# PKG900000001400.net
KiCad netlist of a schematic drawn in EAGLE
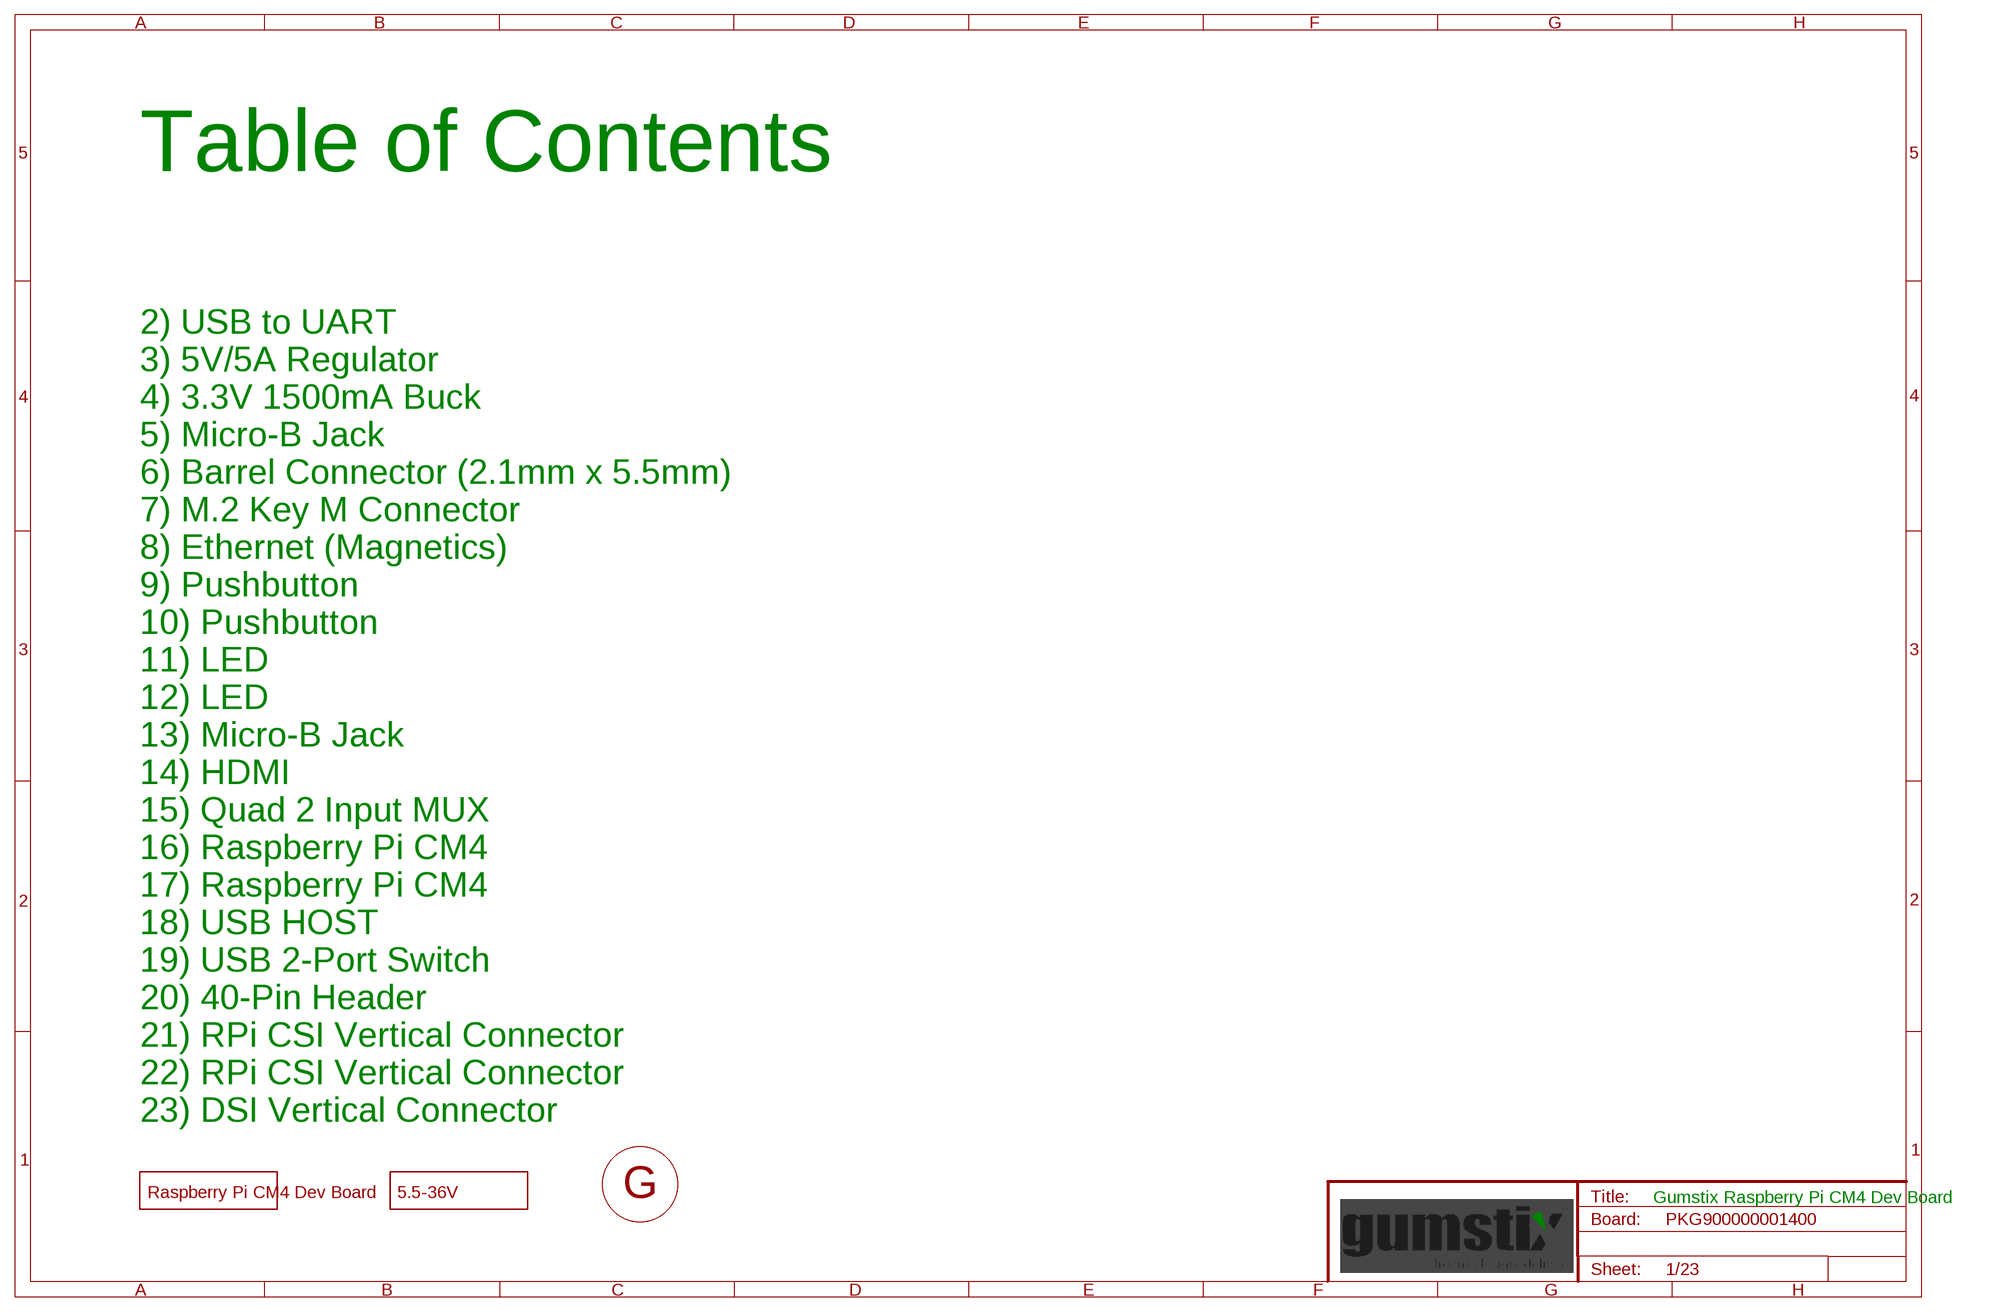
[diagram p0: schematic, sheet 1]
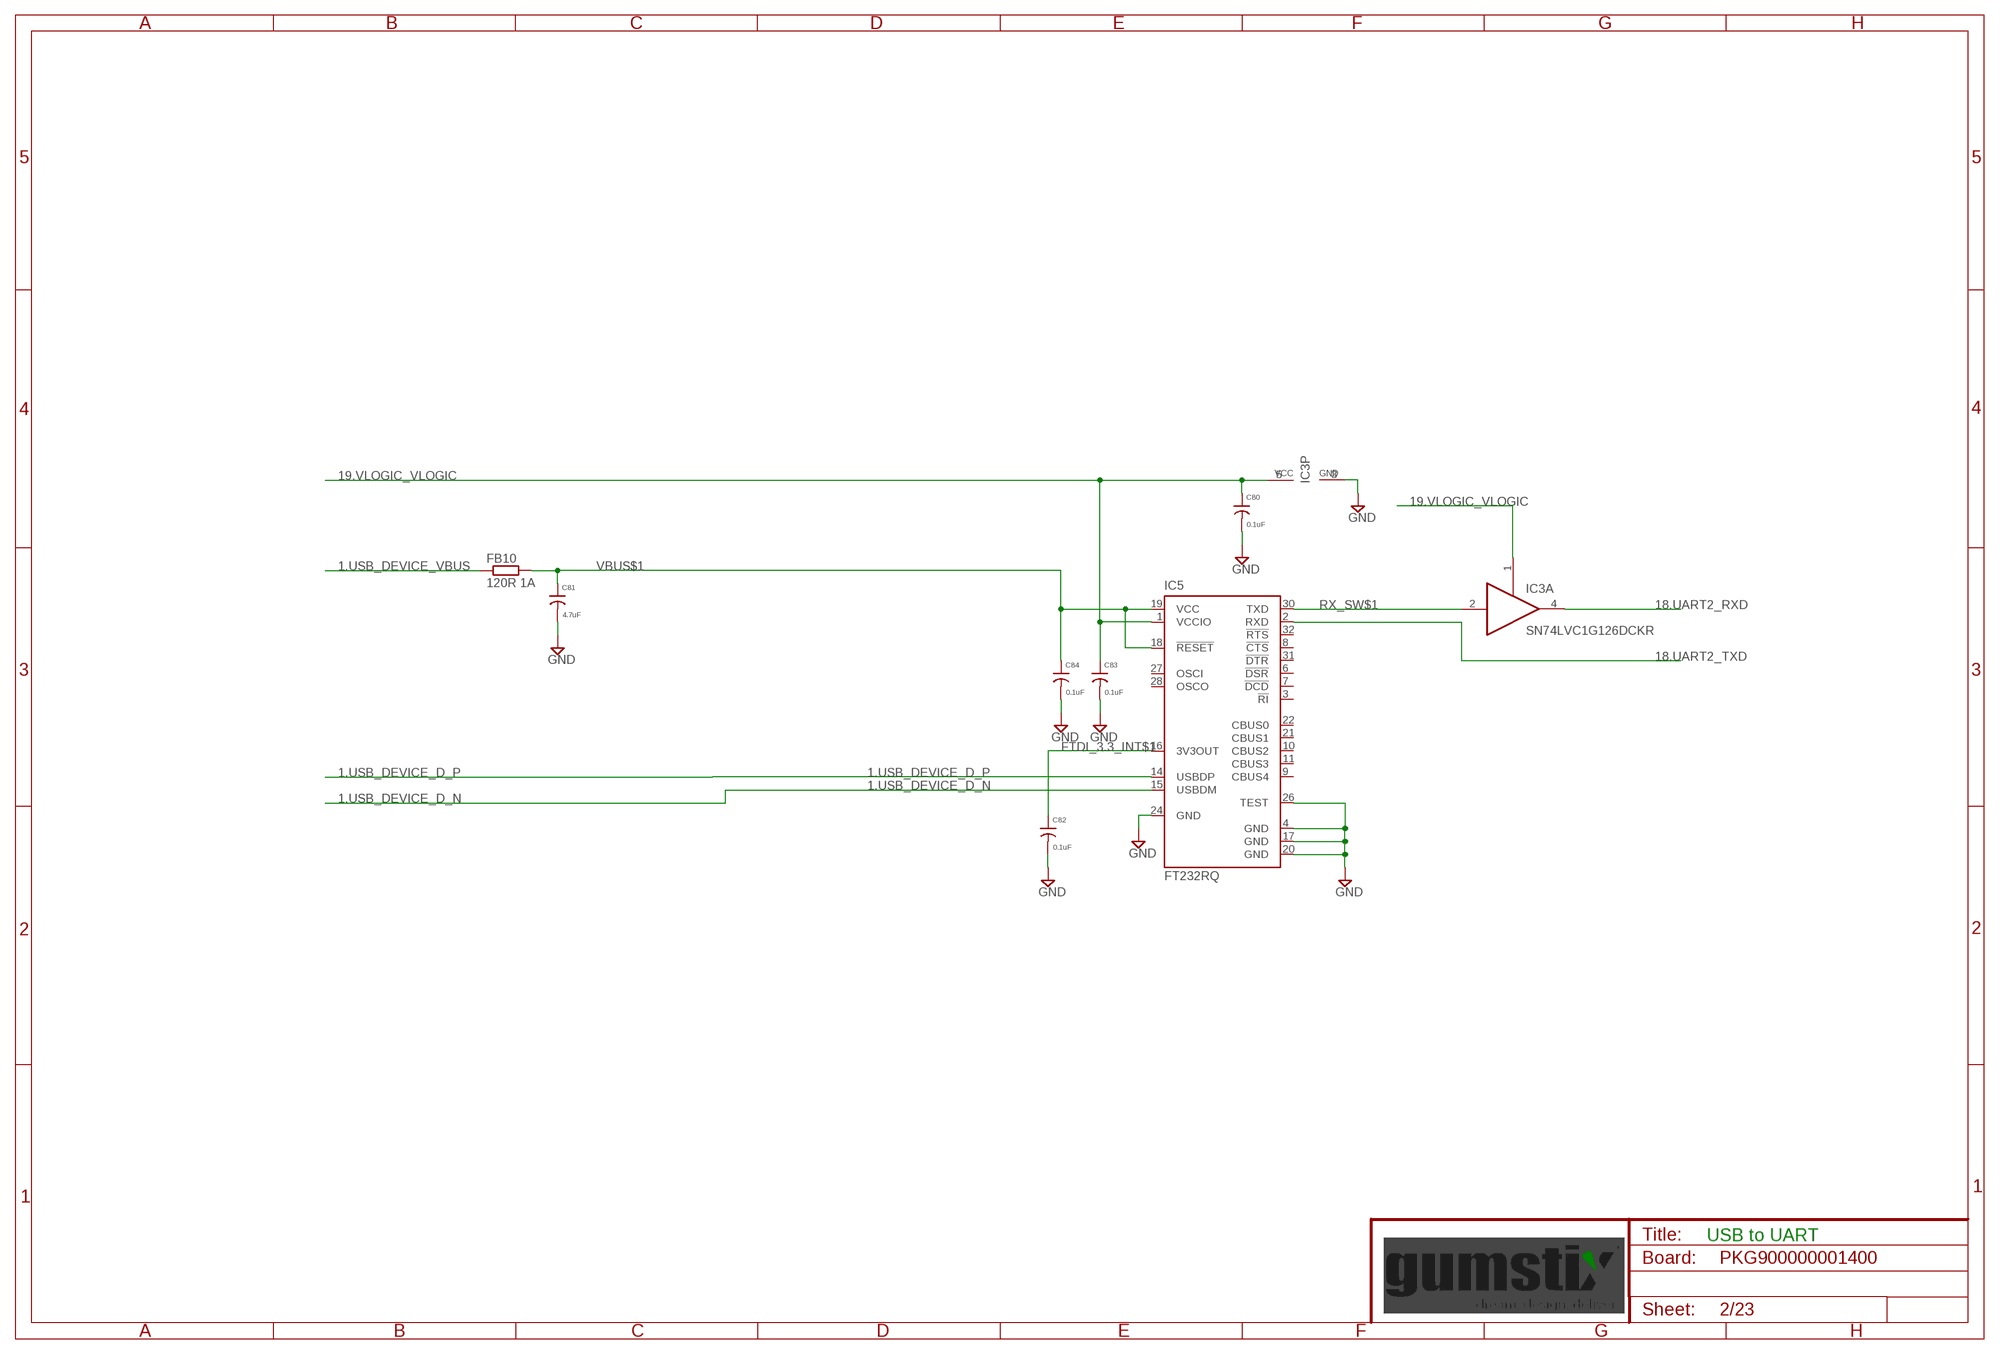
[diagram p1: schematic, sheet 2]
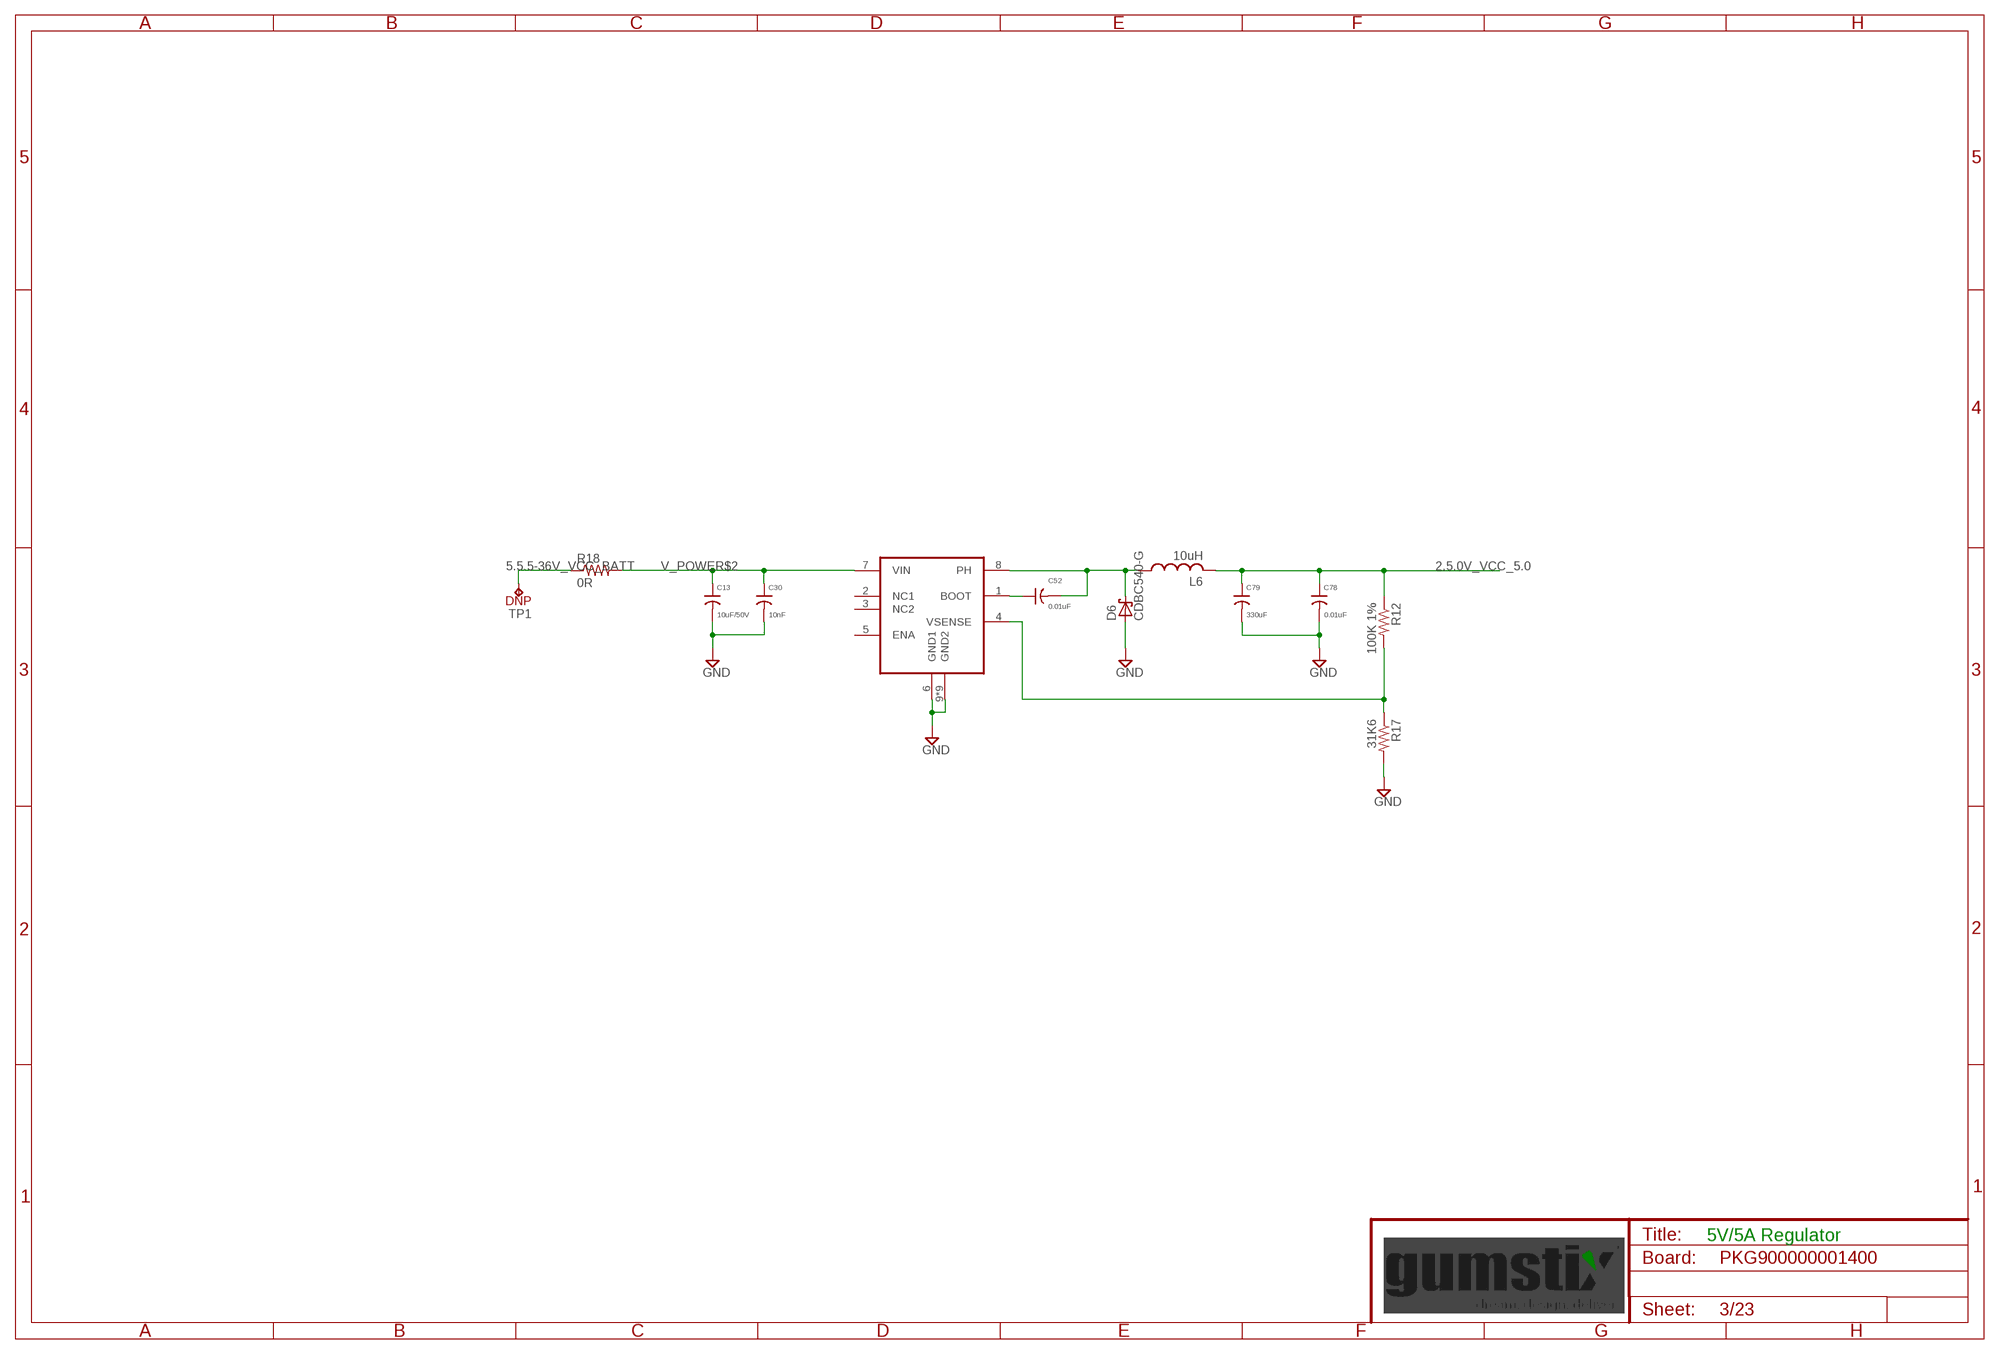
[diagram p2: schematic, sheet 3]
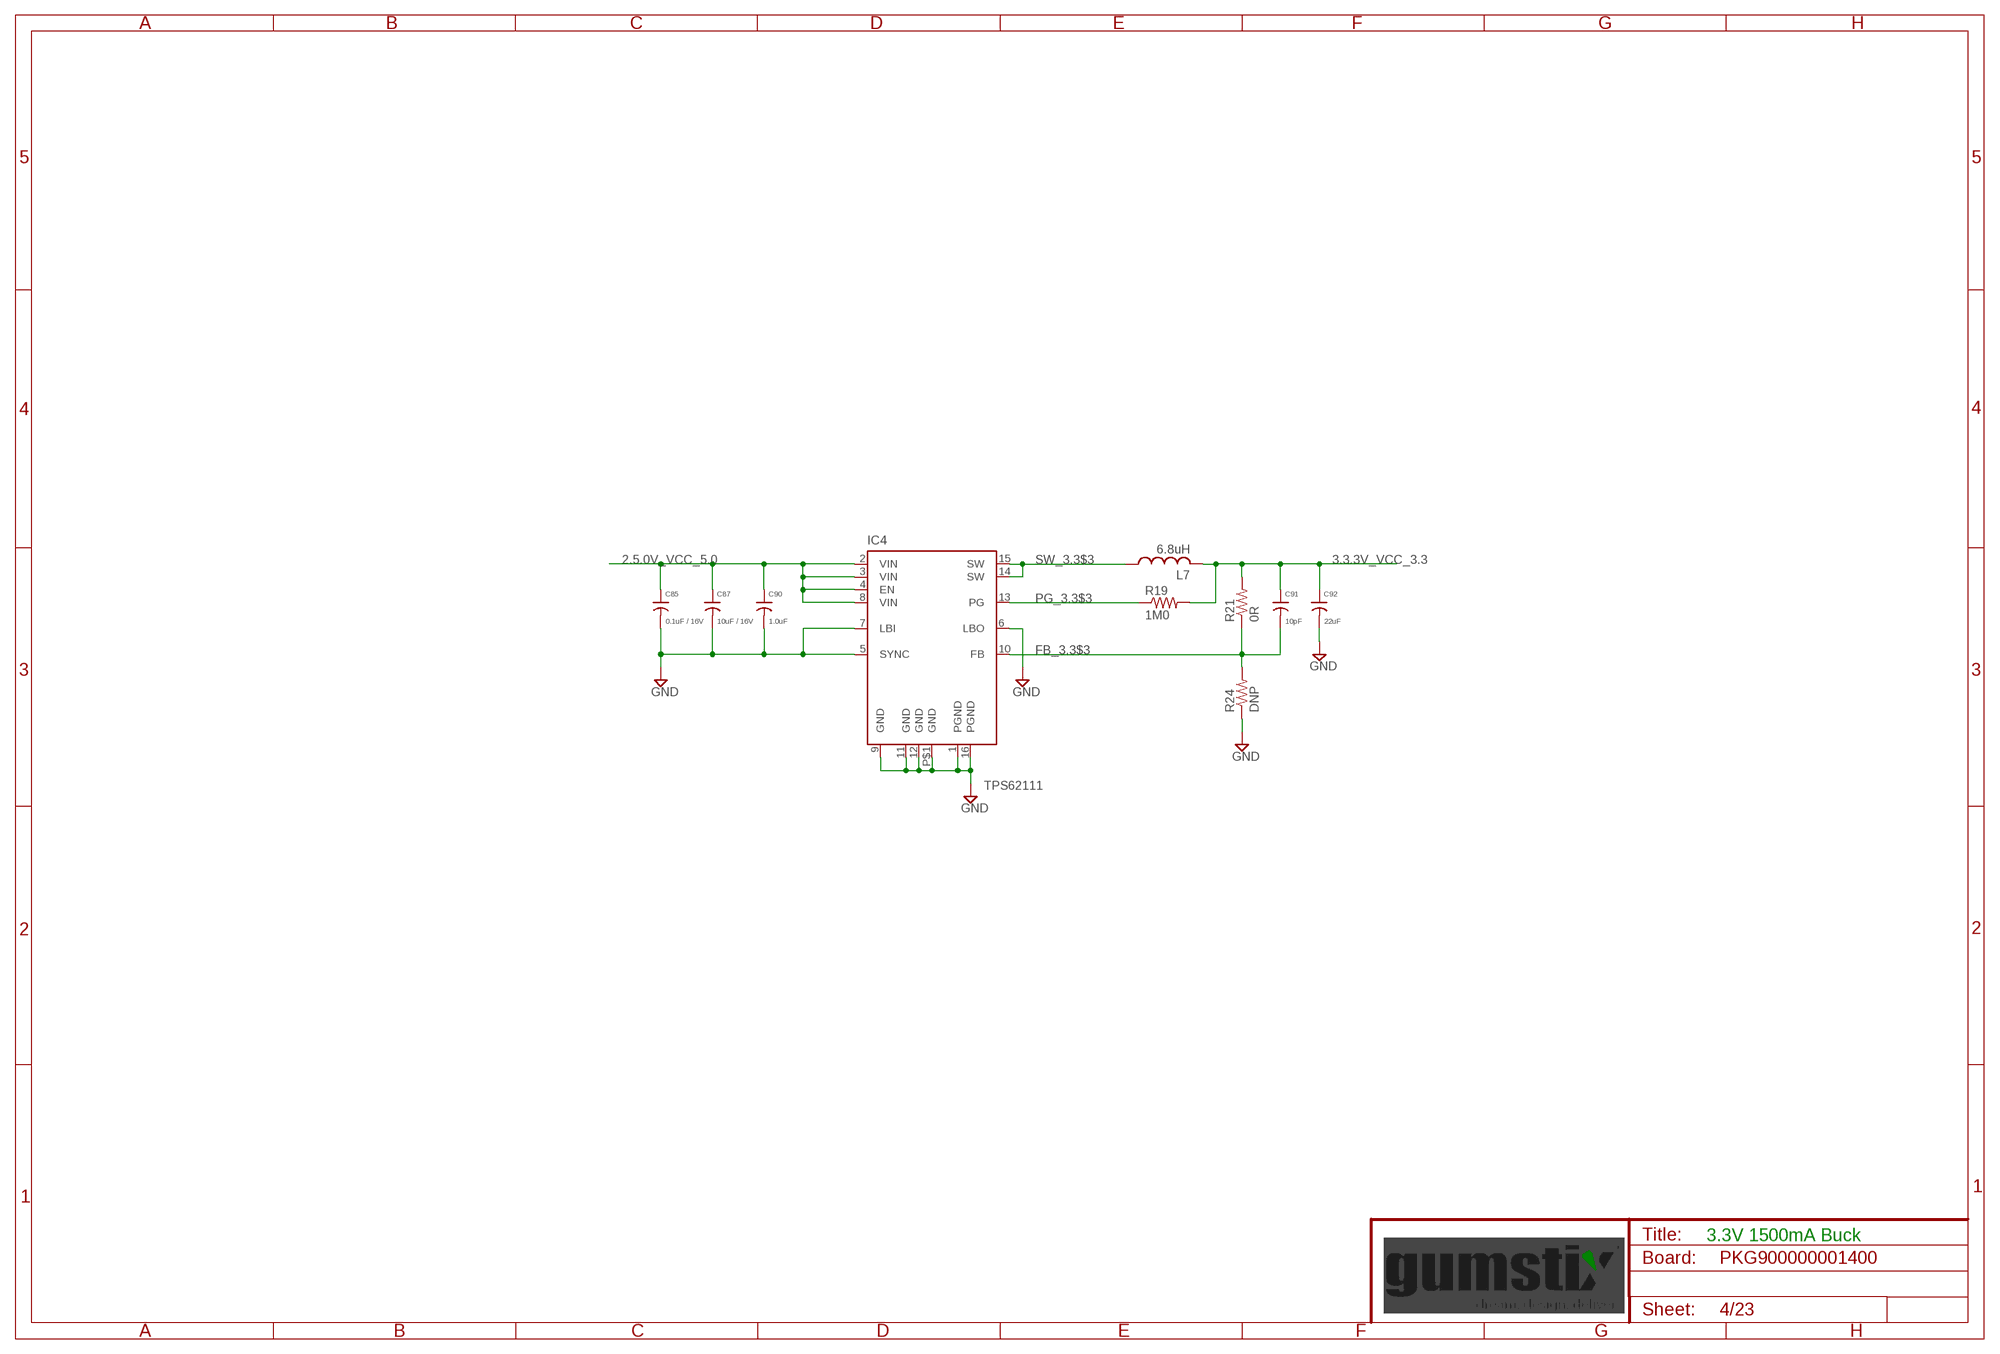
[diagram p3: schematic, sheet 4]
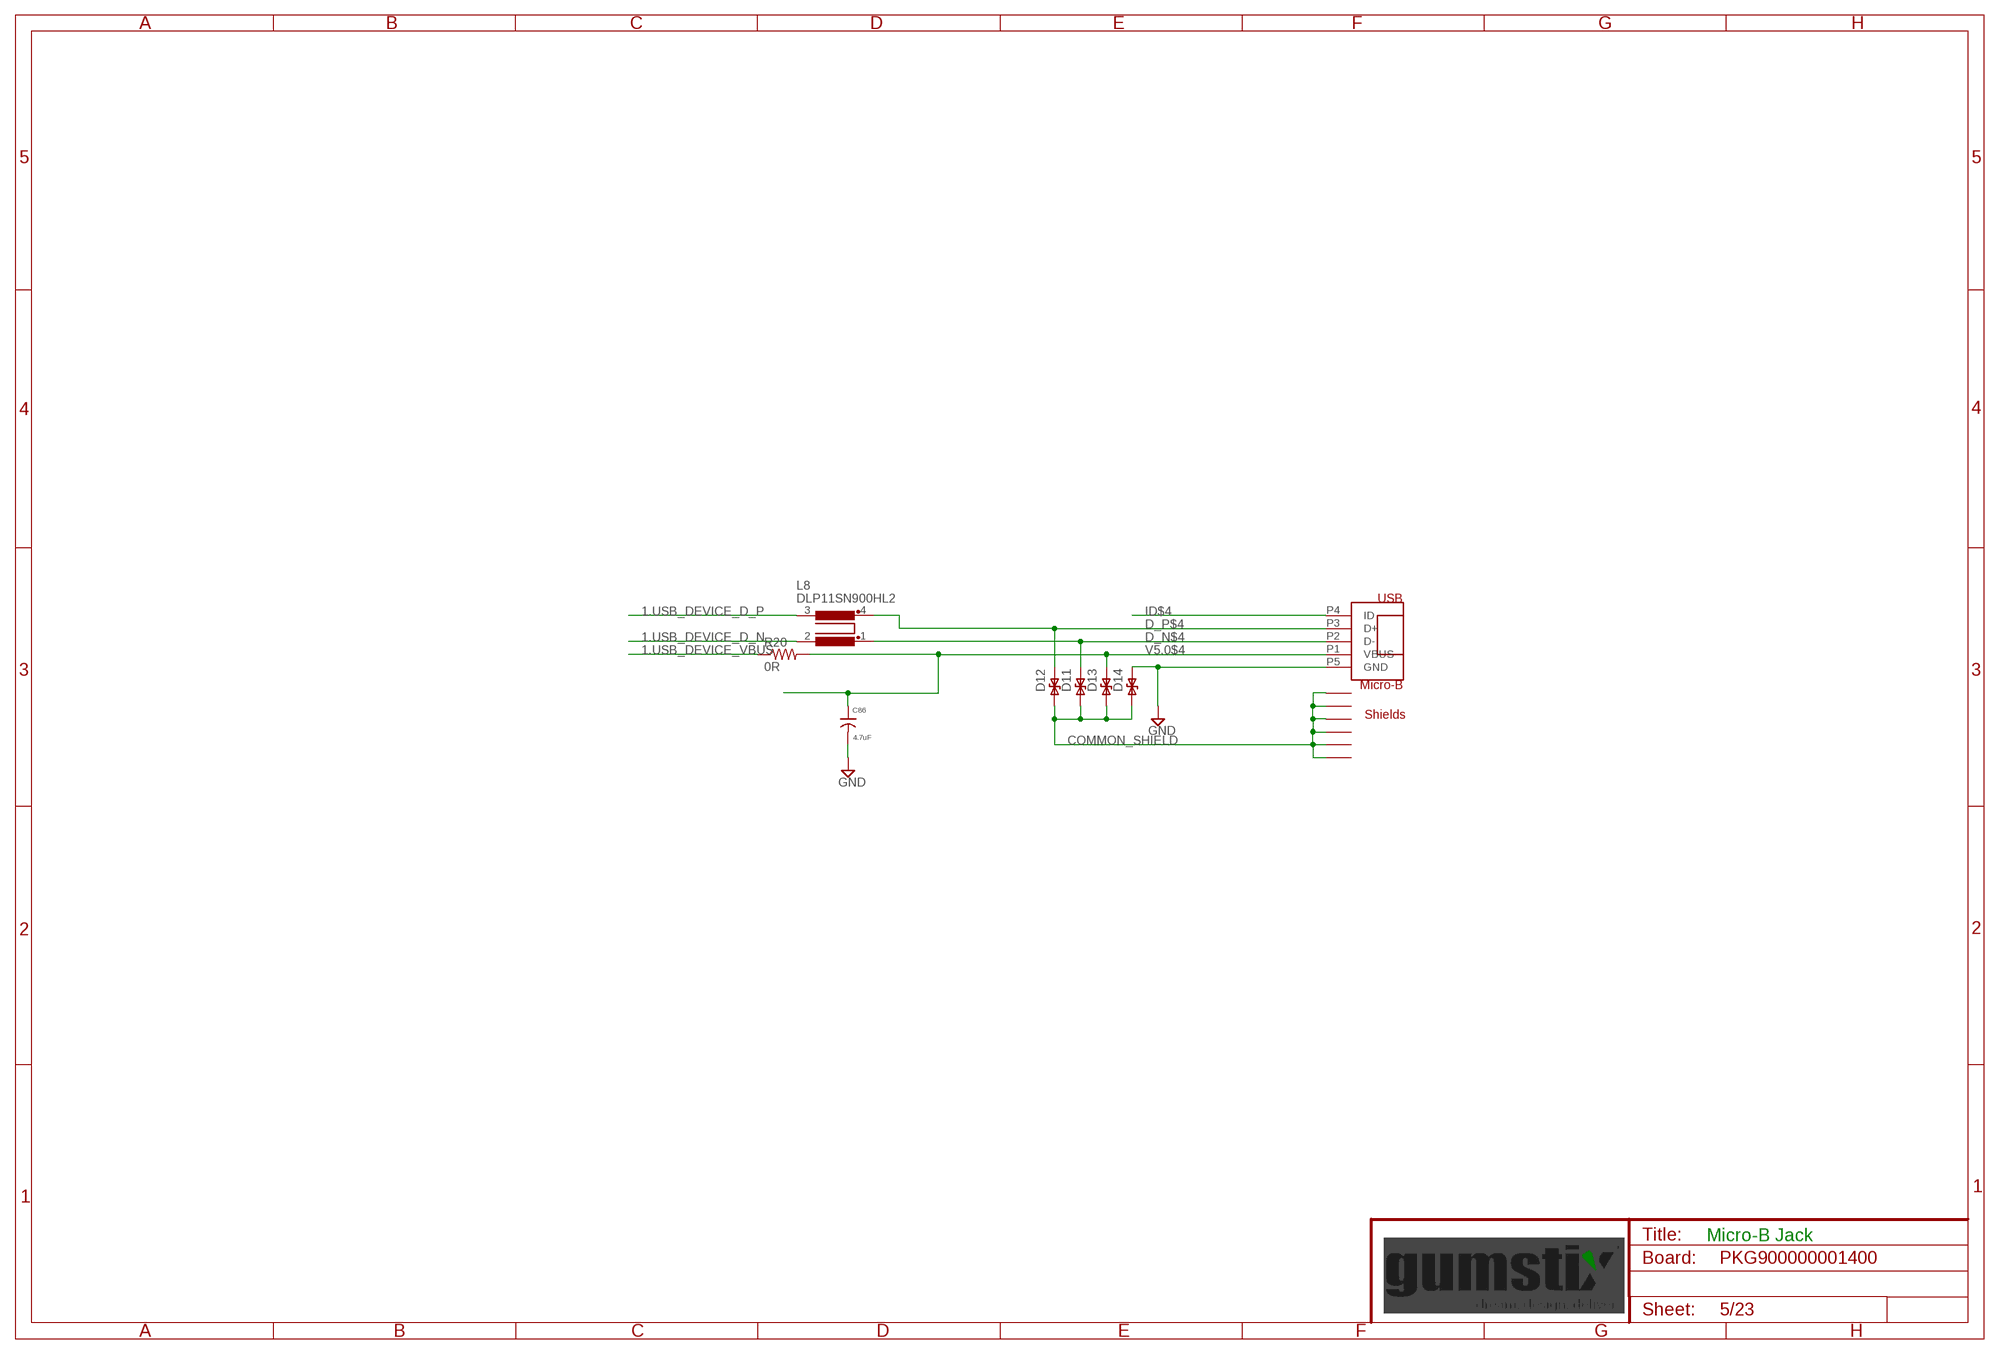
[diagram p4: schematic, sheet 5]
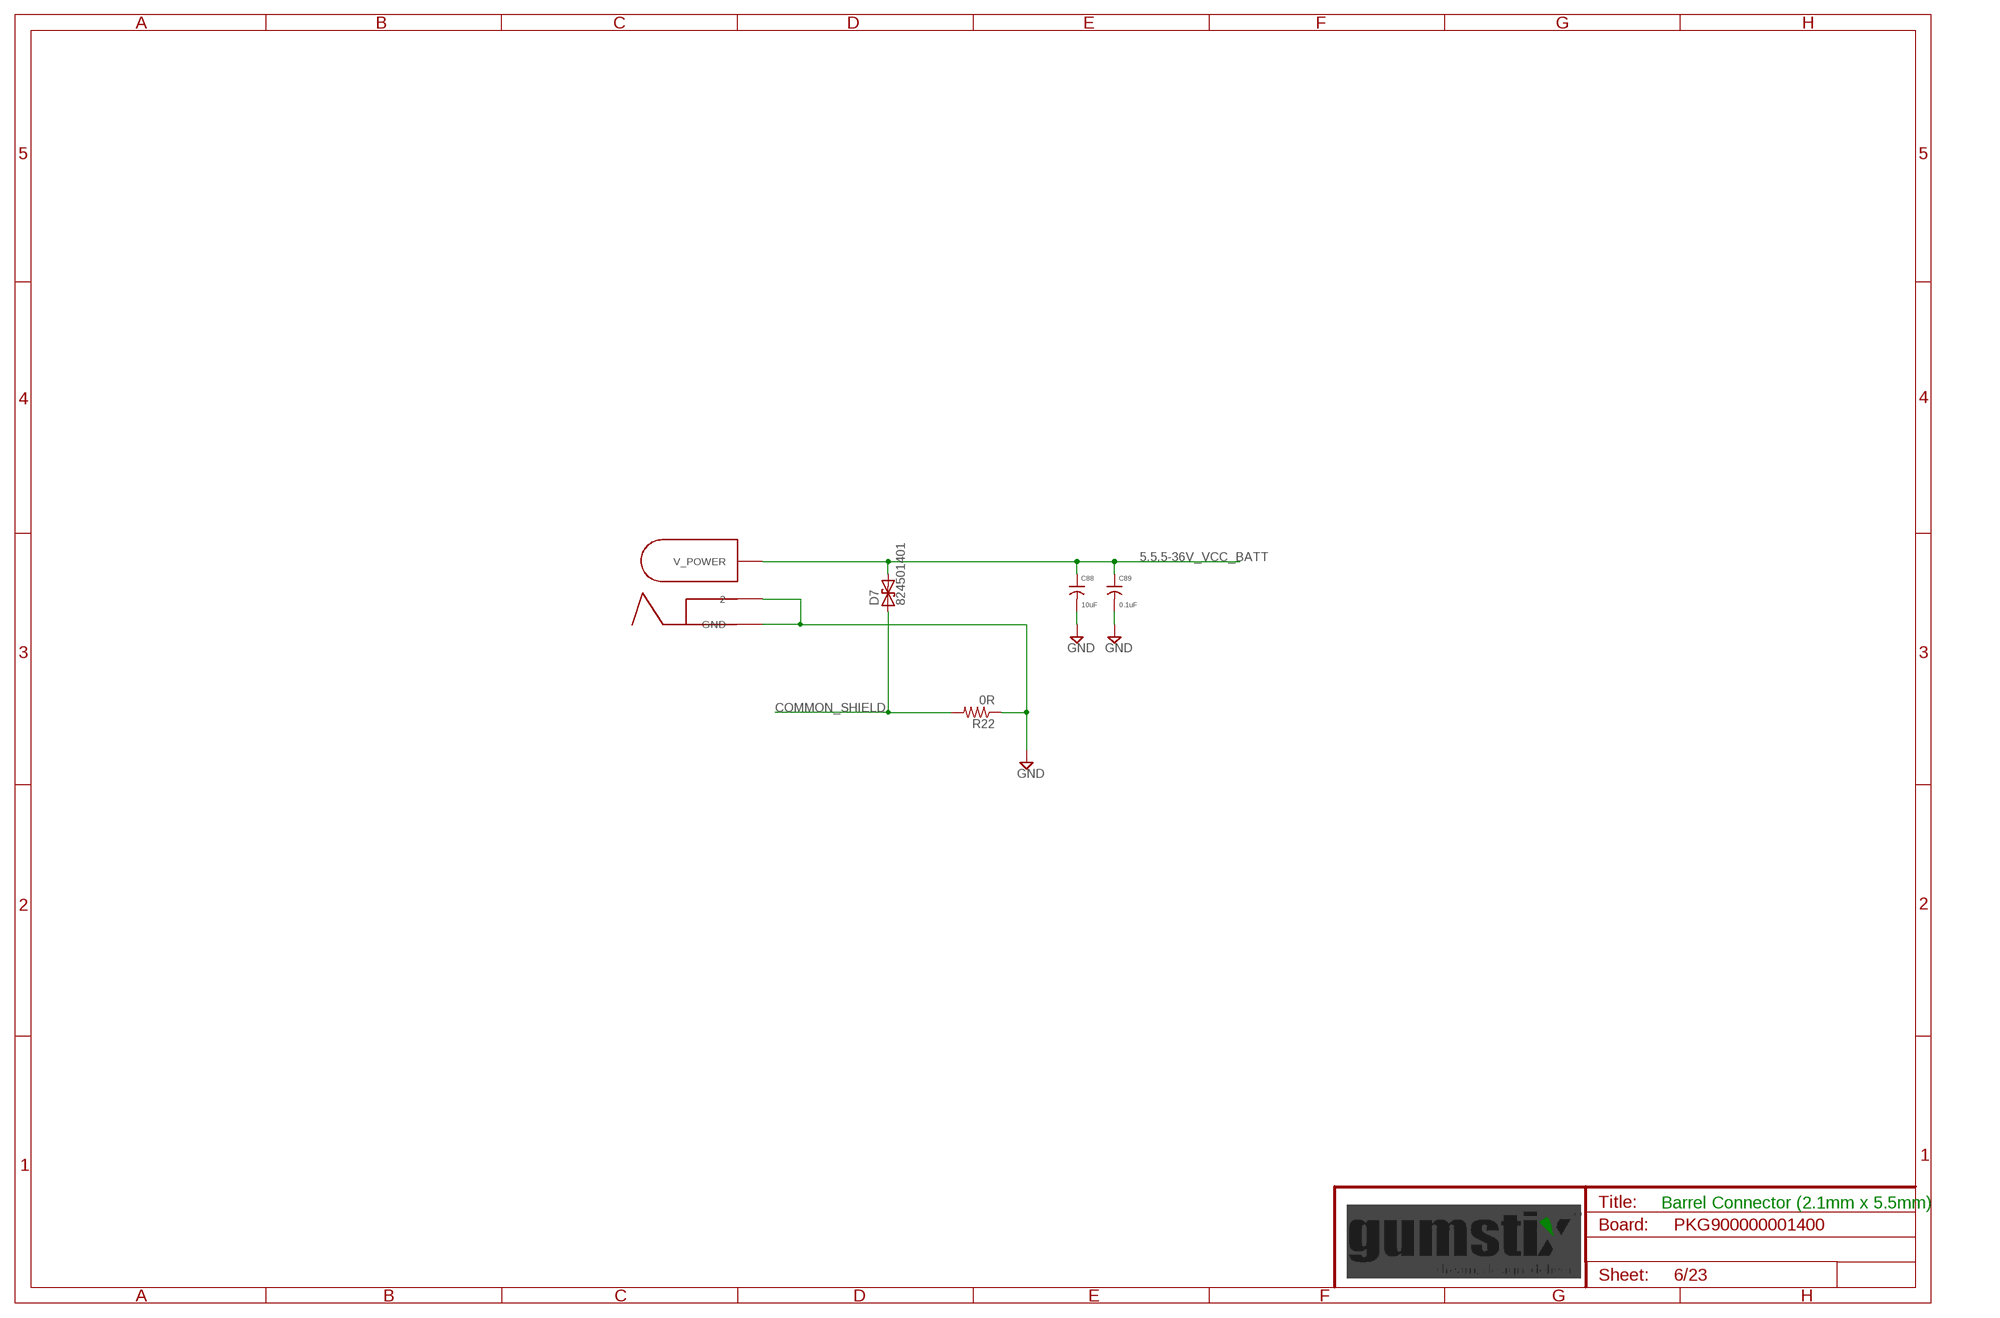
[diagram p5: schematic, sheet 6]
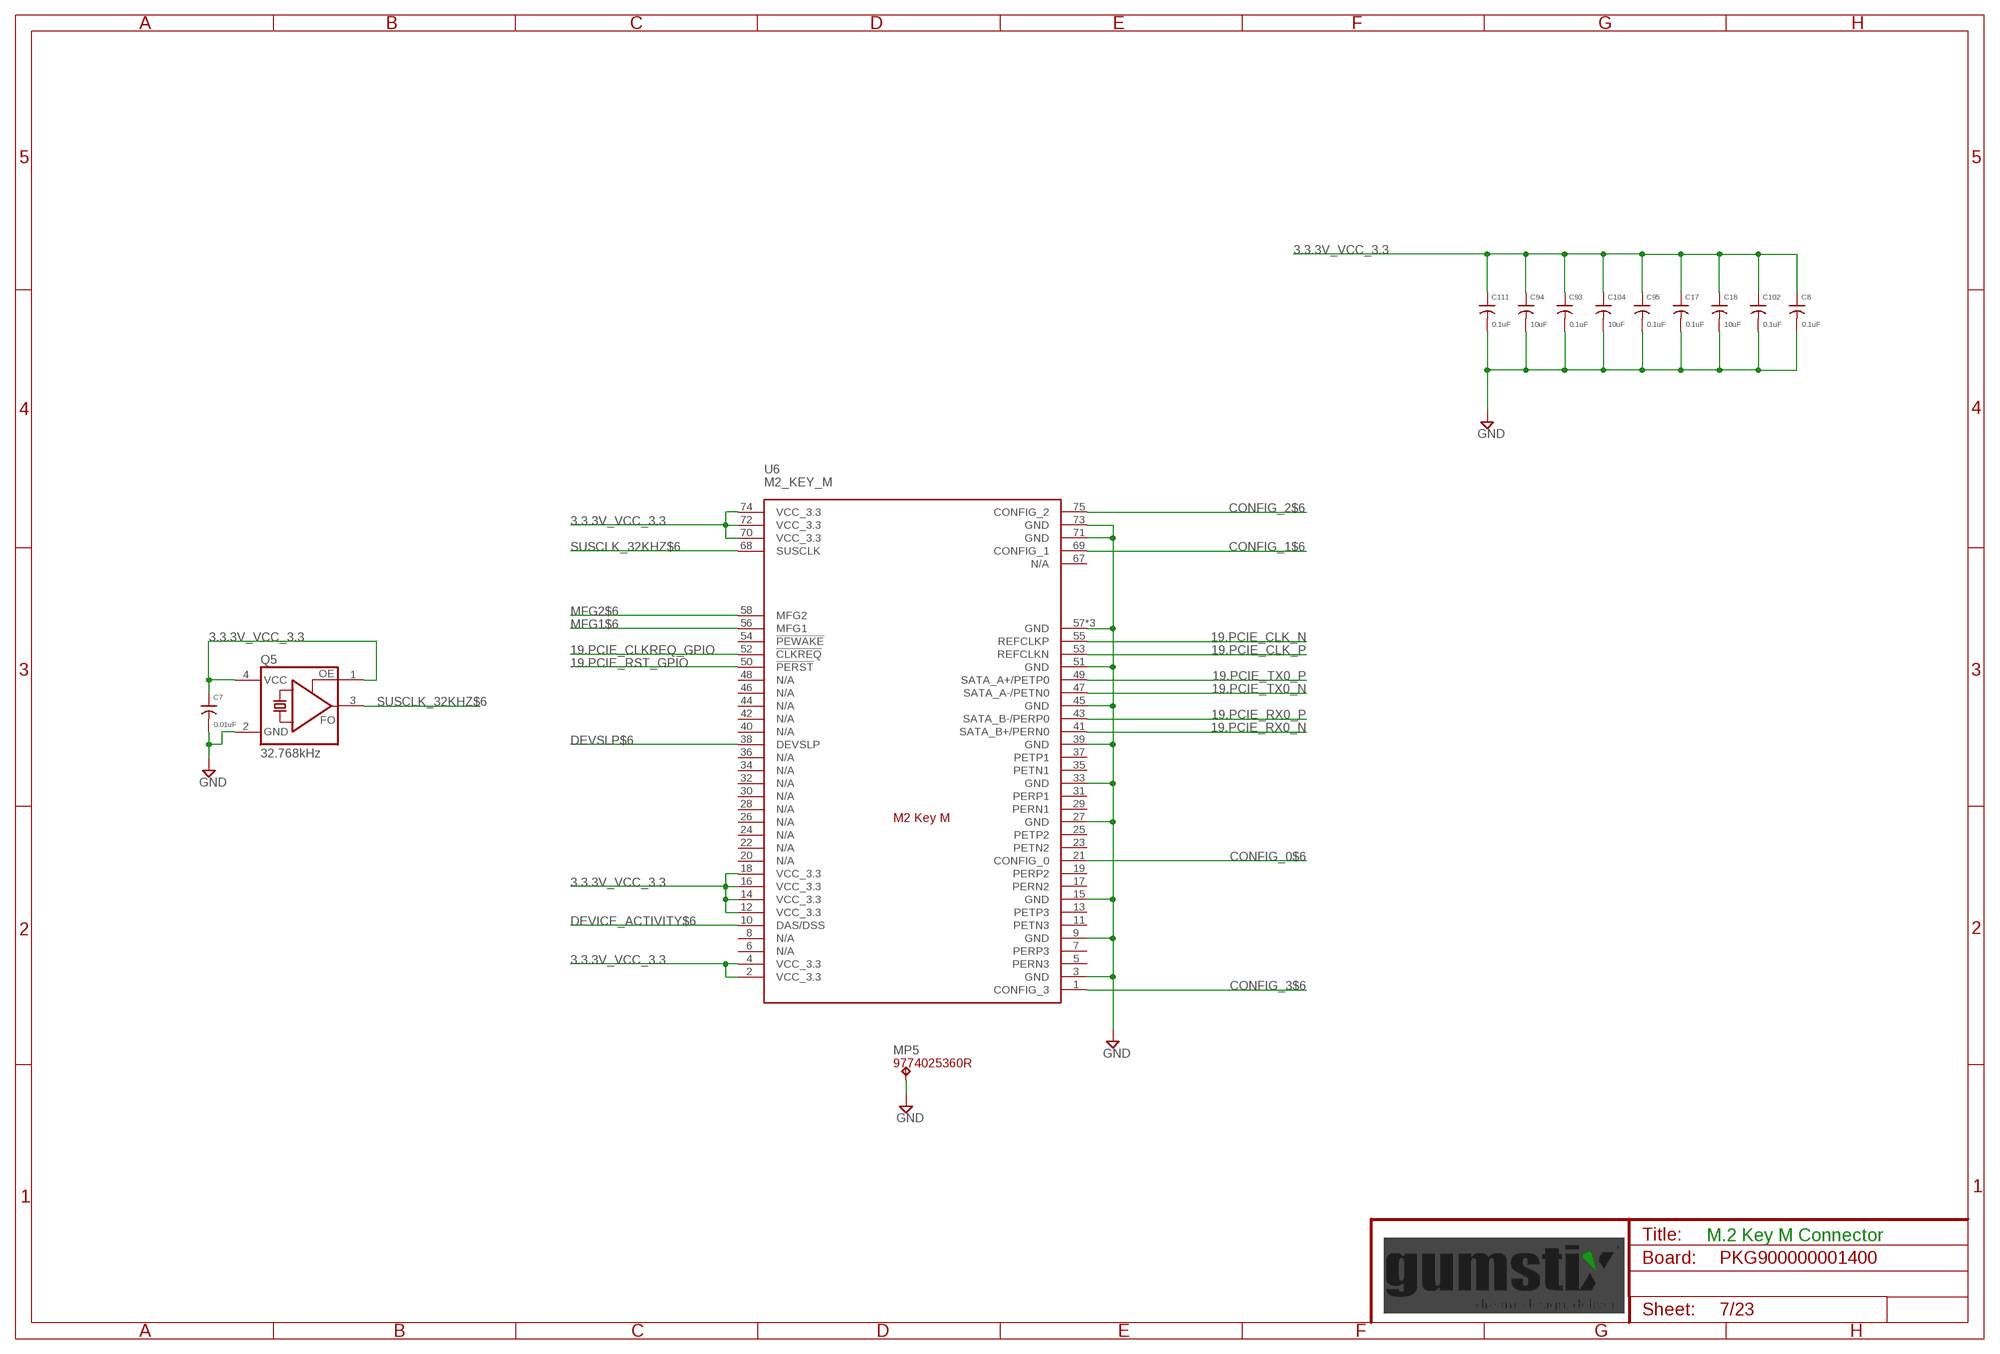
[diagram p6: schematic, sheet 7]
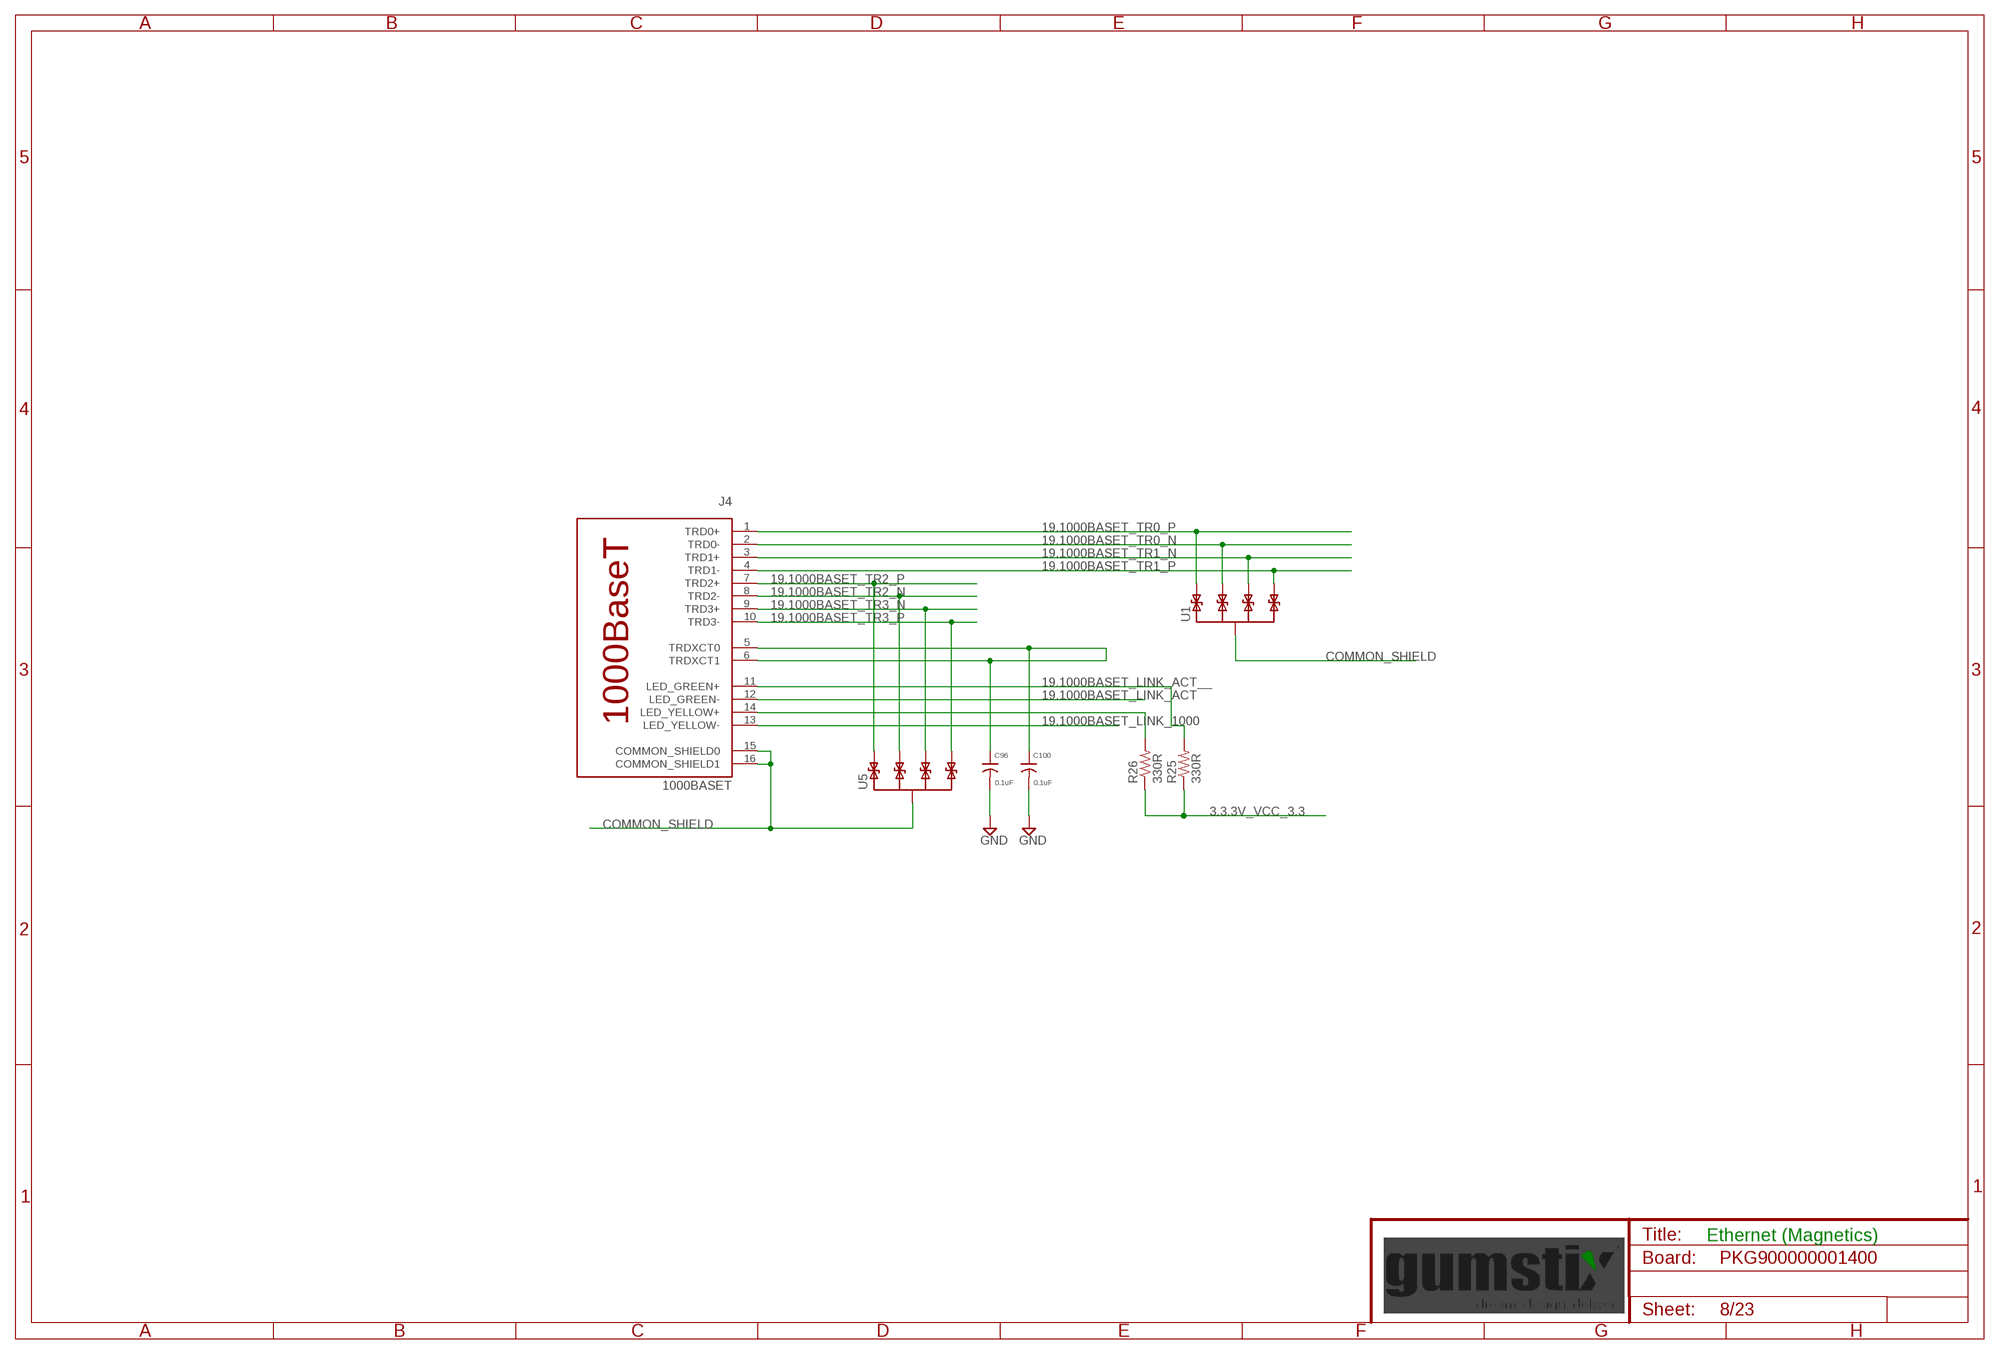
[diagram p7: schematic, sheet 8]
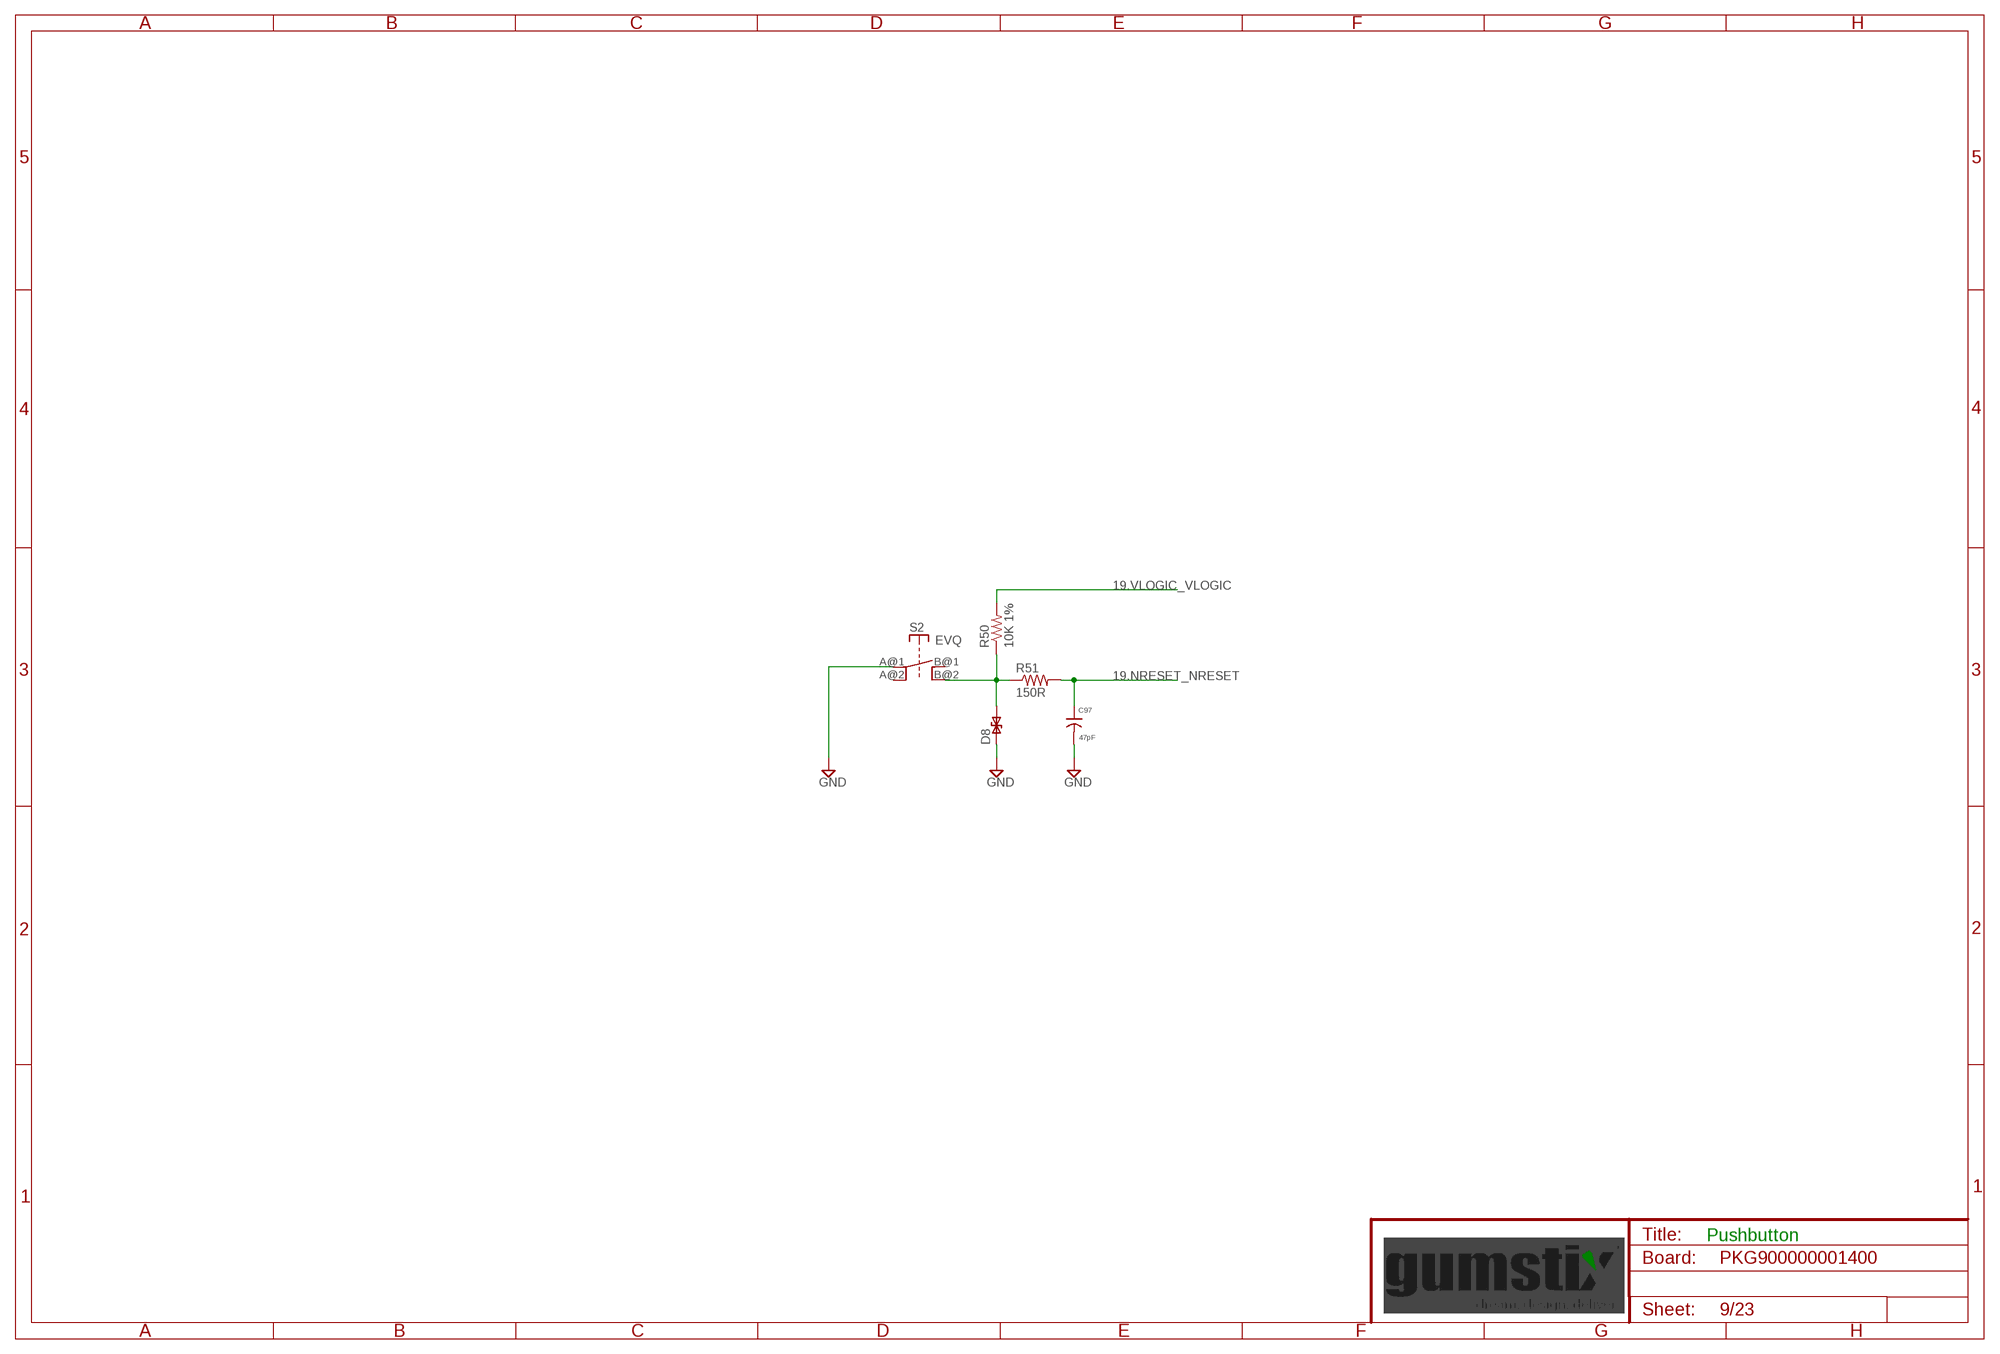
[diagram p8: schematic, sheet 9]
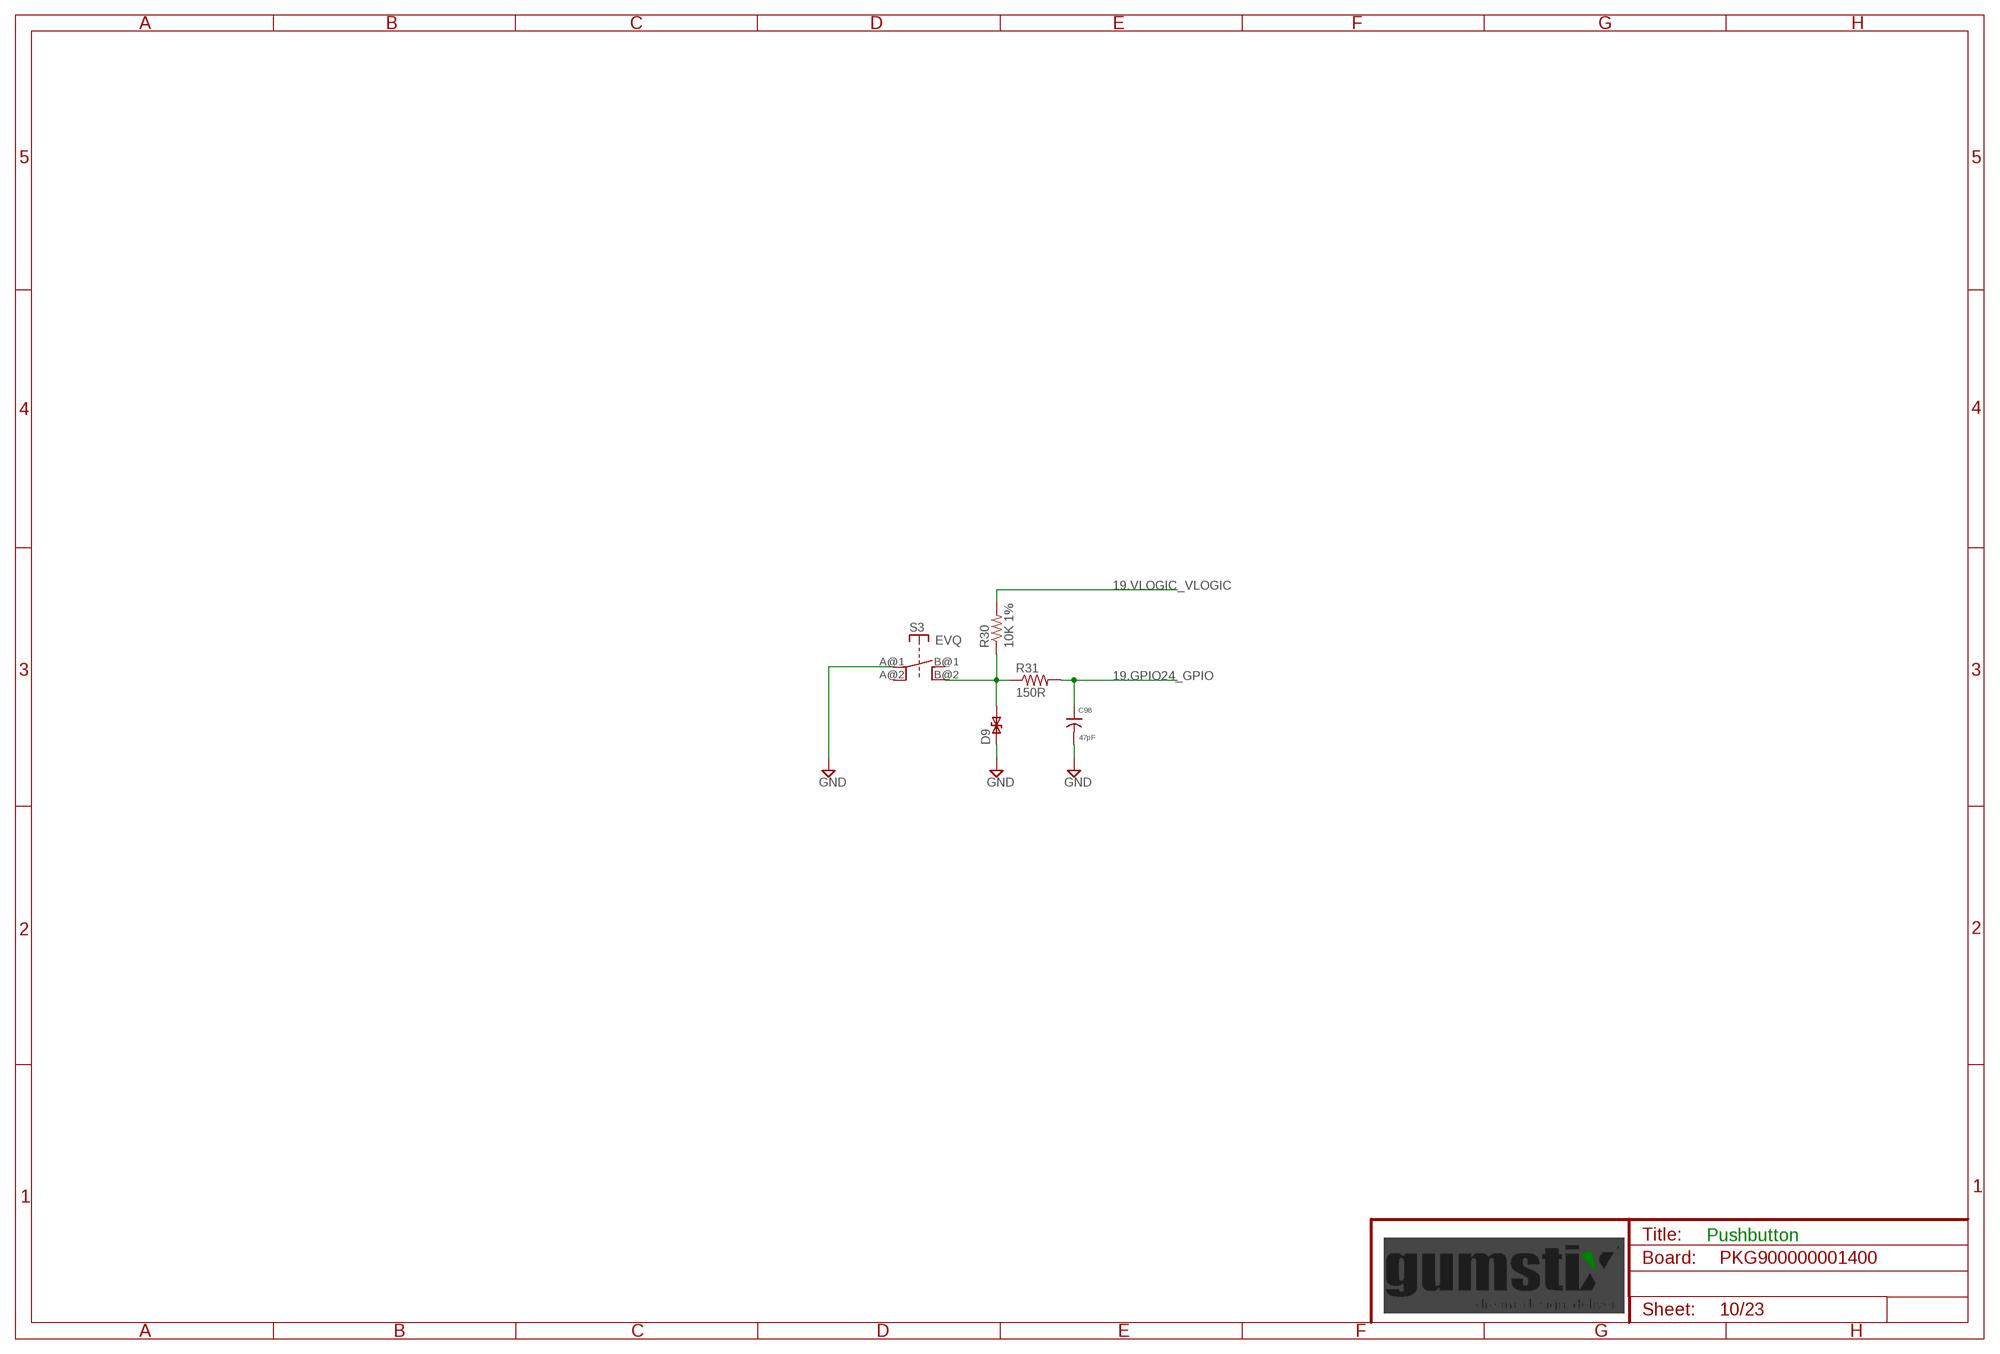
[diagram p9: schematic, sheet 10]
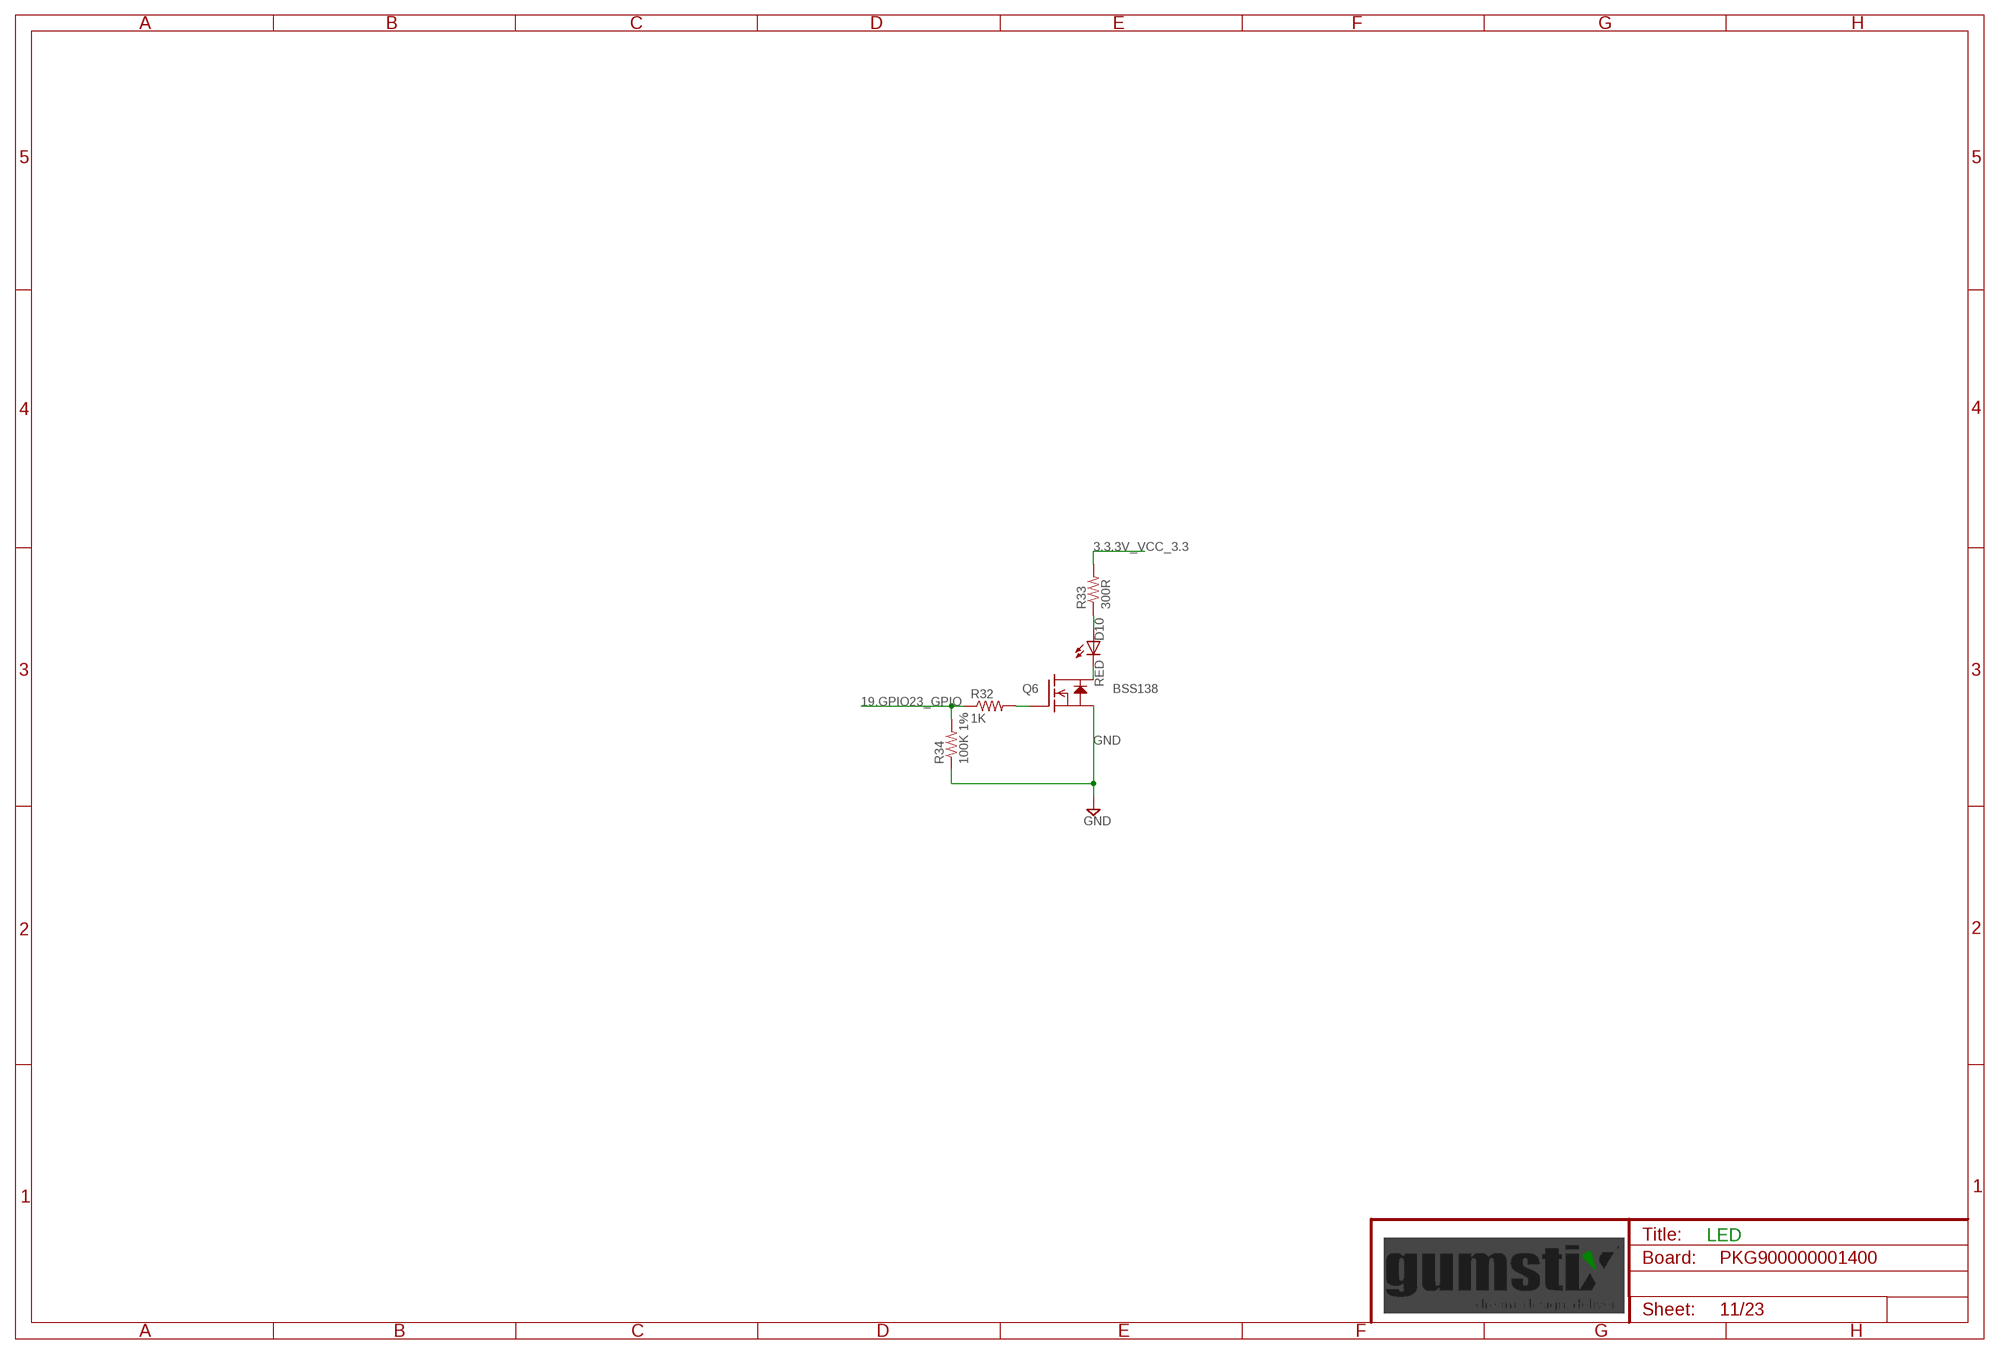
[diagram p10: schematic, sheet 11]
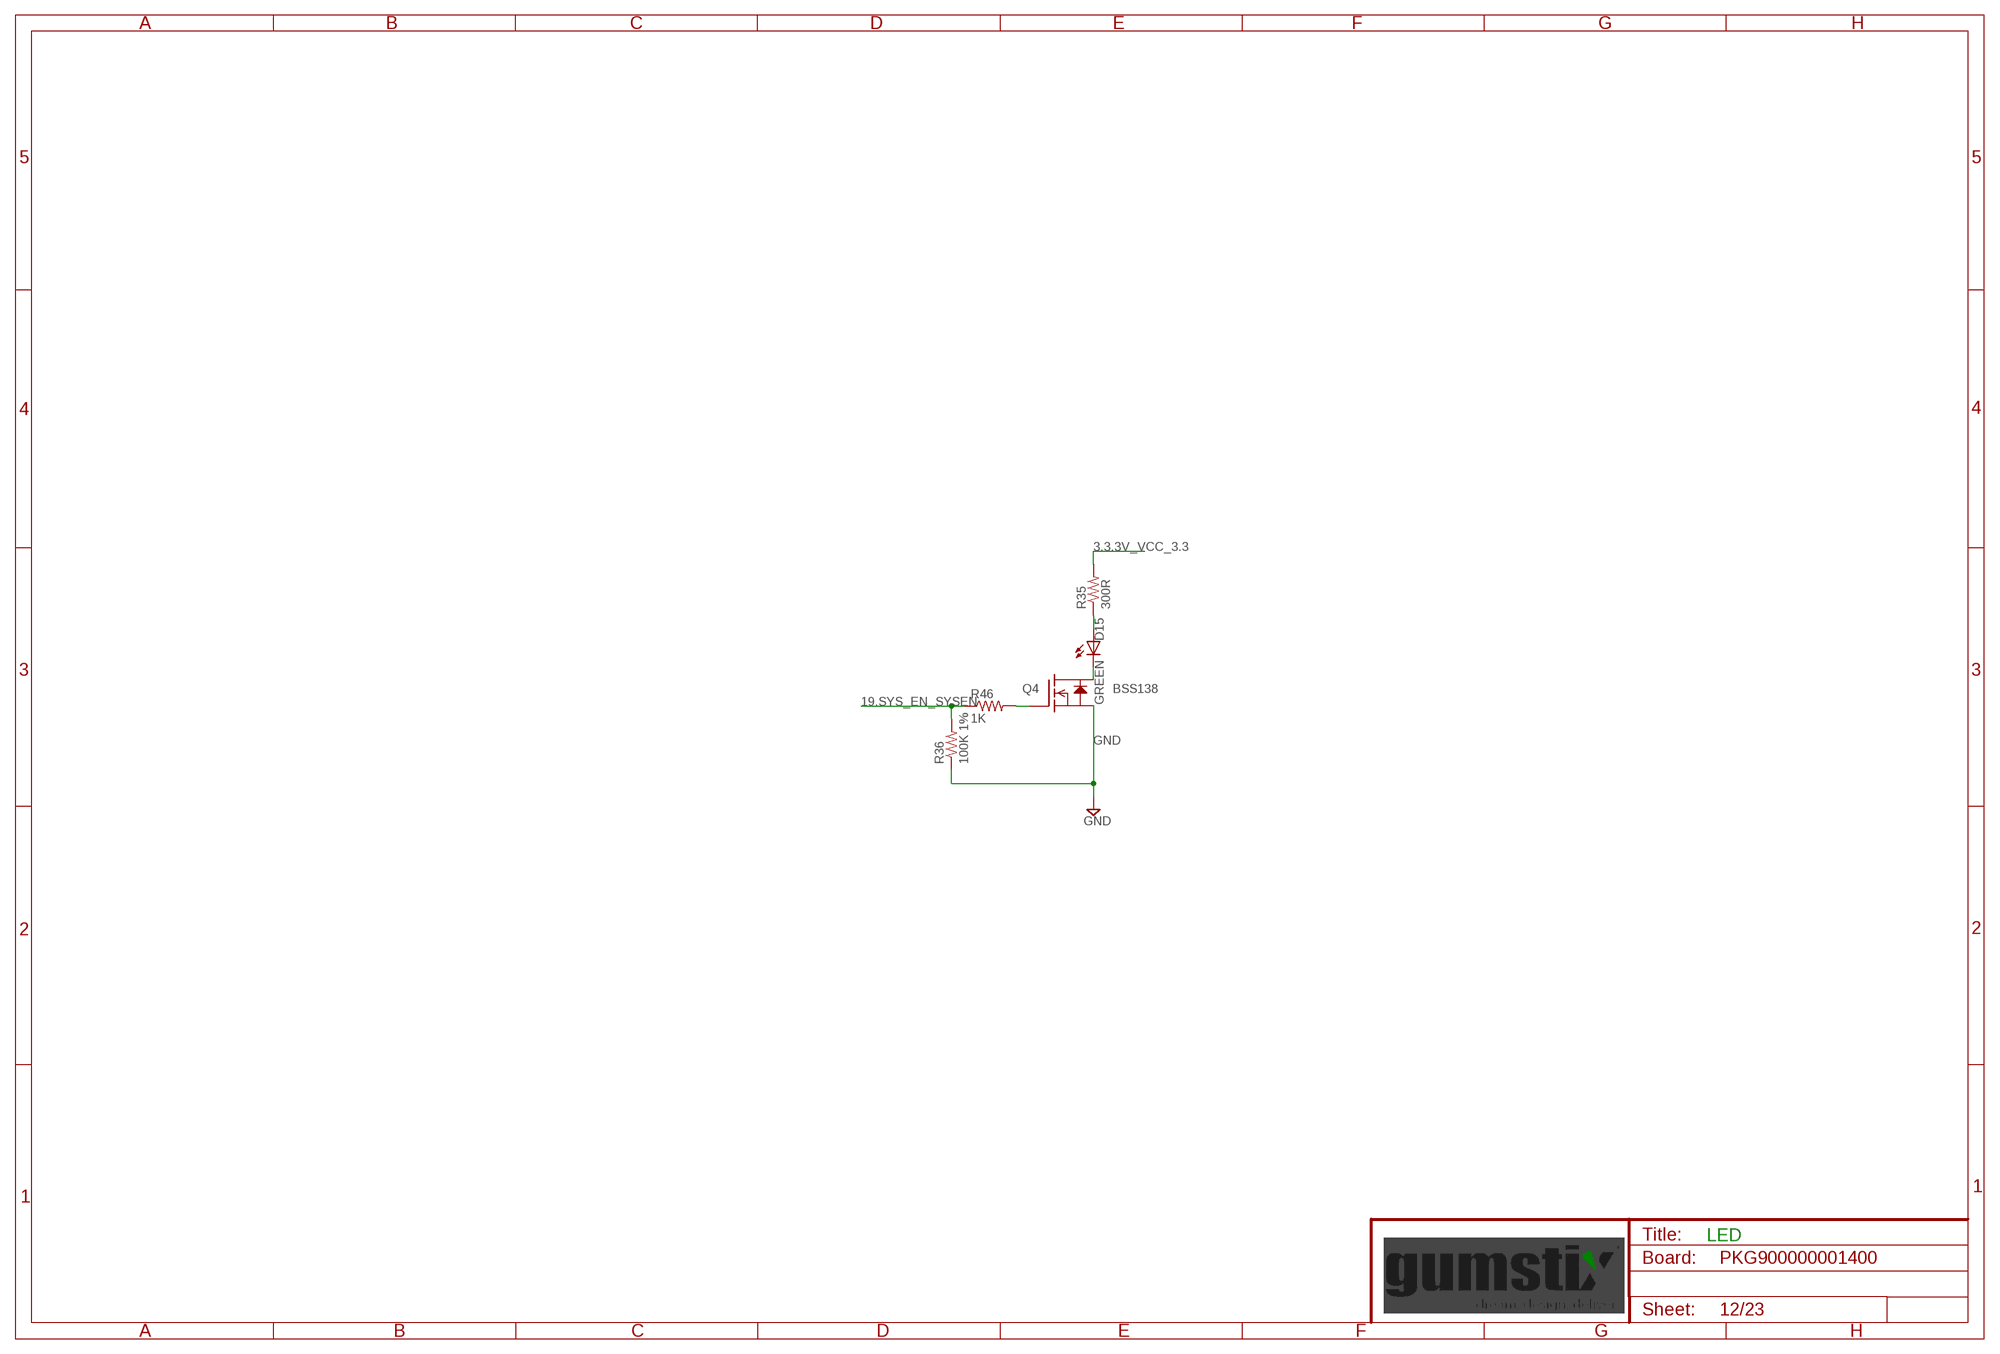
[diagram p11: schematic, sheet 12]
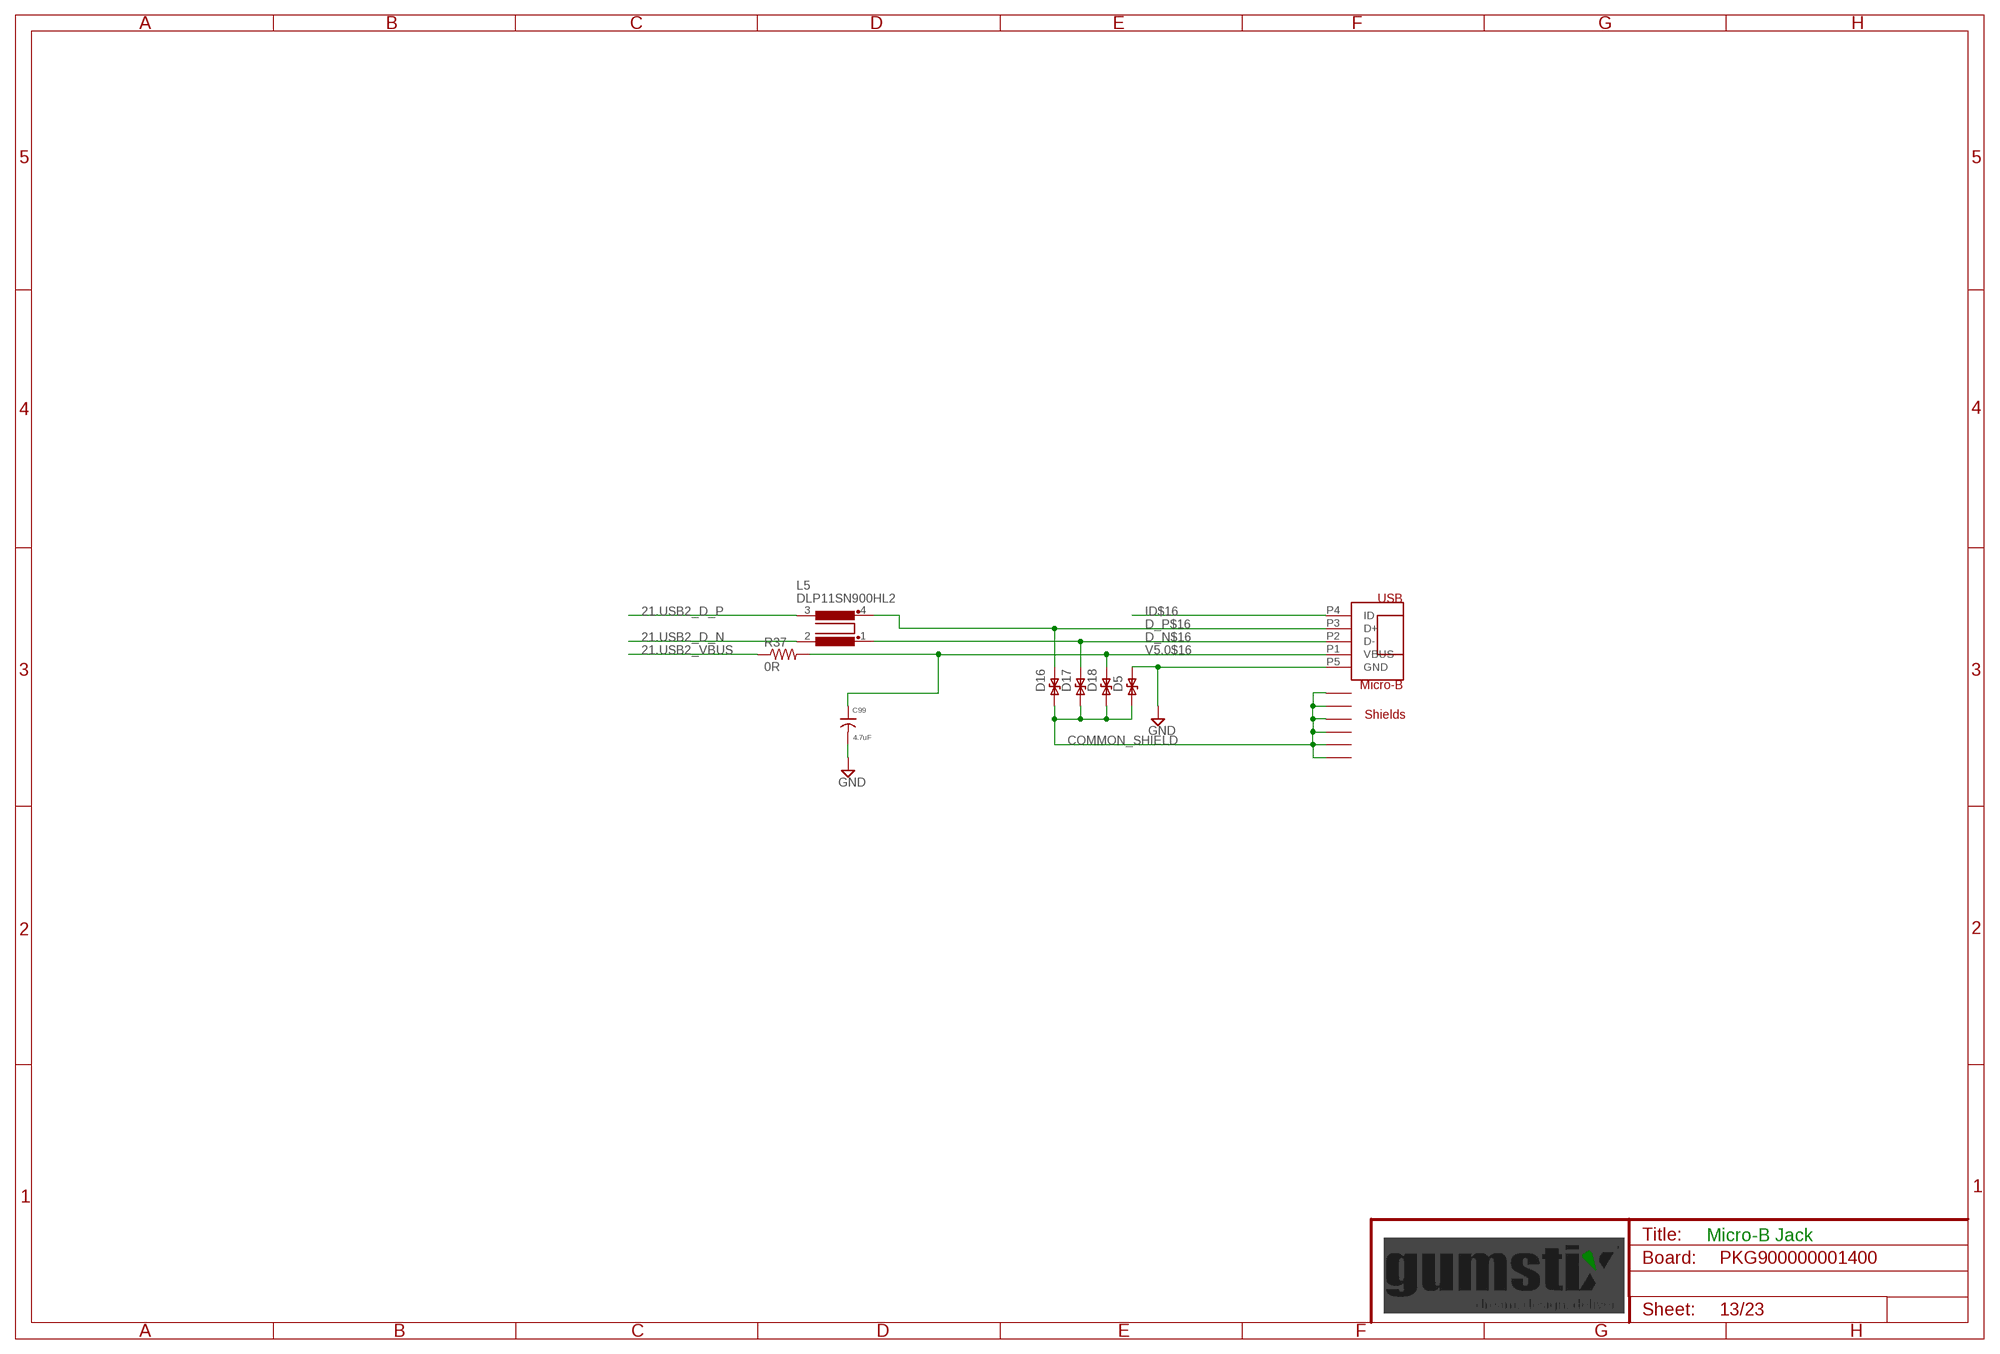
[diagram p12: schematic, sheet 13]
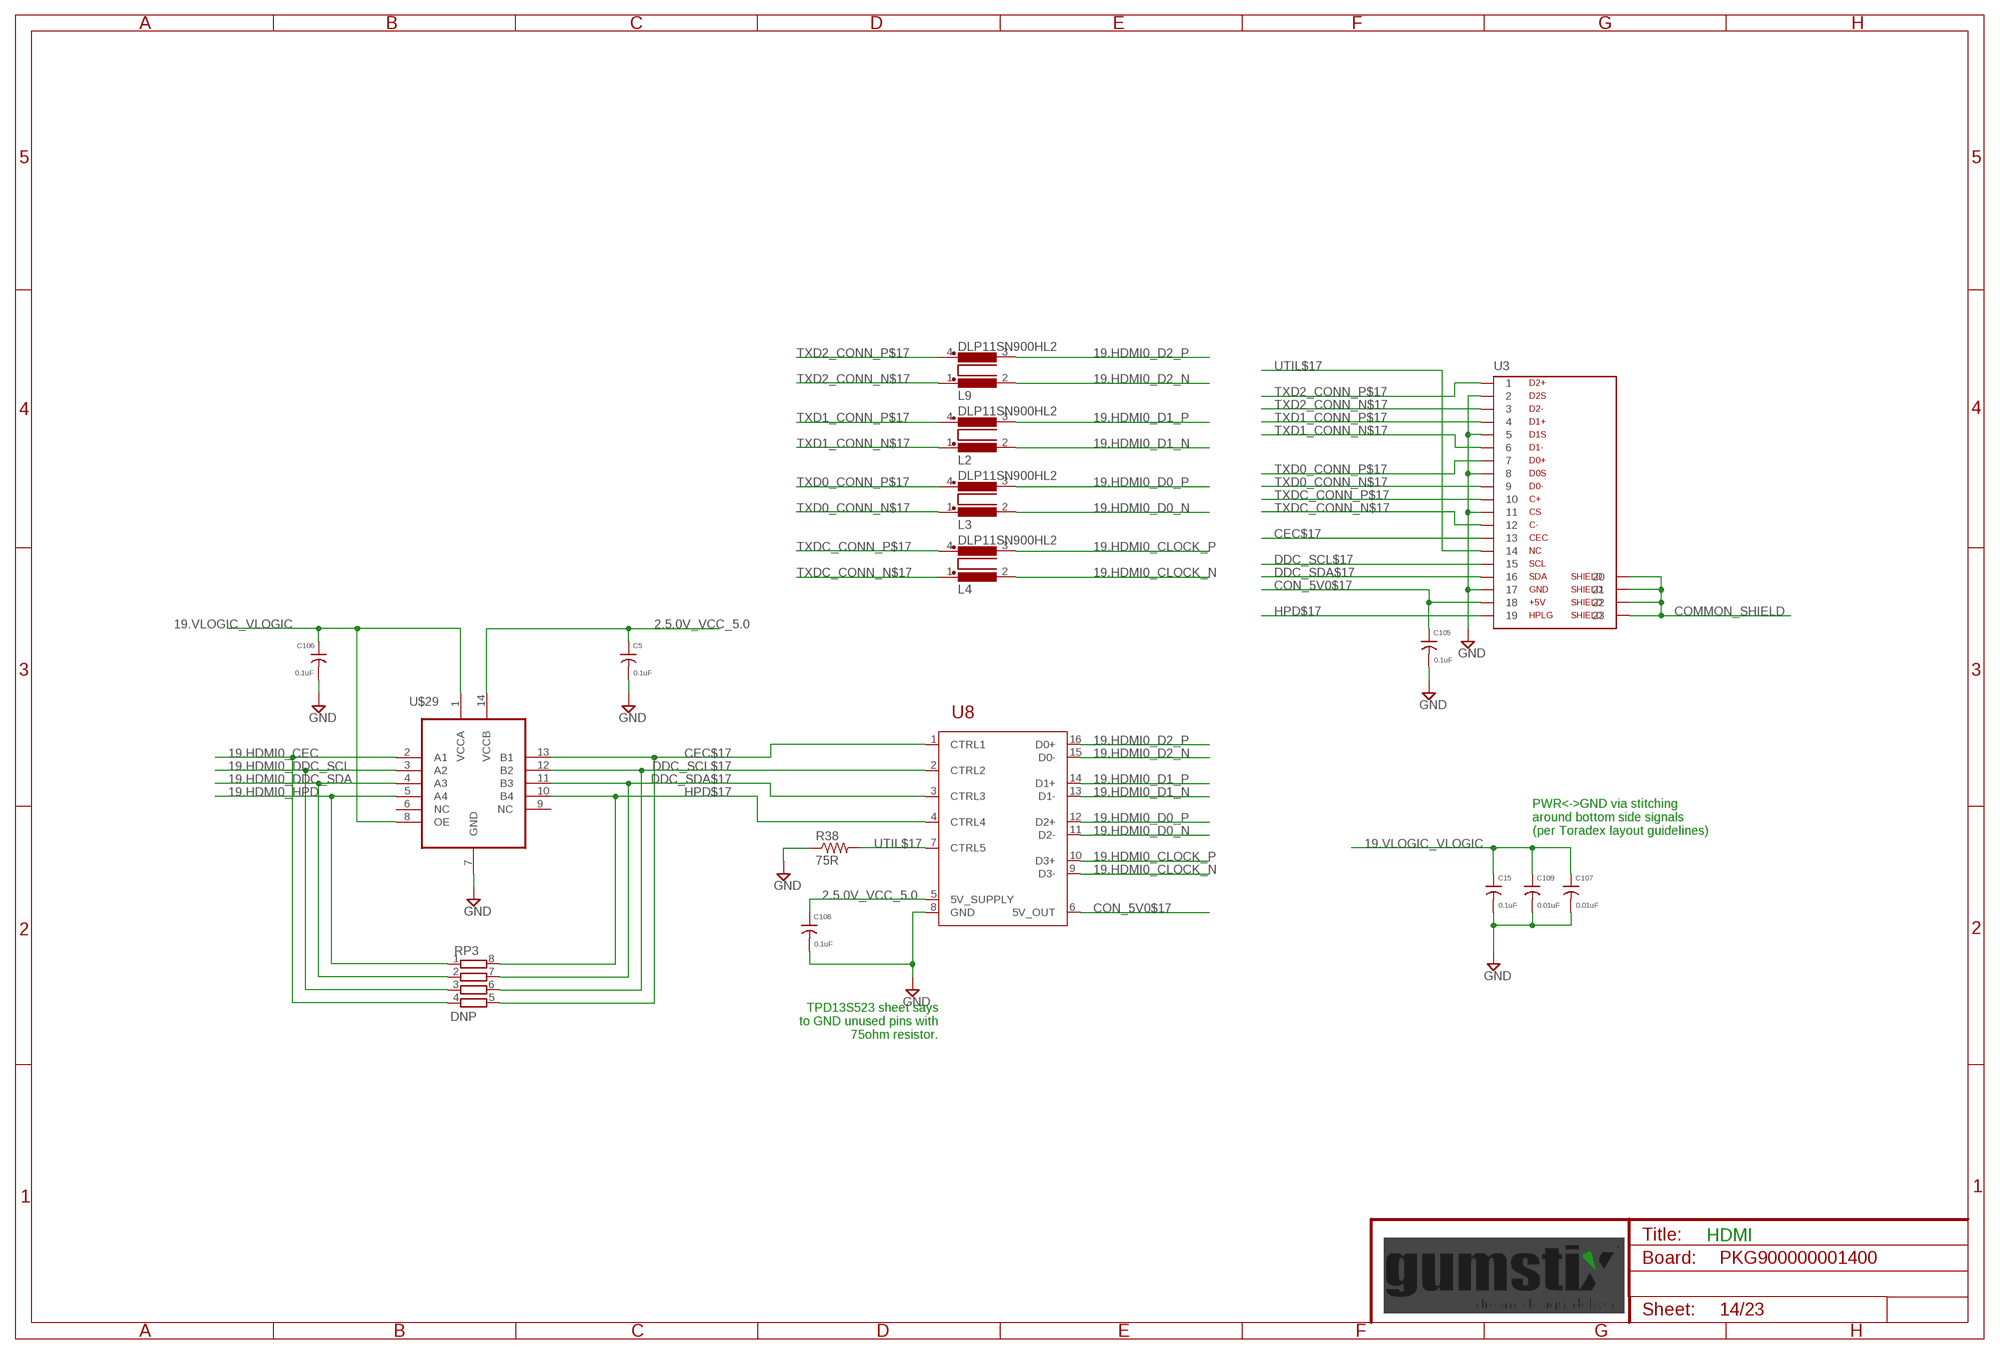
[diagram p13: schematic, sheet 14]
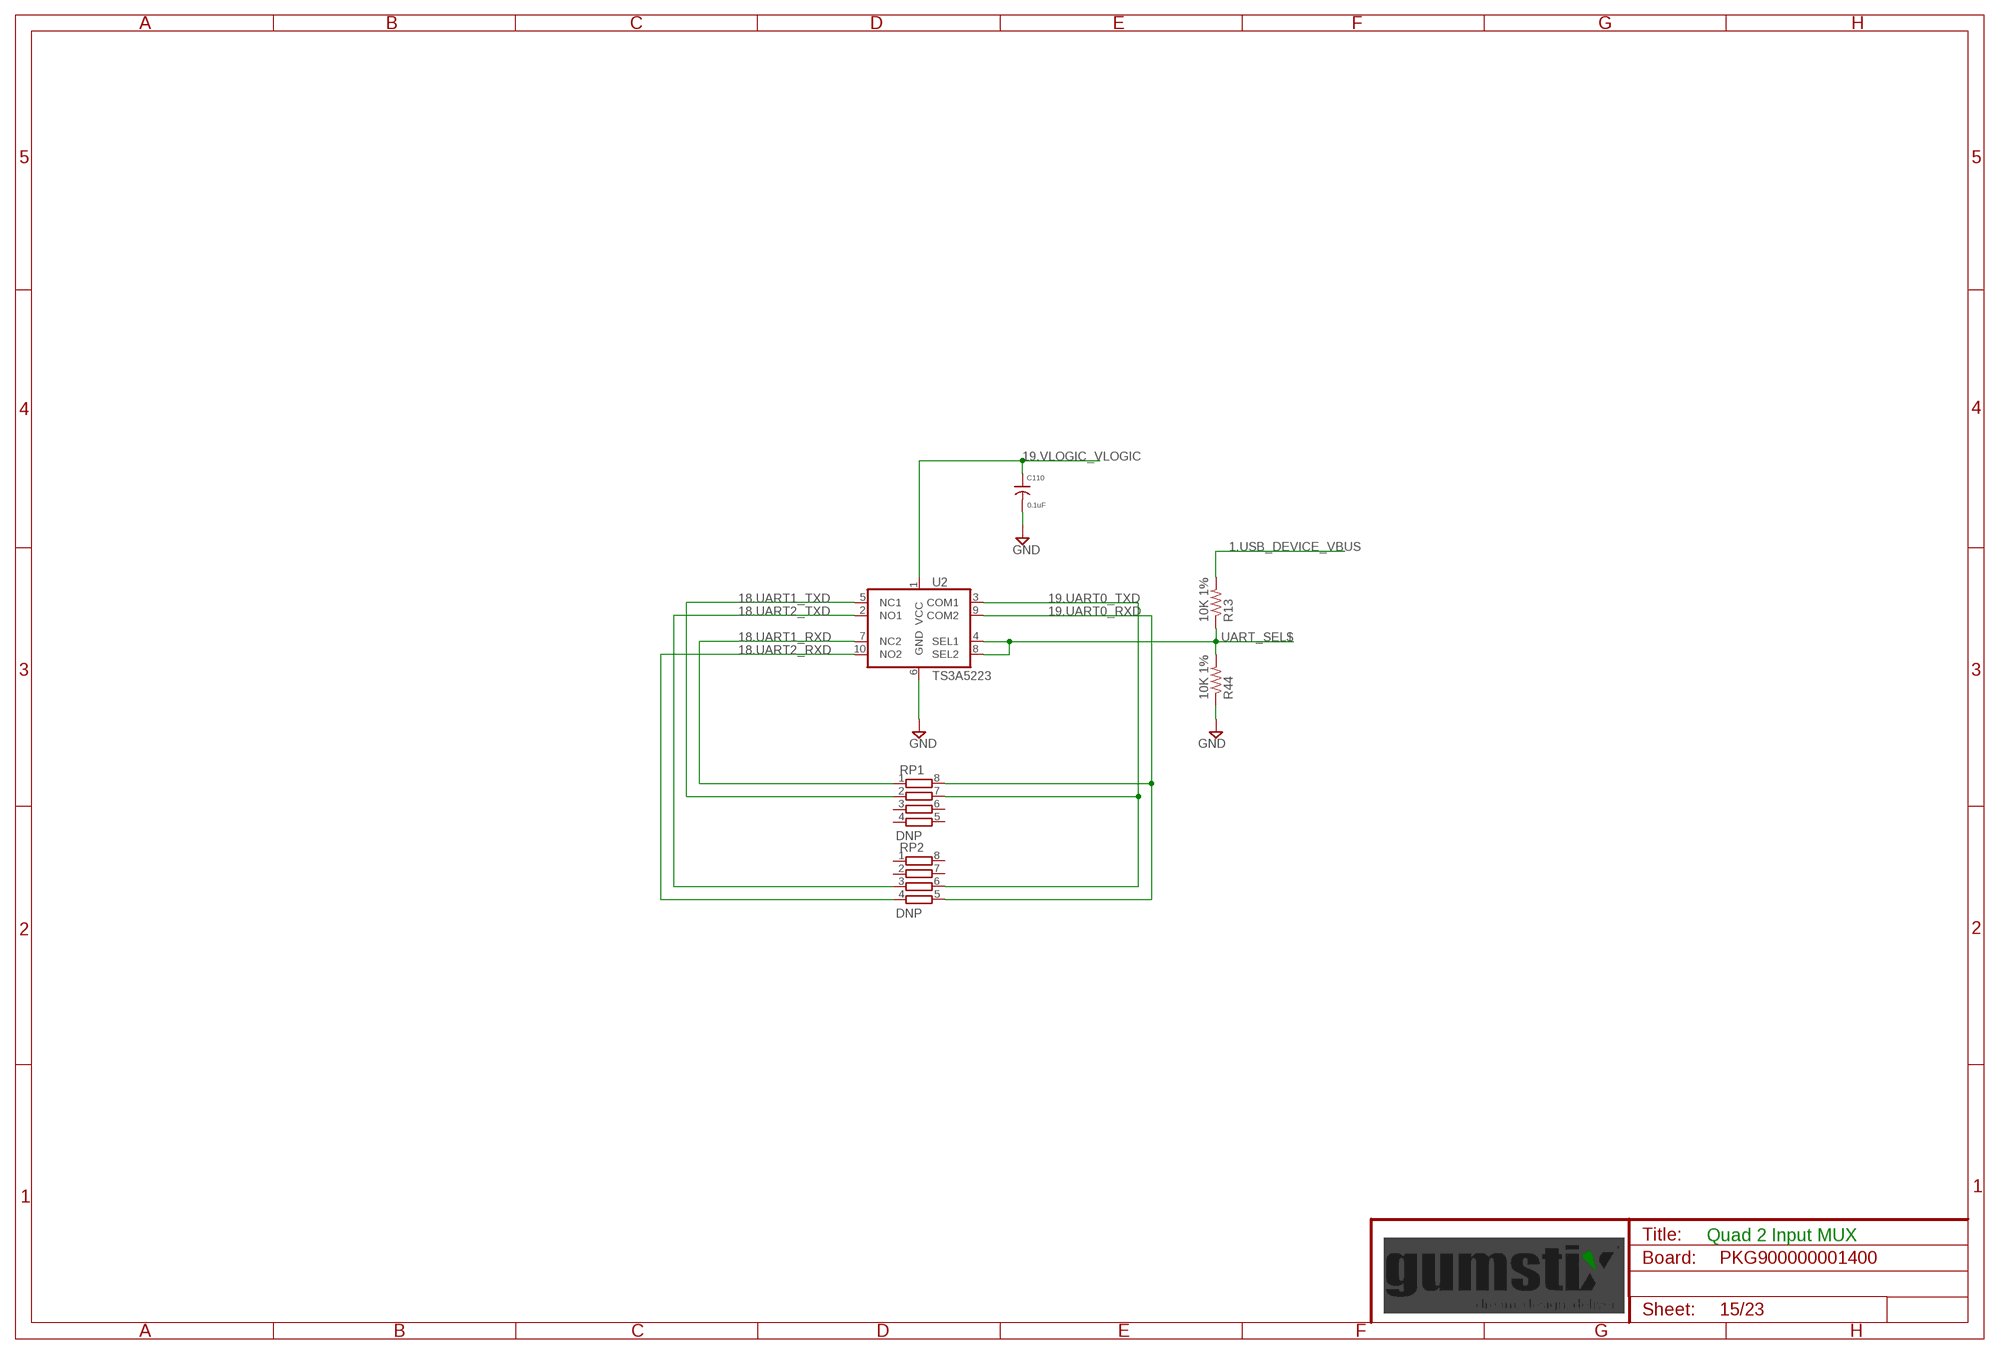
[diagram p14: schematic, sheet 15]
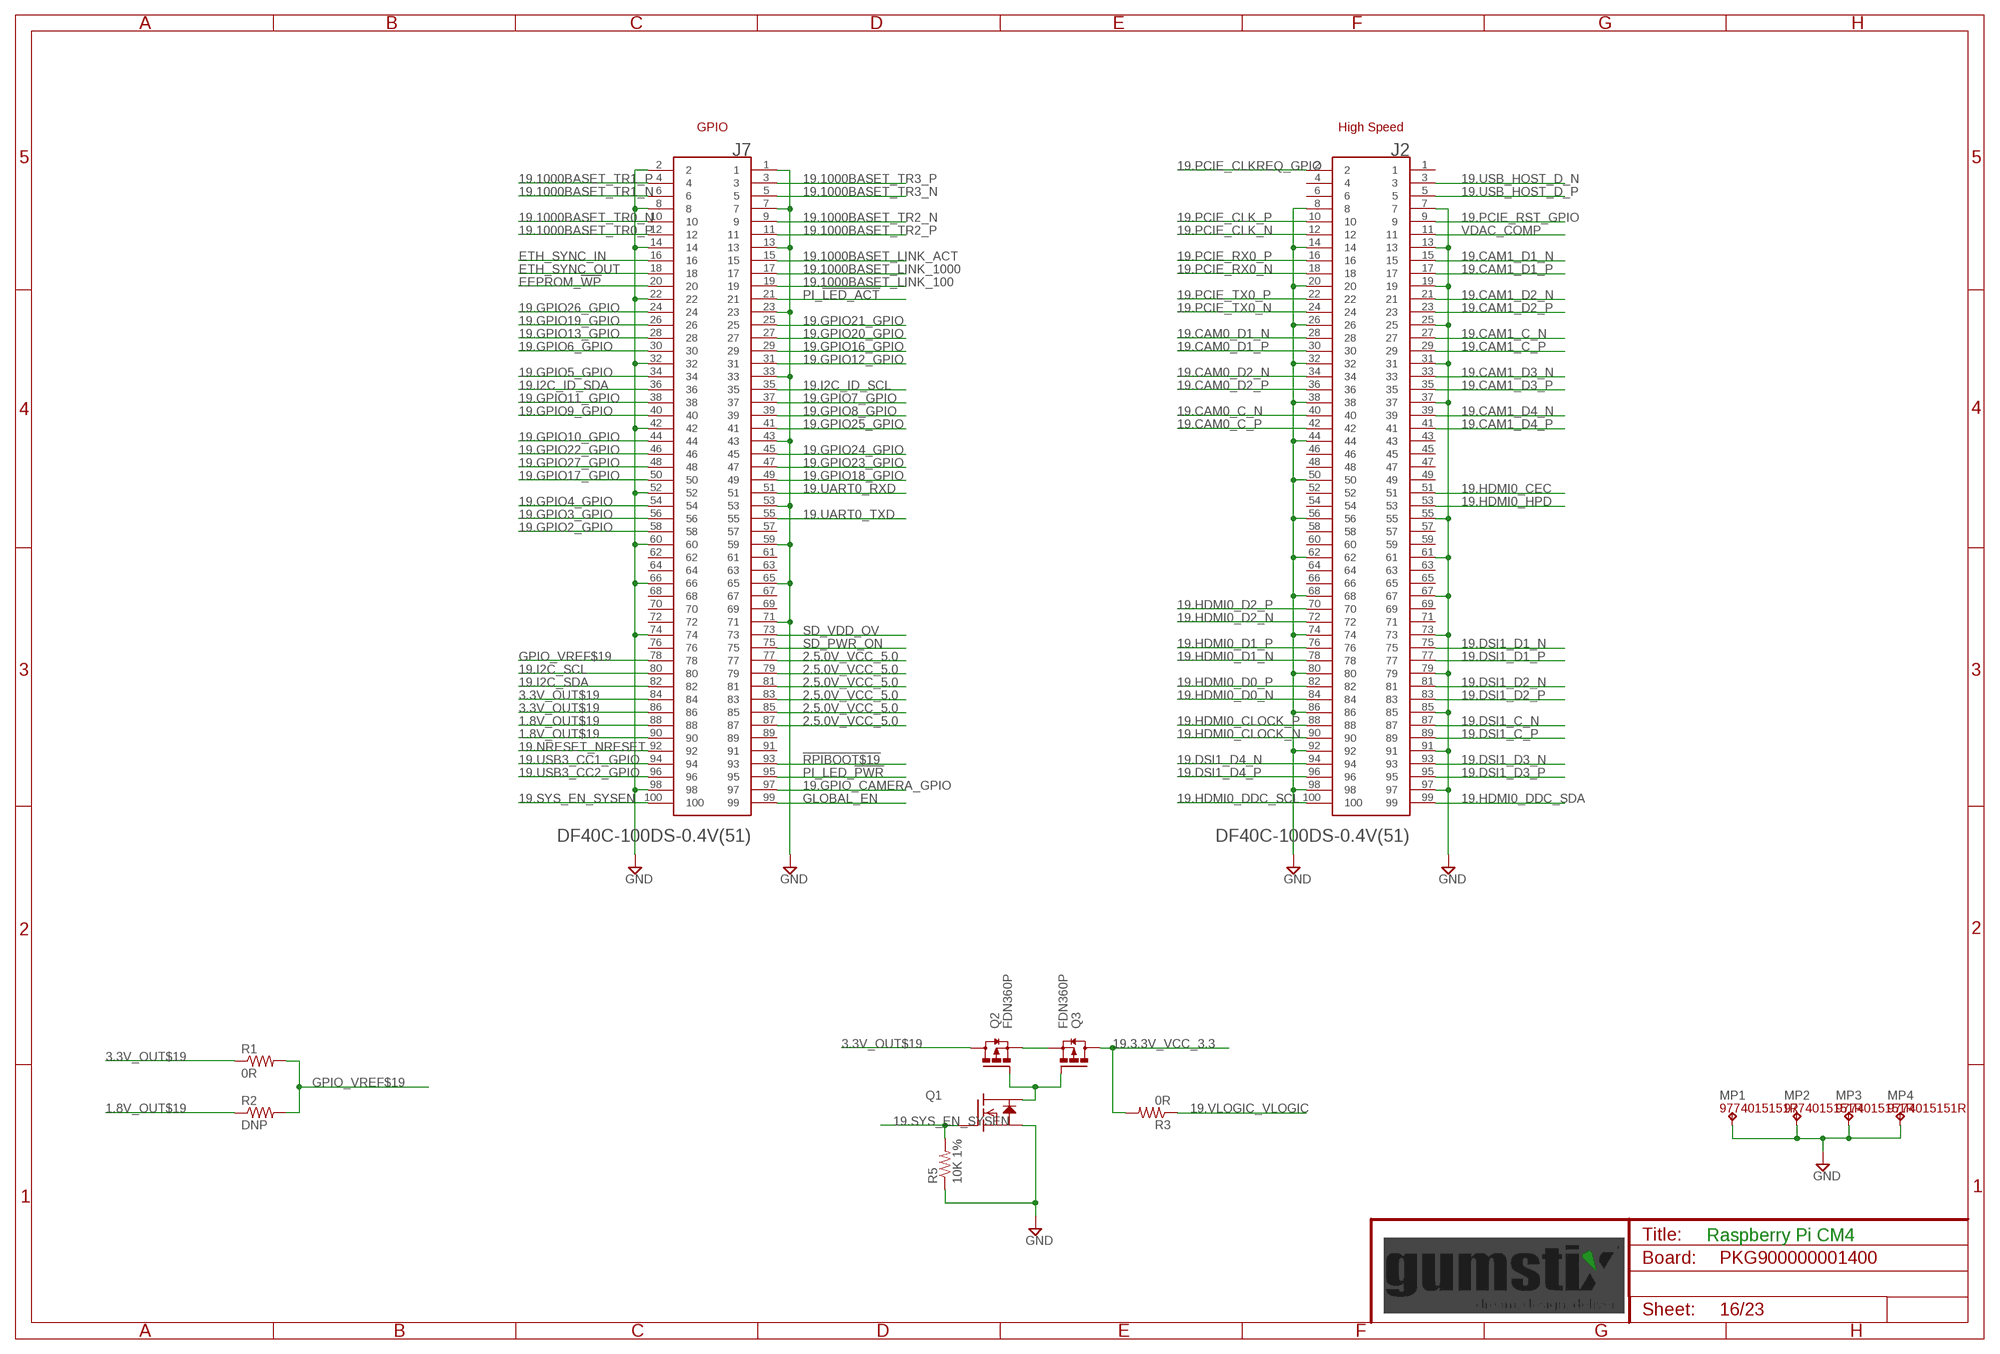
[diagram p15: schematic, sheet 16]
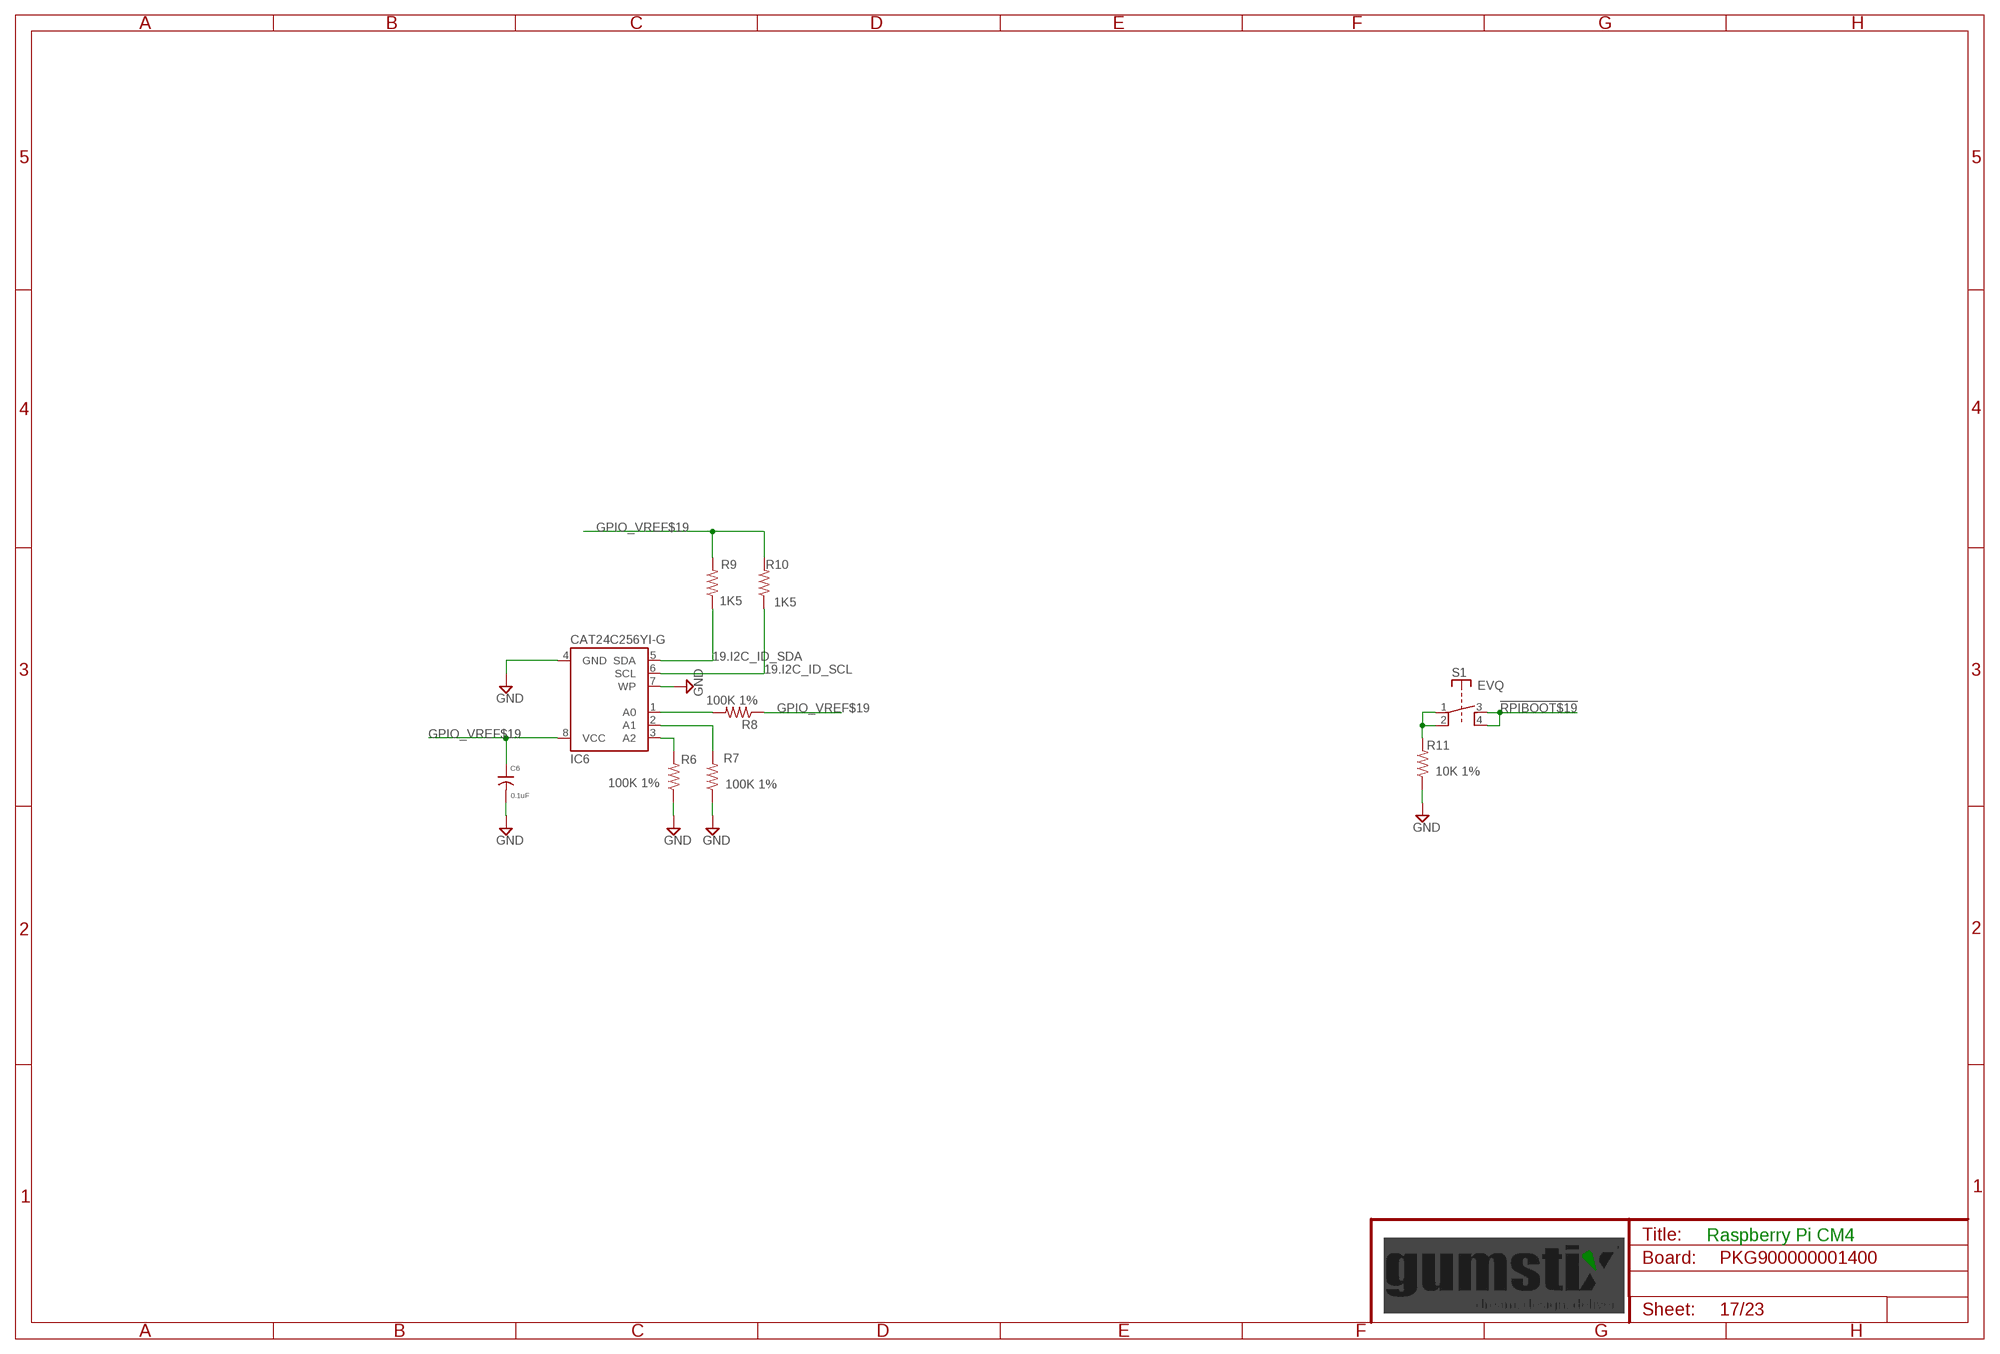
[diagram p16: schematic, sheet 17]
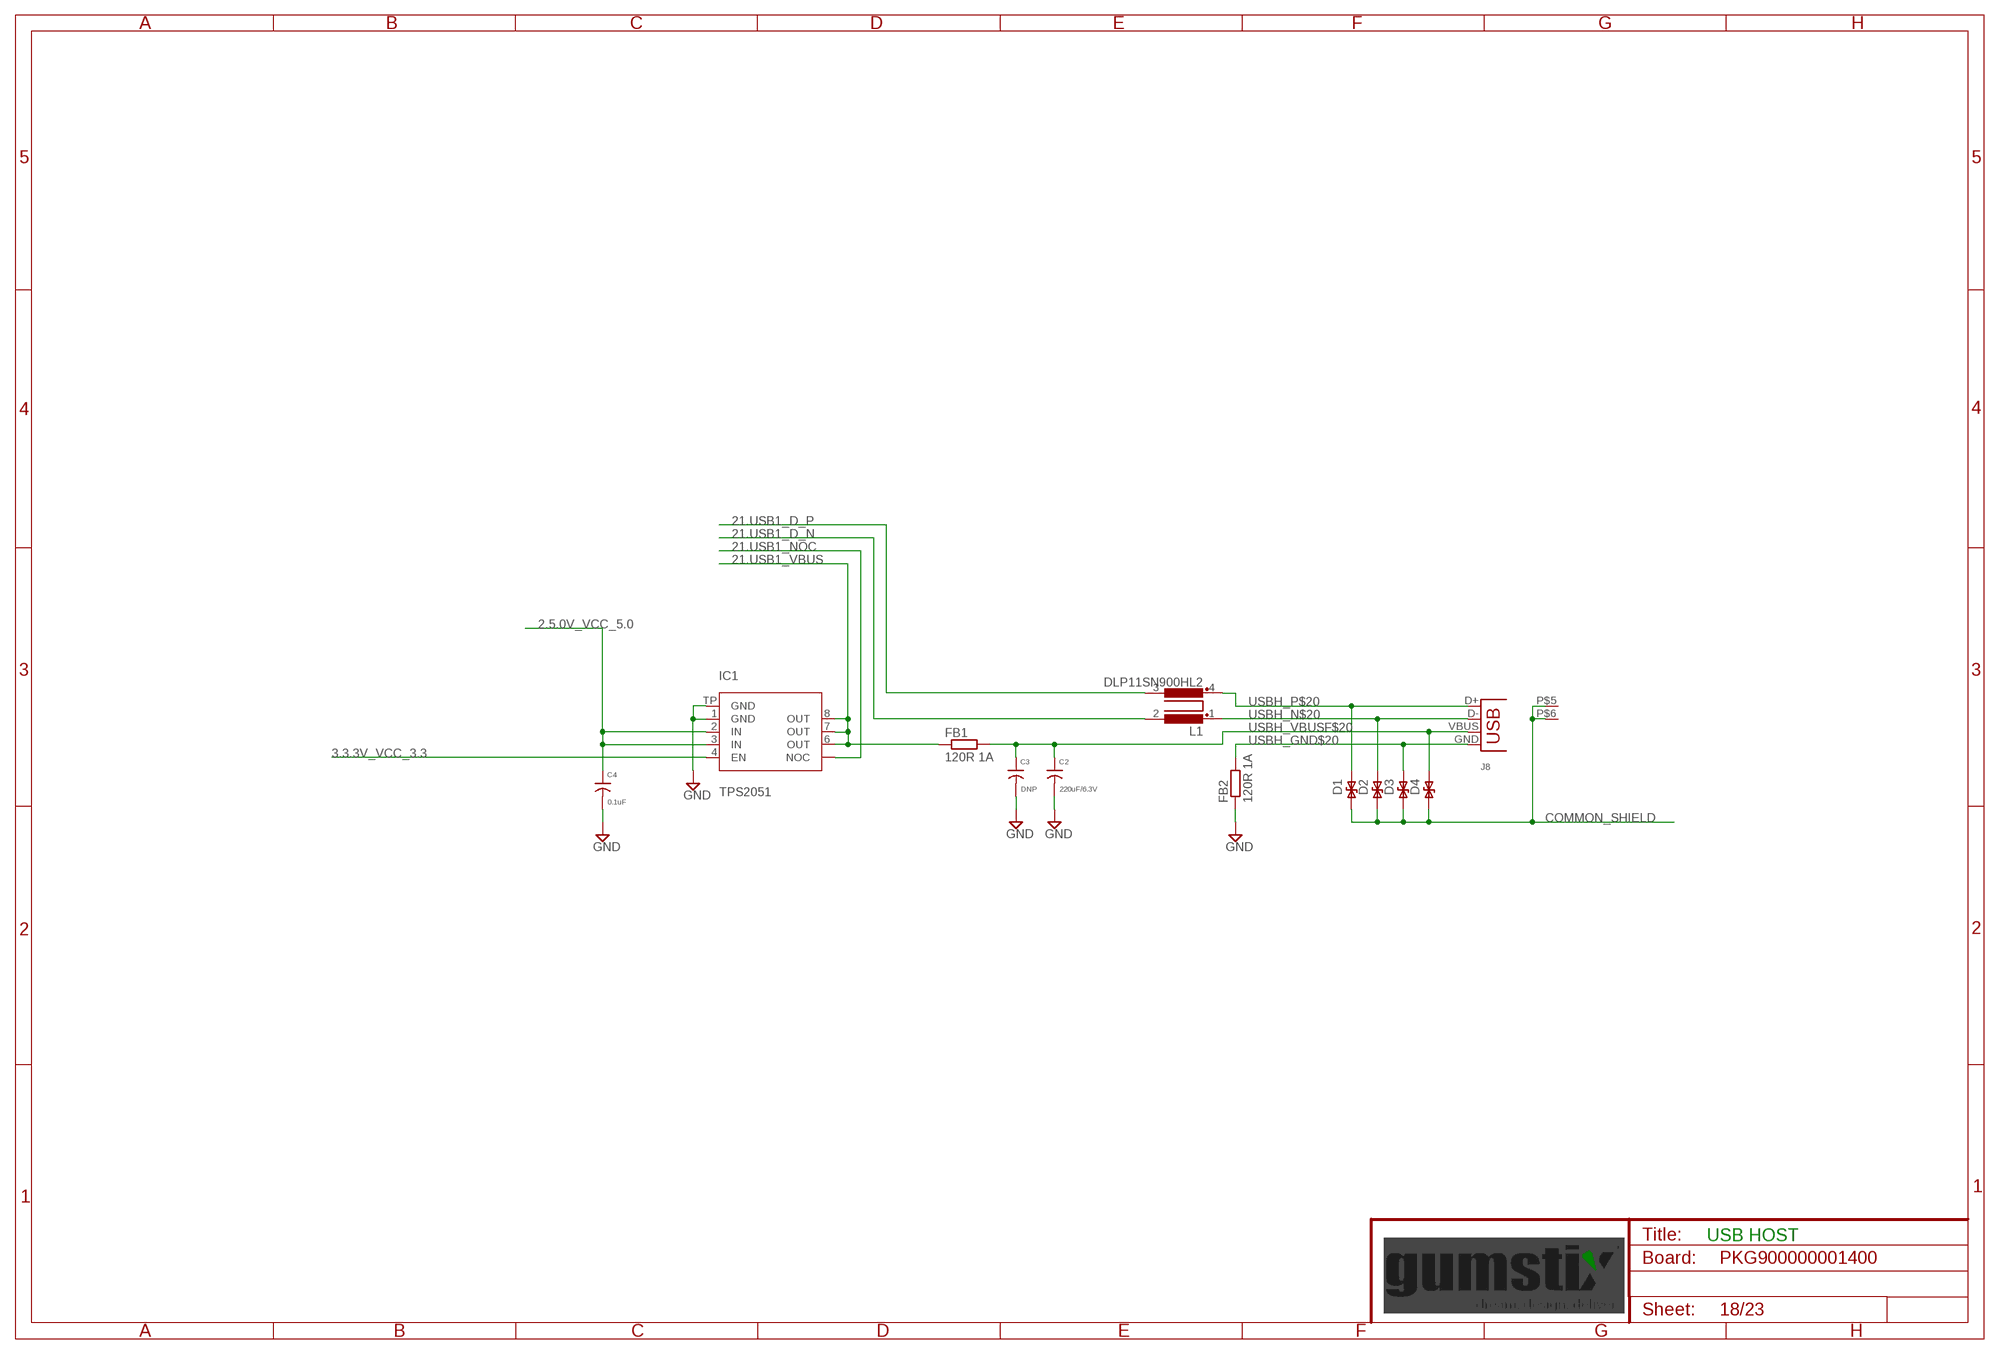
[diagram p17: schematic, sheet 18]
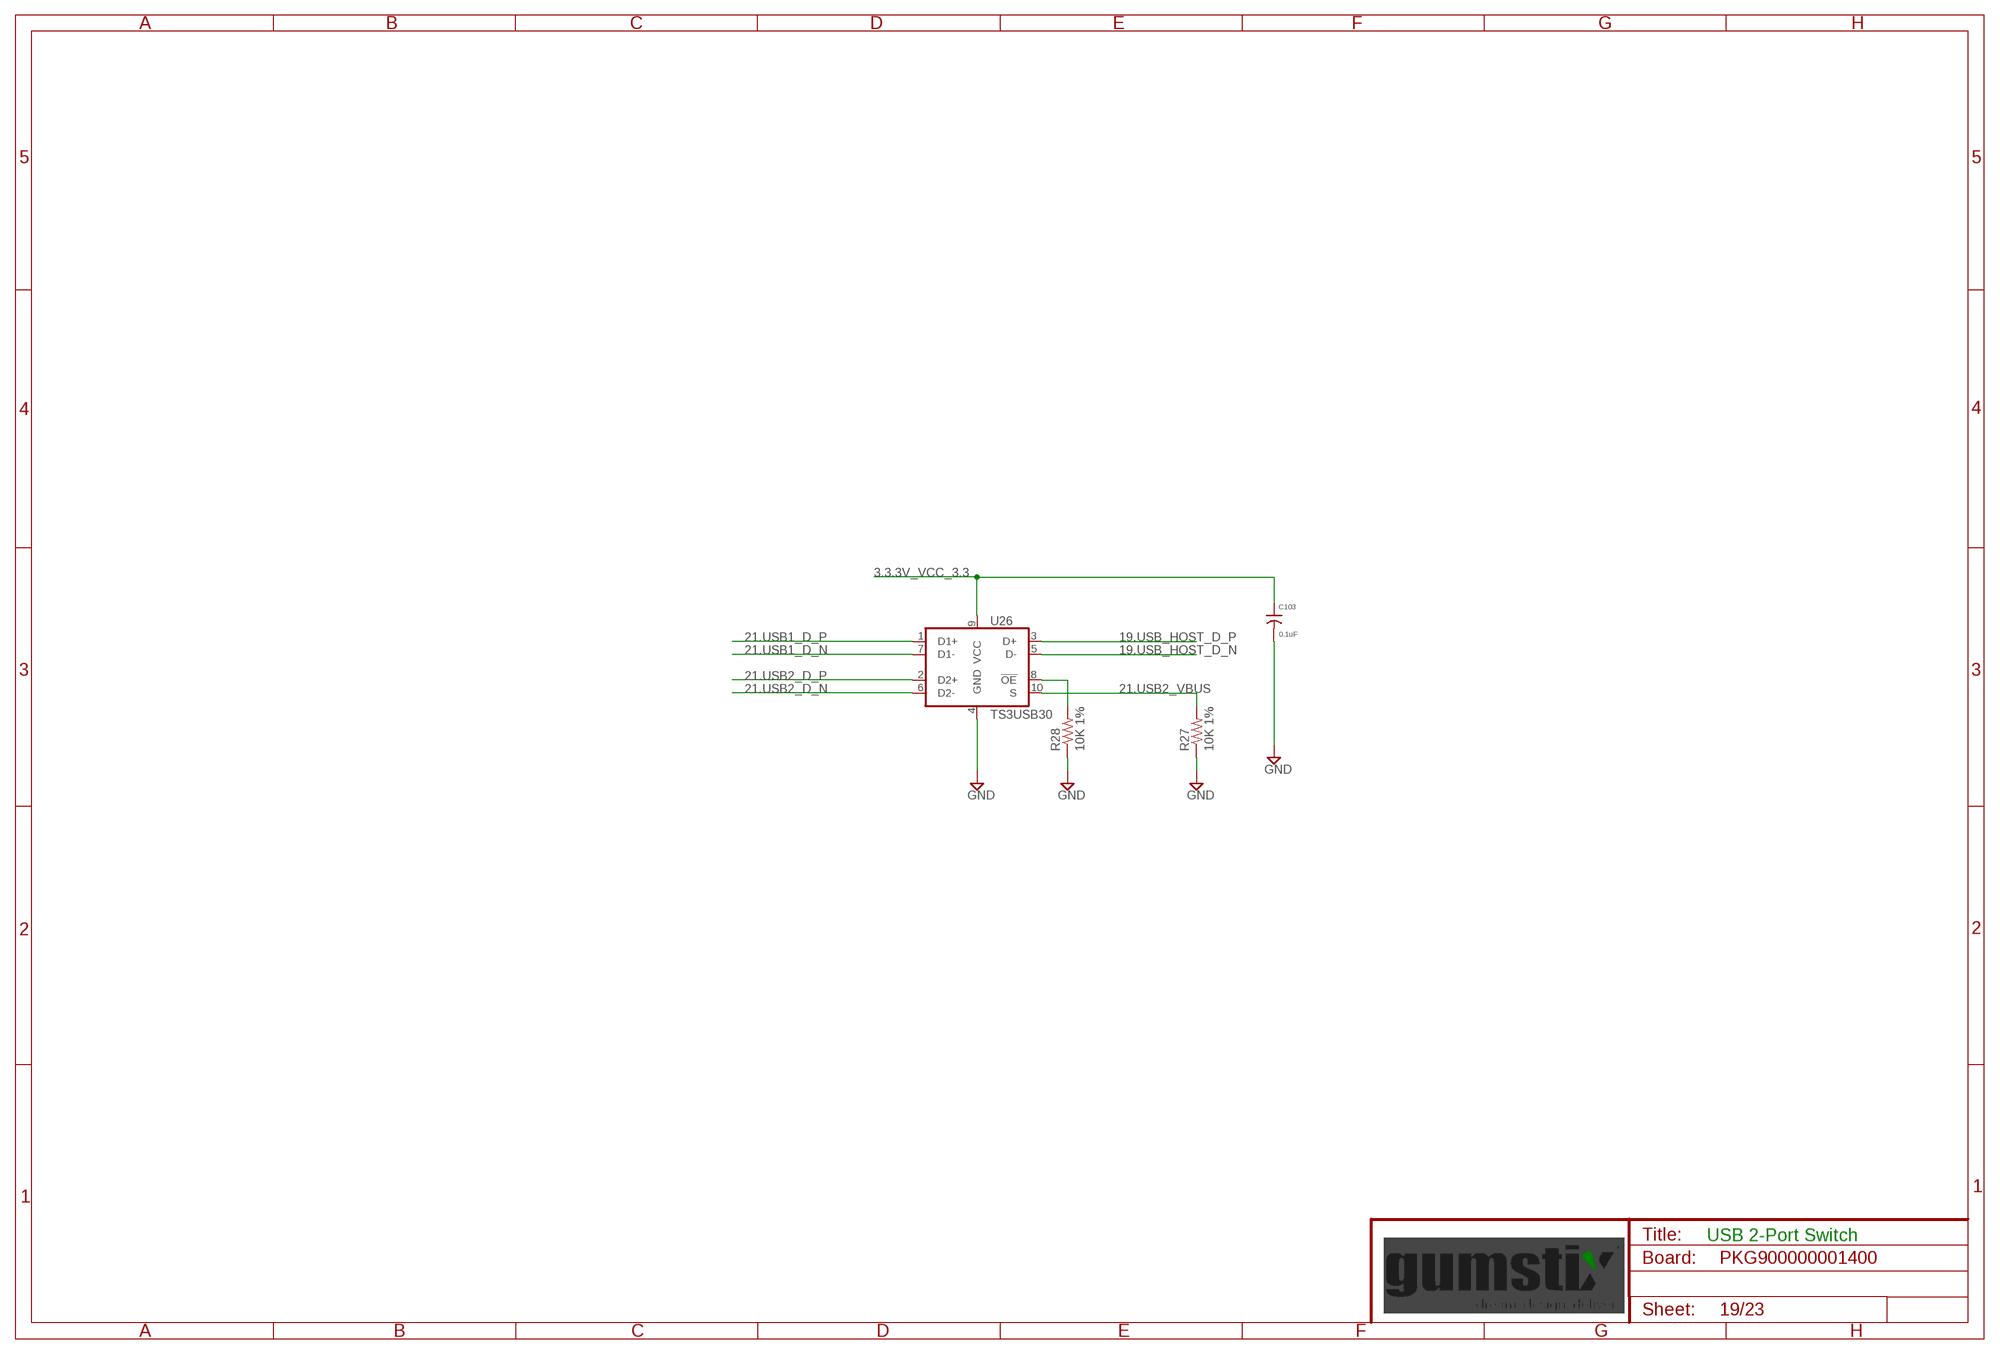
[diagram p18: schematic, sheet 19]
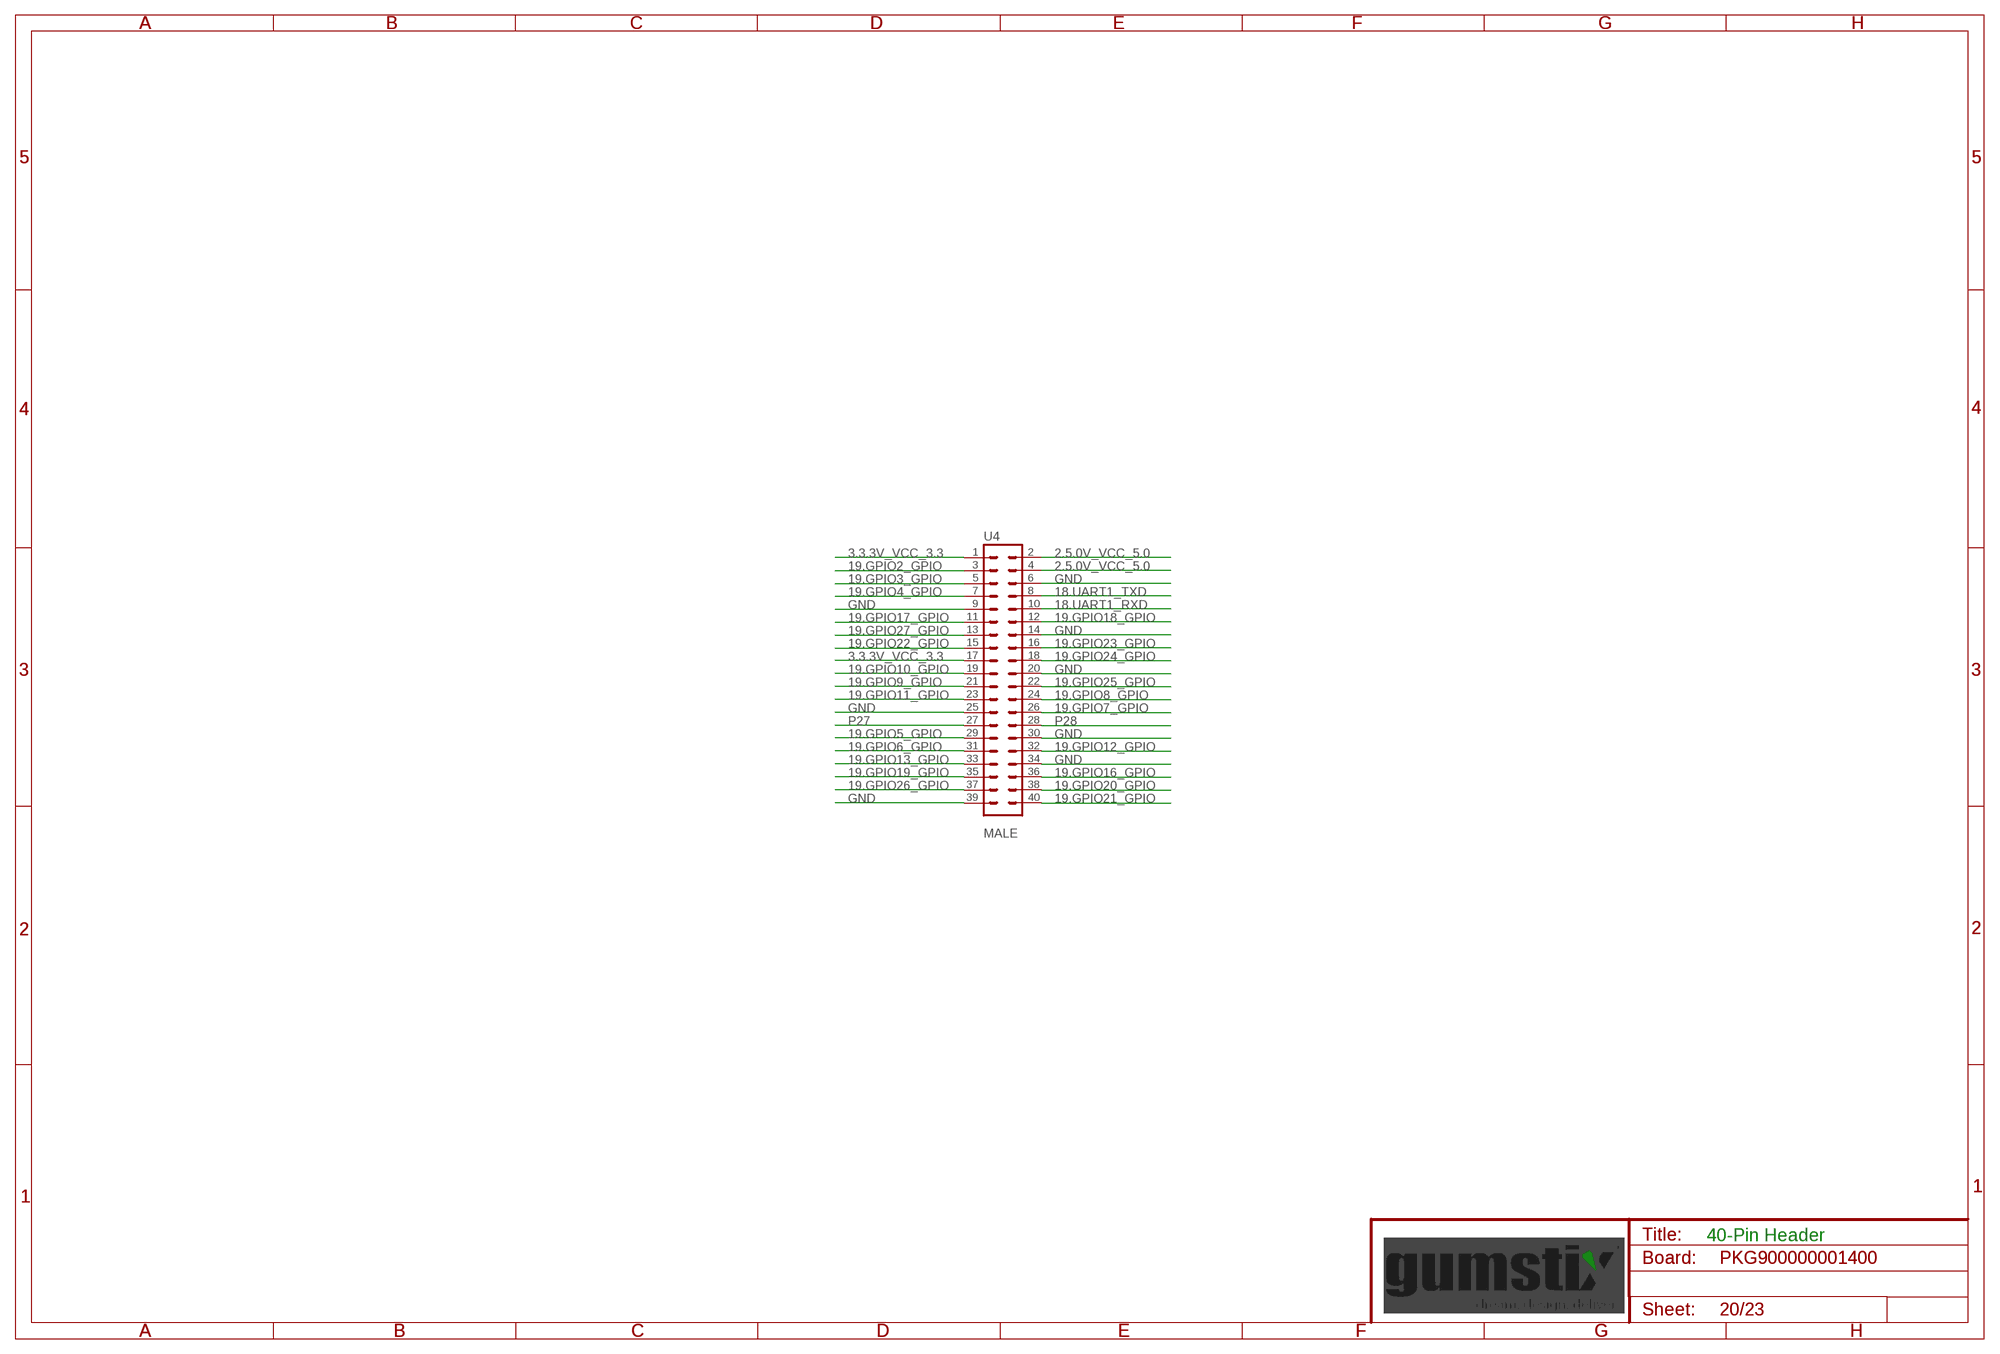
[diagram p19: schematic, sheet 20]
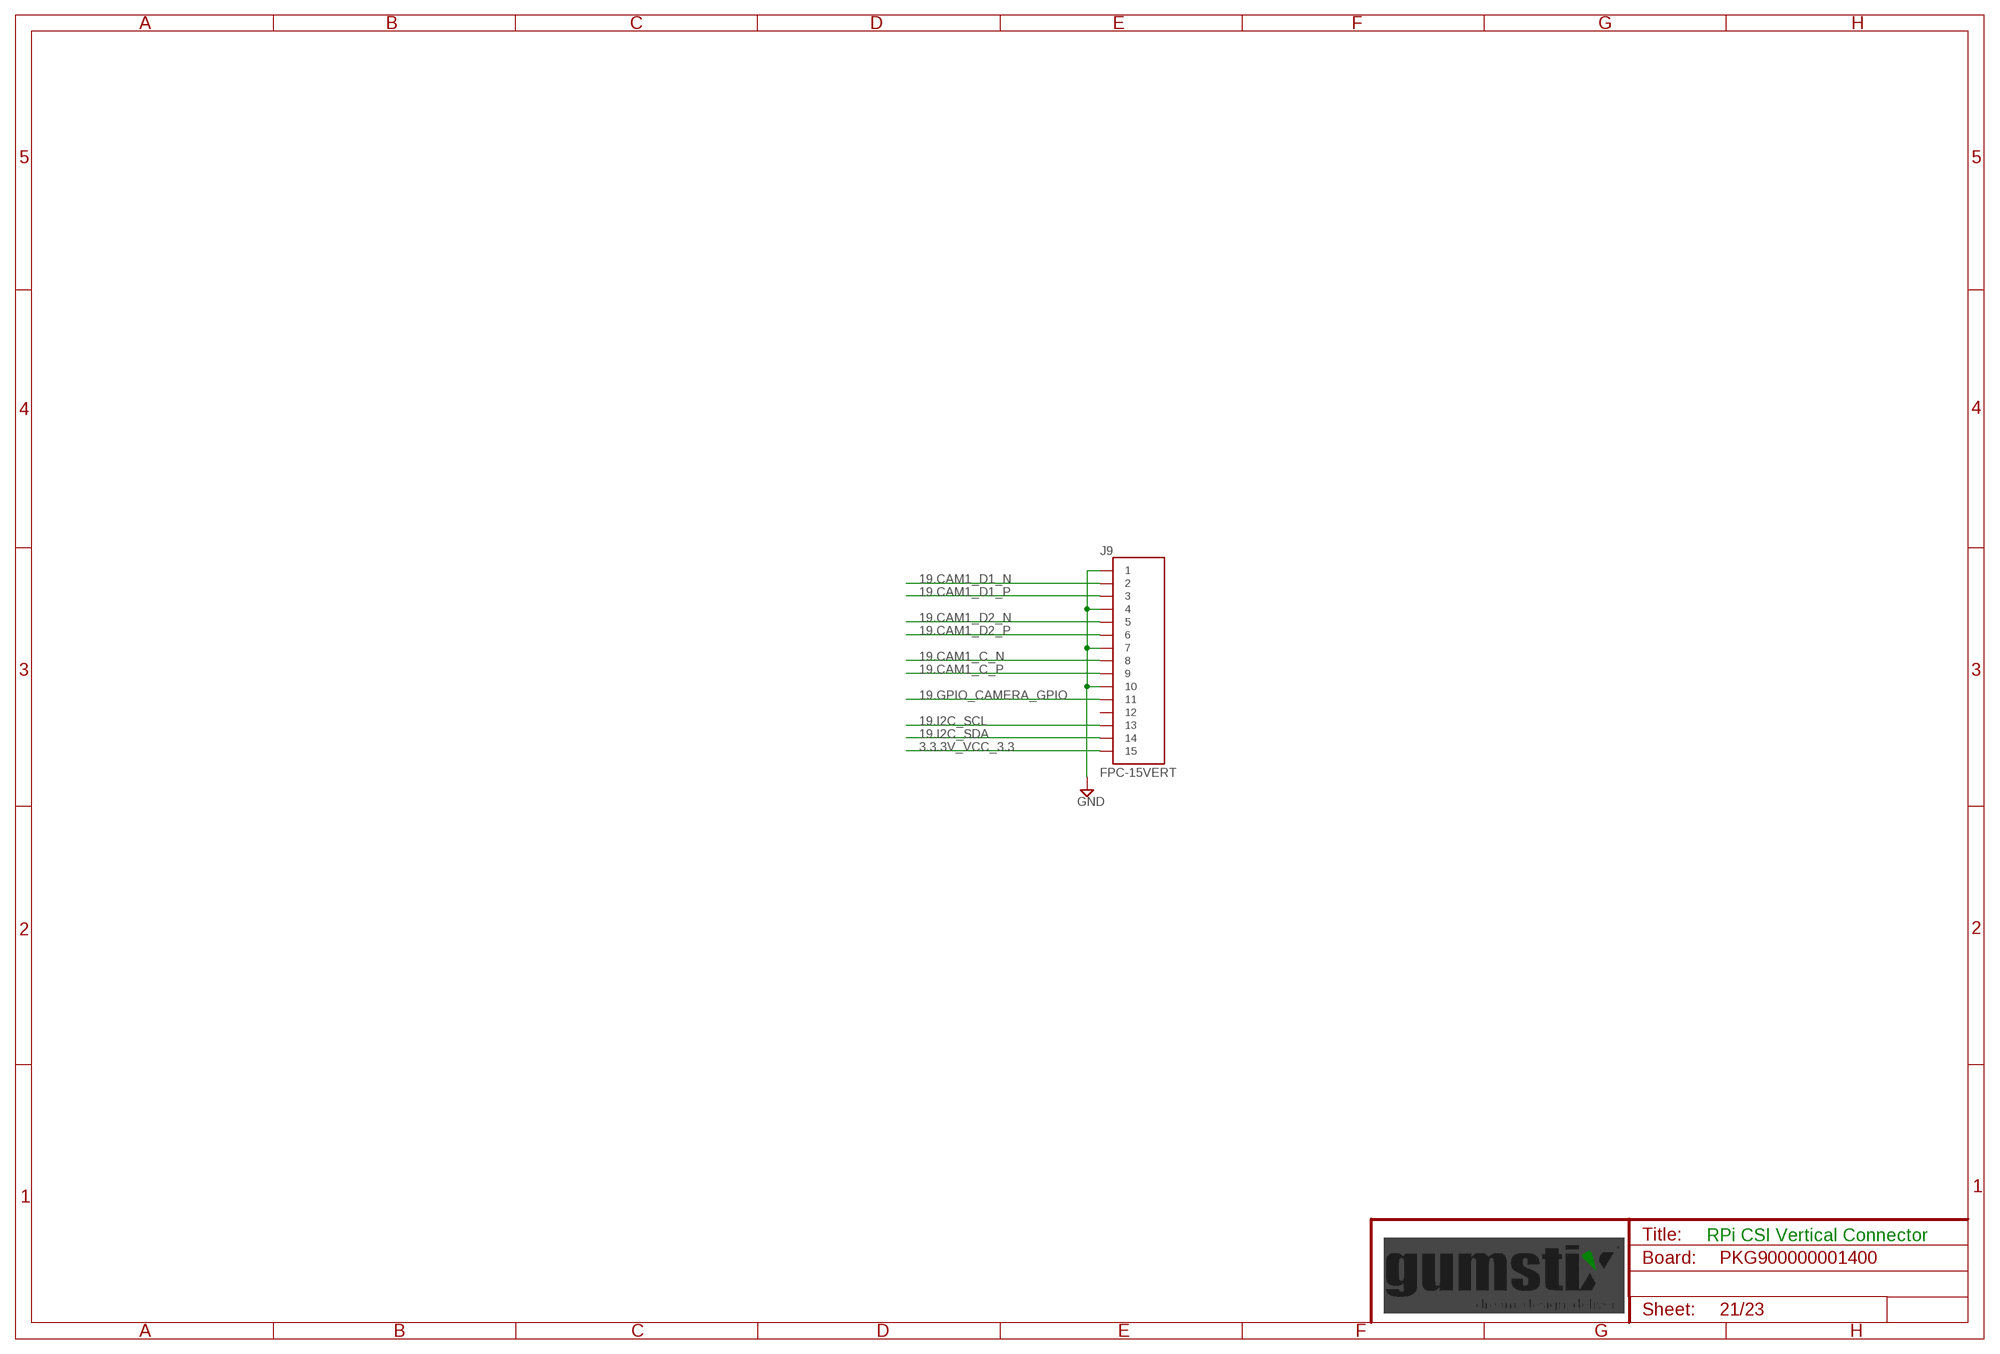
[diagram p20: schematic, sheet 21]
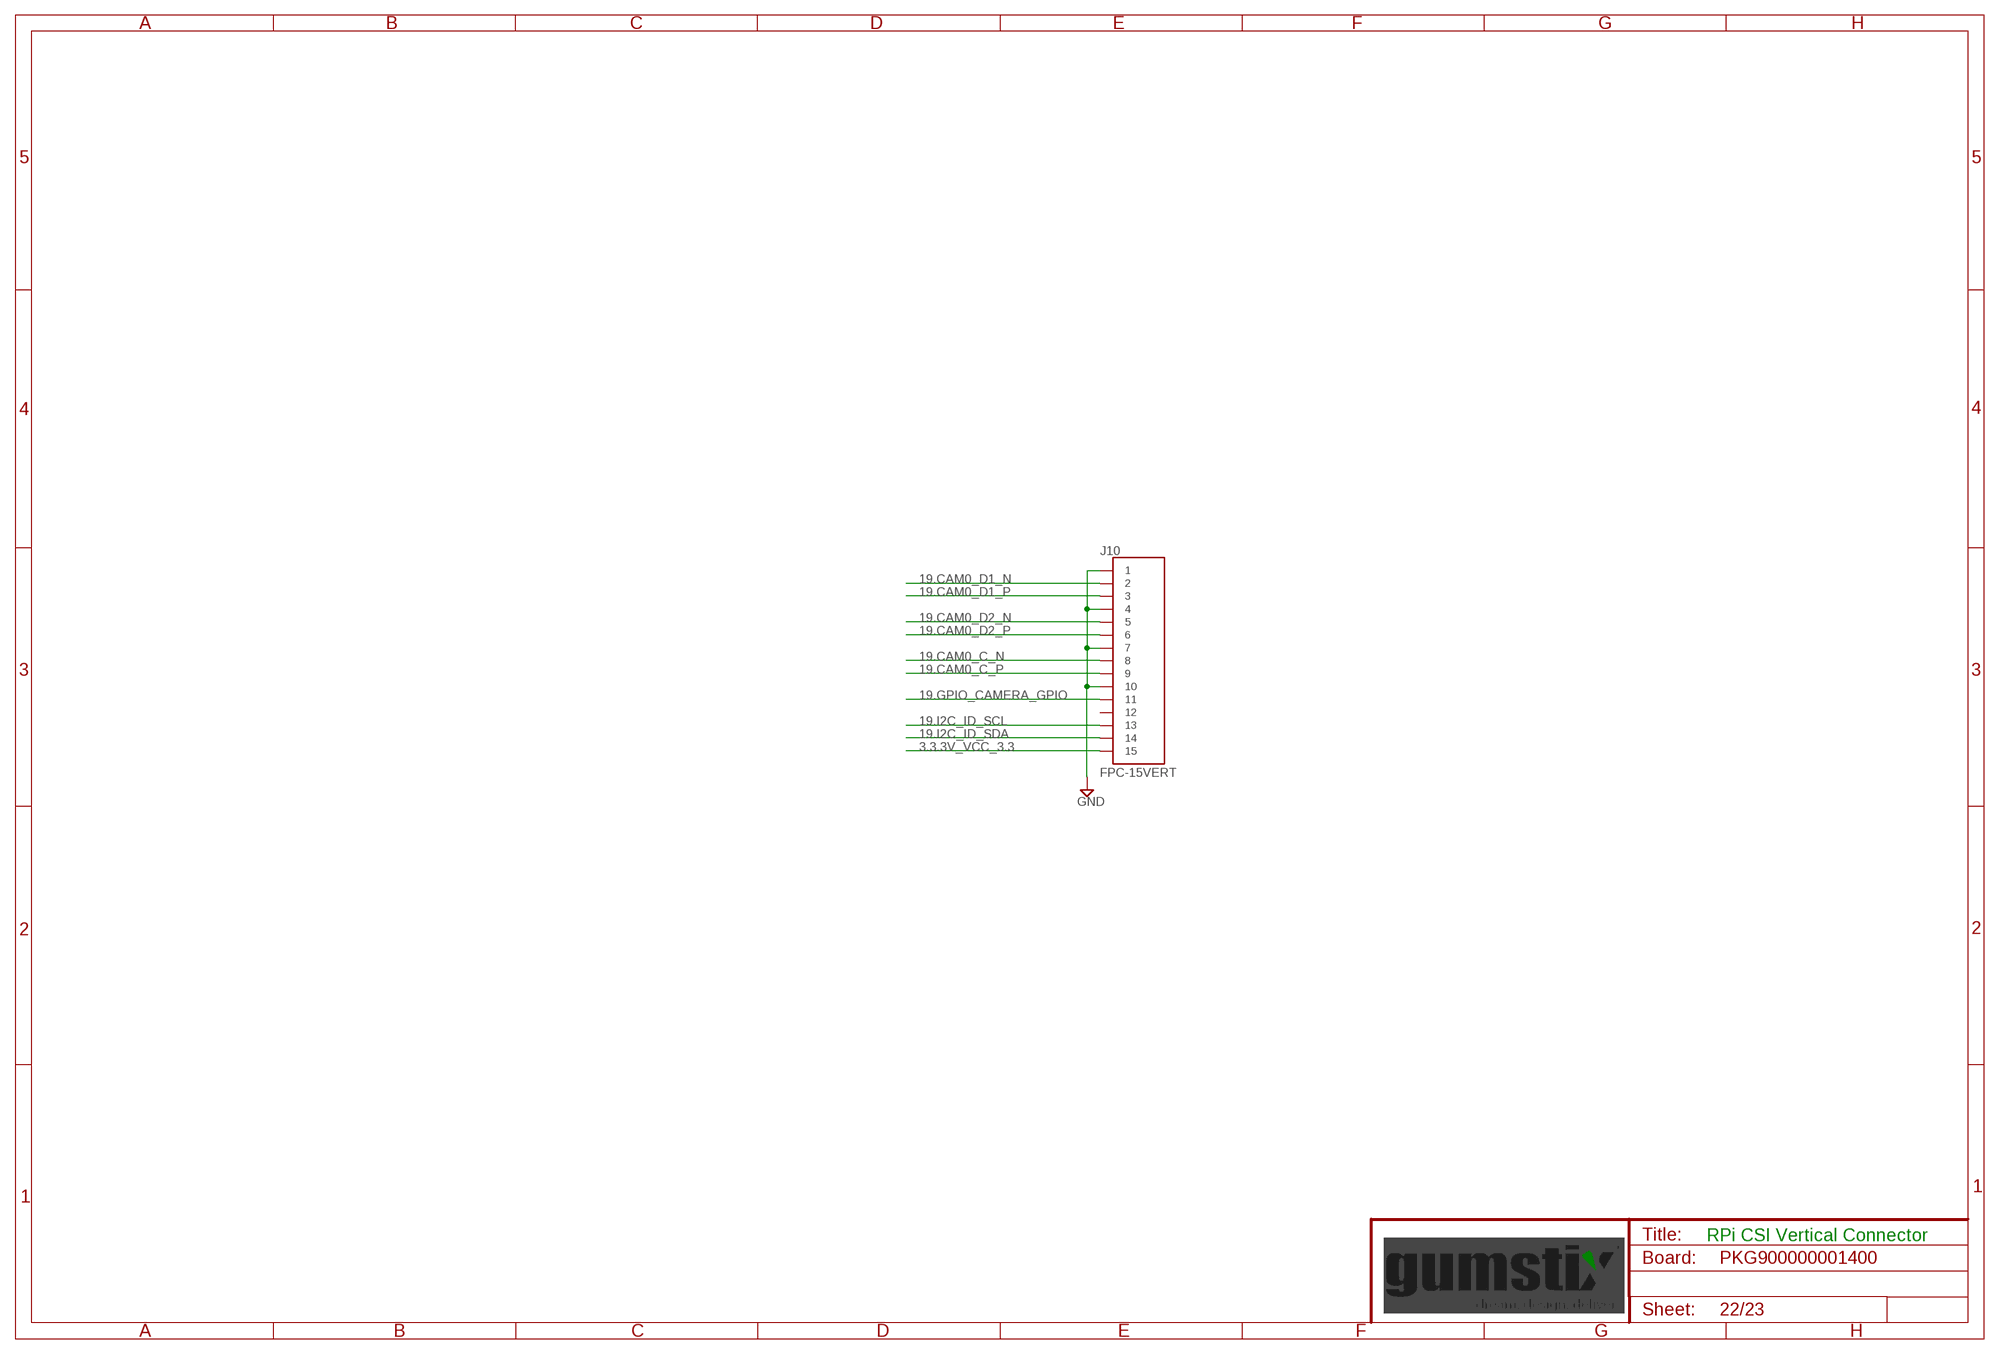
[diagram p21: schematic, sheet 22]
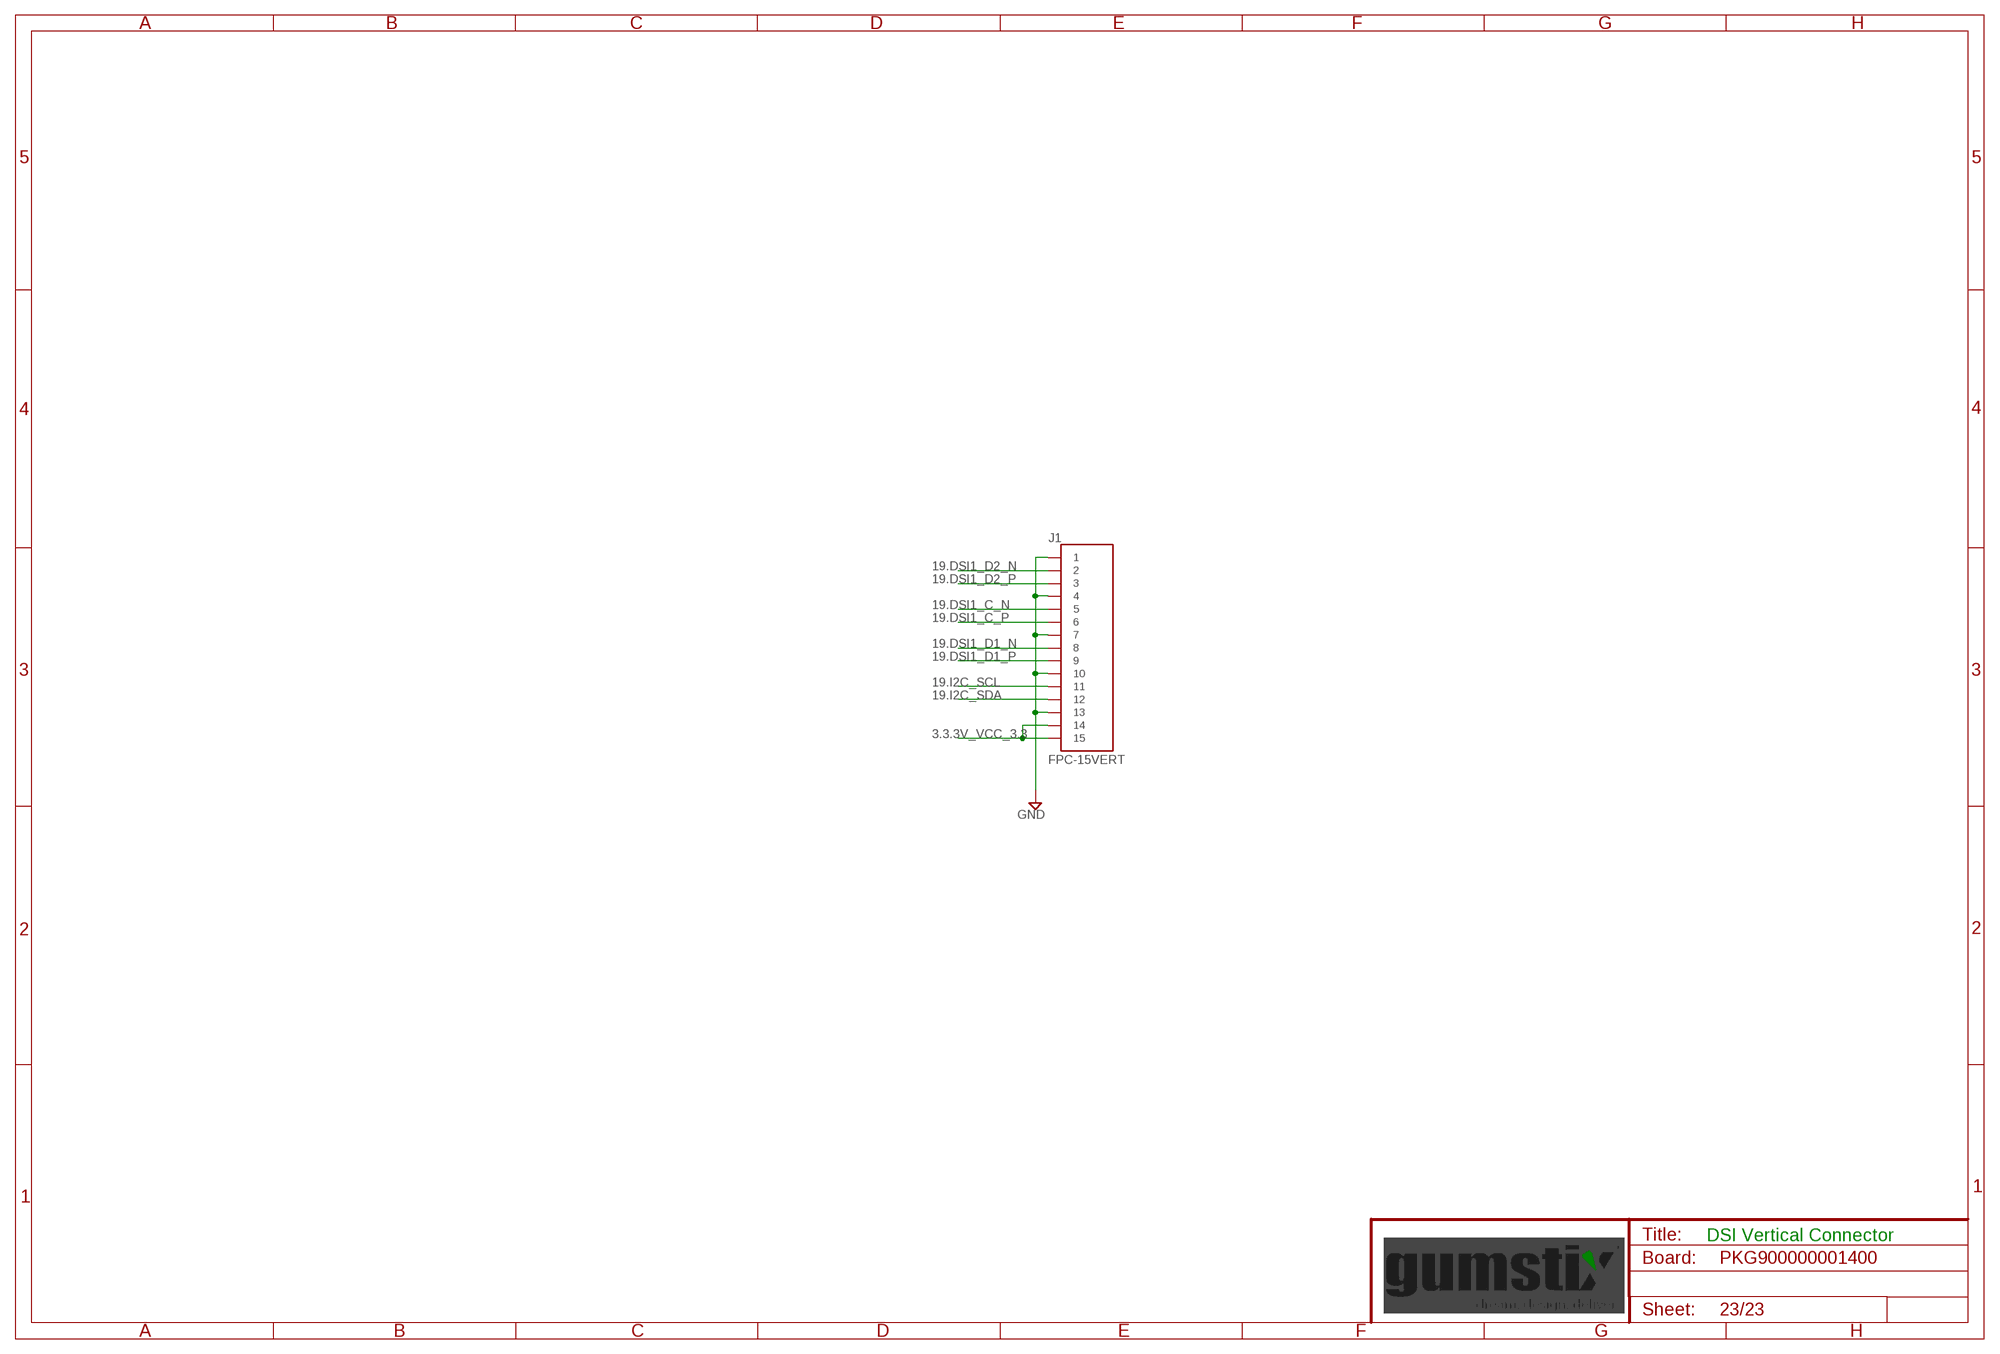
[diagram p22: schematic, sheet 23]

(export (version "E")
  (design (tool "Eeschema 10.0.6"))
  (components
    (comp (ref "C13")
      (value "10uF/50V")
      (footprint "eagle-import:1206")
      (libsource (lib "eagle-import") (part "C1206"))
    )
    (comp (ref "C30")
      (value "10nF")
      (footprint "eagle-import:0603")
      (libsource (lib "eagle-import") (part "C0603"))
    )
    (comp (ref "C52")
      (value "0.01uF")
      (footprint "eagle-import:0201")
      (libsource (lib "eagle-import") (part "C0201"))
    )
    (comp (ref "C78")
      (value "0.01uF")
      (footprint "eagle-import:0201")
      (libsource (lib "eagle-import") (part "C0201"))
    )
    (comp (ref "C79")
      (value "330uF")
      (footprint "eagle-import:PANASONIC_F")
      (libsource (lib "eagle-import") (part "CPANASONIC_F"))
    )
    (comp (ref "D6")
      (value "CDBC540-G")
      (footprint "eagle-import:DO-214AB")
      (libsource (lib "eagle-import") (part "SCHOTTKY-DIODE"))
    )
    (comp (ref "L6")
      (value "10uH")
      (footprint "eagle-import:3232DZ")
      (libsource (lib "eagle-import") (part "L3232DZ"))
    )
    (comp (ref "R12")
      (value "100K 1%")
      (footprint "eagle-import:0201")
      (libsource (lib "eagle-import") (part "R0201"))
    )
    (comp (ref "R17")
      (value "31K6")
      (footprint "eagle-import:0402")
      (libsource (lib "eagle-import") (part "R0402"))
    )
    (comp (ref "R18")
      (value "0R")
      (footprint "eagle-import:0805")
      (libsource (lib "eagle-import") (part "R0805"))
    )
    (comp (ref "TP1")
      (value "DNP")
      (footprint "eagle-import:TP0500")
      (libsource (lib "eagle-import") (part "TP05"))
    )
    (comp (ref "U7")
      (value "TPS5450")
      (footprint "eagle-import:8SO_POWERPAD")
      (libsource (lib "eagle-import") (part "TPS5450"))
    )
    (comp (ref "C98")
      (value "47pF")
      (footprint "eagle-import:0201")
      (libsource (lib "eagle-import") (part "C0201"))
    )
    (comp (ref "D9")
      (value "B72590D50A060")
      (footprint "eagle-import:D0402")
      (libsource (lib "eagle-import") (part "ESD-DIODE"))
    )
    (comp (ref "R30")
      (value "10K 1%")
      (footprint "eagle-import:0201")
      (libsource (lib "eagle-import") (part "R0201"))
    )
    (comp (ref "R31")
      (value "150R")
      (footprint "eagle-import:0201")
      (libsource (lib "eagle-import") (part "R0201"))
    )
    (comp (ref "S3")
      (value "EVQ")
      (footprint "eagle-import:EVQ")
      (libsource (lib "eagle-import") (part "EVQ"))
    )
    (comp (ref "D10")
      (value "RED")
      (footprint "eagle-import:D0603")
      (libsource (lib "eagle-import") (part "LED0603"))
    )
    (comp (ref "Q6")
      (value "BSS138")
      (footprint "eagle-import:SOT23")
      (libsource (lib "eagle-import") (part "BSS138"))
    )
    (comp (ref "R32")
      (value "1K")
      (footprint "eagle-import:0201")
      (libsource (lib "eagle-import") (part "R0201"))
    )
    (comp (ref "R33")
      (value "300R")
      (footprint "eagle-import:0402")
      (libsource (lib "eagle-import") (part "R0402"))
    )
    (comp (ref "R34")
      (value "100K 1%")
      (footprint "eagle-import:0201")
      (libsource (lib "eagle-import") (part "R0201"))
    )
    (comp (ref "C110")
      (value "0.1uF")
      (footprint "eagle-import:0201")
      (libsource (lib "eagle-import") (part "C0201"))
    )
    (comp (ref "R13")
      (value "10K 1%")
      (footprint "eagle-import:0201")
      (libsource (lib "eagle-import") (part "R0201"))
    )
    (comp (ref "R44")
      (value "10K 1%")
      (footprint "eagle-import:0201")
      (libsource (lib "eagle-import") (part "R0201"))
    )
    (comp (ref "RP1")
      (value "DNP")
      (footprint "eagle-import:RP741X083")
      (libsource (lib "eagle-import") (part "RP741X083"))
    )
    (comp (ref "RP2")
      (value "DNP")
      (footprint "eagle-import:RP741X083")
      (libsource (lib "eagle-import") (part "RP741X083"))
    )
    (comp (ref "U2")
      (value "TS3A5223")
      (footprint "eagle-import:UQFN-10")
      (libsource (lib "eagle-import") (part "TS3A5223"))
    )
    (comp (ref "C6")
      (value "0.1uF")
      (footprint "eagle-import:0201")
      (libsource (lib "eagle-import") (part "C0201"))
    )
    (comp (ref "IC6")
      (value "CAT24C256YI-G")
      (footprint "eagle-import:TSSOP8")
      (libsource (lib "eagle-import") (part "AT24CA"))
    )
    (comp (ref "R6")
      (value "100K 1%")
      (footprint "eagle-import:0201")
      (libsource (lib "eagle-import") (part "R0201"))
    )
    (comp (ref "R7")
      (value "100K 1%")
      (footprint "eagle-import:0201")
      (libsource (lib "eagle-import") (part "R0201"))
    )
    (comp (ref "R8")
      (value "100K 1%")
      (footprint "eagle-import:0201")
      (libsource (lib "eagle-import") (part "R0201"))
    )
    (comp (ref "R9")
      (value "1K5")
      (footprint "eagle-import:0201")
      (libsource (lib "eagle-import") (part "R0201"))
    )
    (comp (ref "R10")
      (value "1K5")
      (footprint "eagle-import:0201")
      (libsource (lib "eagle-import") (part "R0201"))
    )
    (comp (ref "R11")
      (value "10K 1%")
      (footprint "eagle-import:0201")
      (libsource (lib "eagle-import") (part "R0201"))
    )
    (comp (ref "S1")
      (value "EVQ")
      (footprint "eagle-import:KMT0")
      (libsource (lib "eagle-import") (part "EVQKMT0"))
    )
    (comp (ref "U4")
      (value "MALE")
      (footprint "eagle-import:2X20")
      (libsource (lib "eagle-import") (part "2X20_2.54X2.54MM_PITCH"))
    )
    (comp (ref "J10")
      (value "FPC-15VERT")
      (footprint "eagle-import:1-1734248-5")
      (libsource (lib "eagle-import") (part "FPC-15VERT"))
    )
    (comp (ref "J1")
      (value "FPC-15VERT")
      (footprint "eagle-import:1-1734248-5")
      (libsource (lib "eagle-import") (part "FPC-15VERT"))
    )
    (comp (ref "C88")
      (value "10uF")
      (footprint "eagle-import:0603")
      (libsource (lib "eagle-import") (part "C0603"))
    )
    (comp (ref "C89")
      (value "0.1uF")
      (footprint "eagle-import:0201")
      (libsource (lib "eagle-import") (part "C0201"))
    )
    (comp (ref "D7")
      (value "824501401")
      (footprint "eagle-import:SMAJ")
      (libsource (lib "eagle-import") (part "TVS-DIODESMA"))
    )
    (comp (ref "J3")
      (value "PJ-002A")
      (footprint "eagle-import:PJ-002A")
      (libsource (lib "eagle-import") (part "PJ-002A"))
    )
    (comp (ref "R22")
      (value "0R")
      (footprint "eagle-import:0201")
      (libsource (lib "eagle-import") (part "R0201"))
    )
    (comp (ref "C85")
      (value "0.1uF / 16V")
      (footprint "eagle-import:0402")
      (libsource (lib "eagle-import") (part "C0402"))
    )
    (comp (ref "C87")
      (value "10uF / 16V")
      (footprint "eagle-import:0805")
      (libsource (lib "eagle-import") (part "C0805"))
    )
    (comp (ref "C90")
      (value "1.0uF")
      (footprint "eagle-import:0402")
      (libsource (lib "eagle-import") (part "C0402"))
    )
    (comp (ref "C91")
      (value "10pF")
      (footprint "eagle-import:0201")
      (libsource (lib "eagle-import") (part "C0201"))
    )
    (comp (ref "C92")
      (value "22uF")
      (footprint "eagle-import:0805")
      (libsource (lib "eagle-import") (part "C0805"))
    )
    (comp (ref "IC4")
      (value "TPS62111")
      (footprint "eagle-import:PQFP16")
      (libsource (lib "eagle-import") (part "TPS62111"))
    )
    (comp (ref "L7")
      (value "6.8uH")
      (footprint "eagle-import:1515")
      (libsource (lib "eagle-import") (part "L1515"))
    )
    (comp (ref "R19")
      (value "1M0")
      (footprint "eagle-import:0201")
      (libsource (lib "eagle-import") (part "R0201"))
    )
    (comp (ref "R21")
      (value "0R")
      (footprint "eagle-import:0402")
      (libsource (lib "eagle-import") (part "R0402"))
    )
    (comp (ref "R24")
      (value "DNP")
      (footprint "eagle-import:0402")
      (libsource (lib "eagle-import") (part "R0402"))
    )
    (comp (ref "C97")
      (value "47pF")
      (footprint "eagle-import:0201")
      (libsource (lib "eagle-import") (part "C0201"))
    )
    (comp (ref "D8")
      (value "B72590D50A060")
      (footprint "eagle-import:D0402")
      (libsource (lib "eagle-import") (part "ESD-DIODE"))
    )
    (comp (ref "R50")
      (value "10K 1%")
      (footprint "eagle-import:0201")
      (libsource (lib "eagle-import") (part "R0201"))
    )
    (comp (ref "R51")
      (value "150R")
      (footprint "eagle-import:0201")
      (libsource (lib "eagle-import") (part "R0201"))
    )
    (comp (ref "S2")
      (value "EVQ")
      (footprint "eagle-import:EVQ")
      (libsource (lib "eagle-import") (part "EVQ"))
    )
    (comp (ref "C2")
      (value "220uF/6.3V")
      (footprint "eagle-import:1206")
      (libsource (lib "eagle-import") (part "C1206"))
    )
    (comp (ref "C3")
      (value "DNP")
      (footprint "eagle-import:1206")
      (libsource (lib "eagle-import") (part "C1206"))
    )
    (comp (ref "C4")
      (value "0.1uF")
      (footprint "eagle-import:0201")
      (libsource (lib "eagle-import") (part "C0201"))
    )
    (comp (ref "D1")
      (value "PS04LTVA1")
      (footprint "eagle-import:D0402")
      (libsource (lib "eagle-import") (part "ESD-DIODE"))
    )
    (comp (ref "D2")
      (value "PS04LTVA1")
      (footprint "eagle-import:D0402")
      (libsource (lib "eagle-import") (part "ESD-DIODE"))
    )
    (comp (ref "D3")
      (value "B72590D50A060")
      (footprint "eagle-import:D0402")
      (libsource (lib "eagle-import") (part "ESD-DIODE"))
    )
    (comp (ref "D4")
      (value "B72590D50A060")
      (footprint "eagle-import:D0402")
      (libsource (lib "eagle-import") (part "ESD-DIODE"))
    )
    (comp (ref "FB1")
      (value "120R 1A")
      (footprint "eagle-import:0402")
      (libsource (lib "eagle-import") (part "FB0402"))
    )
    (comp (ref "FB2")
      (value "120R 1A")
      (footprint "eagle-import:0402")
      (libsource (lib "eagle-import") (part "FB0402"))
    )
    (comp (ref "IC1")
      (value "TPS2051")
      (footprint "eagle-import:MSOP8-PAD")
      (libsource (lib "eagle-import") (part "TPS2051"))
    )
    (comp (ref "J8")
      (value "USB-A-S")
      (footprint "eagle-import:USB-A-S")
      (libsource (lib "eagle-import") (part "USB-A-S-A-S"))
    )
    (comp (ref "L1")
      (value "DLP11SN900HL2")
      (footprint "eagle-import:0504-DLP11S")
      (libsource (lib "eagle-import") (part "COM_MODE_CHOKE"))
    )
    (comp (ref "C86")
      (value "4.7uF")
      (footprint "eagle-import:0603")
      (libsource (lib "eagle-import") (part "C0603"))
    )
    (comp (ref "D11")
      (value "PS04LTVA1")
      (footprint "eagle-import:D0402")
      (libsource (lib "eagle-import") (part "ESD-DIODE"))
    )
    (comp (ref "D12")
      (value "PS04LTVA1")
      (footprint "eagle-import:D0402")
      (libsource (lib "eagle-import") (part "ESD-DIODE"))
    )
    (comp (ref "D13")
      (value "B72590D50A060")
      (footprint "eagle-import:D0402")
      (libsource (lib "eagle-import") (part "ESD-DIODE"))
    )
    (comp (ref "D14")
      (value "B72590D50A060")
      (footprint "eagle-import:D0402")
      (libsource (lib "eagle-import") (part "ESD-DIODE"))
    )
    (comp (ref "J6")
      (value "USB_MICRO_B")
      (footprint "eagle-import:USB_MICRO_B")
      (libsource (lib "eagle-import") (part "USB_MICRO_B"))
    )
    (comp (ref "L8")
      (value "DLP11SN900HL2")
      (footprint "eagle-import:0504-DLP11S")
      (libsource (lib "eagle-import") (part "COM_MODE_CHOKE"))
    )
    (comp (ref "R20")
      (value "0R")
      (footprint "eagle-import:0201")
      (libsource (lib "eagle-import") (part "R0201"))
    )
    (comp (ref "C5")
      (value "0.1uF")
      (footprint "eagle-import:0201")
      (libsource (lib "eagle-import") (part "C0201"))
    )
    (comp (ref "C15")
      (value "0.1uF")
      (footprint "eagle-import:0201")
      (libsource (lib "eagle-import") (part "C0201"))
    )
    (comp (ref "C105")
      (value "0.1uF")
      (footprint "eagle-import:0201")
      (libsource (lib "eagle-import") (part "C0201"))
    )
    (comp (ref "C106")
      (value "0.1uF")
      (footprint "eagle-import:0201")
      (libsource (lib "eagle-import") (part "C0201"))
    )
    (comp (ref "C107")
      (value "0.01uF")
      (footprint "eagle-import:0201")
      (libsource (lib "eagle-import") (part "C0201"))
    )
    (comp (ref "C108")
      (value "0.1uF")
      (footprint "eagle-import:0201")
      (libsource (lib "eagle-import") (part "C0201"))
    )
    (comp (ref "C109")
      (value "0.01uF")
      (footprint "eagle-import:0201")
      (libsource (lib "eagle-import") (part "C0201"))
    )
    (comp (ref "L2")
      (value "DLP11SN900HL2")
      (footprint "eagle-import:0504-DLP11S")
      (libsource (lib "eagle-import") (part "COM_MODE_CHOKE"))
    )
    (comp (ref "L3")
      (value "DLP11SN900HL2")
      (footprint "eagle-import:0504-DLP11S")
      (libsource (lib "eagle-import") (part "COM_MODE_CHOKE"))
    )
    (comp (ref "L4")
      (value "DLP11SN900HL2")
      (footprint "eagle-import:0504-DLP11S")
      (libsource (lib "eagle-import") (part "COM_MODE_CHOKE"))
    )
    (comp (ref "L9")
      (value "DLP11SN900HL2")
      (footprint "eagle-import:0504-DLP11S")
      (libsource (lib "eagle-import") (part "COM_MODE_CHOKE"))
    )
    (comp (ref "R38")
      (value "75R")
      (footprint "eagle-import:0402")
      (libsource (lib "eagle-import") (part "R0402"))
    )
    (comp (ref "RP3")
      (value "DNP")
      (footprint "eagle-import:741X08")
      (libsource (lib "eagle-import") (part "RP741X083741X08"))
    )
    (comp (ref "U$29")
      (value "TXS0104E")
      (footprint "eagle-import:S-PVQFN-N14")
      (libsource (lib "eagle-import") (part "TXS0104E"))
    )
    (comp (ref "U3")
      (value "HDMI")
      (footprint "eagle-import:47151-001")
      (libsource (lib "eagle-import") (part "HDMI"))
    )
    (comp (ref "U8")
      (value "TPD13S523TSSOP")
      (footprint "eagle-import:TSSOP16")
      (libsource (lib "eagle-import") (part "TPD13S523TSSOP"))
    )
    (comp (ref "J2")
      (value "DF40C-100DS-0.4V(51)")
      (footprint "eagle-import:HRS_DF40C-100DS-0.4V(51)")
      (fields
        (field (name "DIGI-KEY_PART_NUMBER") "H11615CT-ND")
        (field (name "MF") "Hirose")
        (field (name "MP") "DF40C-100DS-0.4V_51_")
      )
      (libsource (lib "eagle-import") (part "DF40C-100DS-0.4V(51)"))
    )
    (comp (ref "J7")
      (value "DF40C-100DS-0.4V(51)")
      (footprint "eagle-import:HRS_DF40C-100DS-0.4V(51)")
      (fields
        (field (name "DIGI-KEY_PART_NUMBER") "H11615CT-ND")
        (field (name "MF") "Hirose")
        (field (name "MP") "DF40C-100DS-0.4V_51_")
      )
      (libsource (lib "eagle-import") (part "DF40C-100DS-0.4V(51)"))
    )
    (comp (ref "MP1")
      (value "9774015151R")
      (footprint "eagle-import:WA-SMSI_9774___151")
      (libsource (lib "eagle-import") (part "BULLET_CONN2.5MM"))
    )
    (comp (ref "MP2")
      (value "9774015151R")
      (footprint "eagle-import:WA-SMSI_9774___151")
      (libsource (lib "eagle-import") (part "BULLET_CONN2.5MM"))
    )
    (comp (ref "MP3")
      (value "9774015151R")
      (footprint "eagle-import:WA-SMSI_9774___151")
      (libsource (lib "eagle-import") (part "BULLET_CONN2.5MM"))
    )
    (comp (ref "MP4")
      (value "9774015151R")
      (footprint "eagle-import:WA-SMSI_9774___151")
      (libsource (lib "eagle-import") (part "BULLET_CONN2.5MM"))
    )
    (comp (ref "Q1")
      (value "BSS138")
      (footprint "eagle-import:SOT23")
      (libsource (lib "eagle-import") (part "BSS138"))
    )
    (comp (ref "Q2")
      (value "FDN360P")
      (footprint "eagle-import:SOT23")
      (libsource (lib "eagle-import") (part "MOSFET_P_ENH"))
    )
    (comp (ref "Q3")
      (value "FDN360P")
      (footprint "eagle-import:SOT23")
      (libsource (lib "eagle-import") (part "MOSFET_P_ENH"))
    )
    (comp (ref "R1")
      (value "0R")
      (footprint "eagle-import:0201")
      (libsource (lib "eagle-import") (part "R0201"))
    )
    (comp (ref "R2")
      (value "DNP")
      (footprint "eagle-import:0201")
      (libsource (lib "eagle-import") (part "R0201"))
    )
    (comp (ref "R3")
      (value "0R")
      (footprint "eagle-import:0201")
      (libsource (lib "eagle-import") (part "R0201"))
    )
    (comp (ref "R5")
      (value "10K 1%")
      (footprint "eagle-import:0201")
      (libsource (lib "eagle-import") (part "R0201"))
    )
    (comp (ref "C99")
      (value "4.7uF")
      (footprint "eagle-import:0603")
      (libsource (lib "eagle-import") (part "C0603"))
    )
    (comp (ref "D5")
      (value "B72590D50A060")
      (footprint "eagle-import:D0402")
      (libsource (lib "eagle-import") (part "ESD-DIODE"))
    )
    (comp (ref "D16")
      (value "PS04LTVA1")
      (footprint "eagle-import:D0402")
      (libsource (lib "eagle-import") (part "ESD-DIODE"))
    )
    (comp (ref "D17")
      (value "PS04LTVA1")
      (footprint "eagle-import:D0402")
      (libsource (lib "eagle-import") (part "ESD-DIODE"))
    )
    (comp (ref "D18")
      (value "B72590D50A060")
      (footprint "eagle-import:D0402")
      (libsource (lib "eagle-import") (part "ESD-DIODE"))
    )
    (comp (ref "J5")
      (value "USB_MICRO_B")
      (footprint "eagle-import:USB_MICRO_B")
      (libsource (lib "eagle-import") (part "USB_MICRO_B"))
    )
    (comp (ref "L5")
      (value "DLP11SN900HL2")
      (footprint "eagle-import:0504-DLP11S")
      (libsource (lib "eagle-import") (part "COM_MODE_CHOKE"))
    )
    (comp (ref "R37")
      (value "0R")
      (footprint "eagle-import:0201")
      (libsource (lib "eagle-import") (part "R0201"))
    )
    (comp (ref "C103")
      (value "0.1uF")
      (footprint "eagle-import:0201")
      (libsource (lib "eagle-import") (part "qualified_1@eagle_src_repo_a6c39d613d14f2251c563284af21e76ddd4db3e9_C0201"))
    )
    (comp (ref "R27")
      (value "10K 1%")
      (footprint "eagle-import:0201")
      (libsource (lib "eagle-import") (part "qualified_1@eagle_src_repo_a6c39d613d14f2251c563284af21e76ddd4db3e9_R0201"))
    )
    (comp (ref "R28")
      (value "10K 1%")
      (footprint "eagle-import:0201")
      (libsource (lib "eagle-import") (part "qualified_1@eagle_src_repo_a6c39d613d14f2251c563284af21e76ddd4db3e9_R0201"))
    )
    (comp (ref "U26")
      (value "TS3USB30")
      (footprint "eagle-import:UQFN-10")
      (libsource (lib "eagle-import") (part "TS3USB30WQ"))
    )
    (comp (ref "C80")
      (value "0.1uF")
      (footprint "eagle-import:0201")
      (libsource (lib "eagle-import") (part "C0201"))
    )
    (comp (ref "C81")
      (value "4.7uF")
      (footprint "eagle-import:0603")
      (libsource (lib "eagle-import") (part "C0603"))
    )
    (comp (ref "C82")
      (value "0.1uF")
      (footprint "eagle-import:0201")
      (libsource (lib "eagle-import") (part "C0201"))
    )
    (comp (ref "C83")
      (value "0.1uF")
      (footprint "eagle-import:0201")
      (libsource (lib "eagle-import") (part "C0201"))
    )
    (comp (ref "C84")
      (value "0.1uF")
      (footprint "eagle-import:0201")
      (libsource (lib "eagle-import") (part "C0201"))
    )
    (comp (ref "FB10")
      (value "120R 1A")
      (footprint "eagle-import:0402")
      (libsource (lib "eagle-import") (part "FB0402"))
    )
    (comp (ref "IC3")
      (value "SN74LVC1G126DCKR")
      (footprint "eagle-import:SC70-5")
      (fields
        (field (name "DM") "0")
        (field (name "DR") "90.000")
        (field (name "DX") "58.050")
        (field (name "DY") "17.100")
        (field (name "SHEETNO") "4")
      )
      (libsource (lib "eagle-import") (part "SN74LVC1G126DCKR"))
    )
    (comp (ref "IC5")
      (value "FT232RQ")
      (footprint "eagle-import:QFN32")
      (libsource (lib "eagle-import") (part "FT232RQ"))
    )
    (comp (ref "D15")
      (value "GREEN")
      (footprint "eagle-import:D0603")
      (libsource (lib "eagle-import") (part "LED0603"))
    )
    (comp (ref "Q4")
      (value "BSS138")
      (footprint "eagle-import:SOT23")
      (libsource (lib "eagle-import") (part "BSS138"))
    )
    (comp (ref "R35")
      (value "300R")
      (footprint "eagle-import:0402")
      (libsource (lib "eagle-import") (part "R0402"))
    )
    (comp (ref "R36")
      (value "100K 1%")
      (footprint "eagle-import:0201")
      (libsource (lib "eagle-import") (part "R0201"))
    )
    (comp (ref "R46")
      (value "1K")
      (footprint "eagle-import:0201")
      (libsource (lib "eagle-import") (part "R0201"))
    )
    (comp (ref "FD1")
      (value "DNP")
      (footprint "eagle-import:FIDUCIAL")
      (libsource (lib "eagle-import") (part "FIDUCIAL"))
    )
    (comp (ref "FD2")
      (value "DNP")
      (footprint "eagle-import:FIDUCIAL")
      (libsource (lib "eagle-import") (part "FIDUCIAL"))
    )
    (comp (ref "FD3")
      (value "DNP")
      (footprint "eagle-import:FIDUCIAL")
      (libsource (lib "eagle-import") (part "FIDUCIAL"))
    )
    (comp (ref "FD4")
      (value "DNP")
      (footprint "eagle-import:FIDUCIAL")
      (libsource (lib "eagle-import") (part "FIDUCIAL"))
    )
    (comp (ref "FD5")
      (value "DNP")
      (footprint "eagle-import:FIDUCIAL")
      (libsource (lib "eagle-import") (part "FIDUCIAL"))
    )
    (comp (ref "FD6")
      (value "DNP")
      (footprint "eagle-import:FIDUCIAL")
      (libsource (lib "eagle-import") (part "FIDUCIAL"))
    )
    (comp (ref "FD7")
      (value "DNP")
      (footprint "eagle-import:FIDUCIAL")
      (libsource (lib "eagle-import") (part "FIDUCIAL"))
    )
    (comp (ref "FD8")
      (value "DNP")
      (footprint "eagle-import:FIDUCIAL")
      (libsource (lib "eagle-import") (part "FIDUCIAL"))
    )
    (comp (ref "U$3")
      (value "DNP")
      (footprint "eagle-import:GEPPETTO_LABEL")
      (fields
        (field (name "BOARD") "PCB900000001400v2")
        (field (name "TITLE") "Raspberry Pi CM4 Dev Board")
        (field (name "YEAR") "2020")
      )
      (libsource (lib "eagle-import") (part "GEPPETTO_LABEL{dblquote}"))
    )
    (comp (ref "U$4")
      (value "DNP")
      (footprint "eagle-import:GEPPETTO_LOGO_SILK10")
      (libsource (lib "eagle-import") (part "GEPPETTO_LOGO10X10"))
    )
    (comp (ref "U$6")
      (value "DNP")
      (footprint "eagle-import:TIP_POSITIVE_LABEL")
      (fields (field (name "VOLTAGE") "5V") (field (name "VOLTAGE_1") "5.5-36V"))
      (libsource (lib "eagle-import") (part "TIP_POSITIVE_LABEL"))
    )
    (comp (ref "J9")
      (value "FPC-15VERT")
      (footprint "eagle-import:1-1734248-5")
      (libsource (lib "eagle-import") (part "FPC-15VERT"))
    )
    (comp (ref "C7")
      (value "0.01uF")
      (footprint "eagle-import:0201")
      (libsource (lib "eagle-import") (part "C0201"))
    )
    (comp (ref "C8")
      (value "0.1uF")
      (footprint "eagle-import:0201")
      (libsource (lib "eagle-import") (part "C0201"))
    )
    (comp (ref "C17")
      (value "0.1uF")
      (footprint "eagle-import:0201")
      (libsource (lib "eagle-import") (part "C0201"))
    )
    (comp (ref "C18")
      (value "10uF")
      (footprint "eagle-import:0603")
      (libsource (lib "eagle-import") (part "C0603"))
    )
    (comp (ref "C93")
      (value "0.1uF")
      (footprint "eagle-import:0201")
      (libsource (lib "eagle-import") (part "C0201"))
    )
    (comp (ref "C94")
      (value "10uF")
      (footprint "eagle-import:0603")
      (libsource (lib "eagle-import") (part "C0603"))
    )
    (comp (ref "C95")
      (value "0.1uF")
      (footprint "eagle-import:0201")
      (libsource (lib "eagle-import") (part "C0201"))
    )
    (comp (ref "C102")
      (value "0.1uF")
      (footprint "eagle-import:0201")
      (libsource (lib "eagle-import") (part "C0201"))
    )
    (comp (ref "C104")
      (value "10uF")
      (footprint "eagle-import:0603")
      (libsource (lib "eagle-import") (part "C0603"))
    )
    (comp (ref "C111")
      (value "0.1uF")
      (footprint "eagle-import:0201")
      (libsource (lib "eagle-import") (part "C0201"))
    )
    (comp (ref "MP5")
      (value "9774025360R")
      (footprint "eagle-import:WA-SMSI_9774___360")
      (libsource (lib "eagle-import") (part "BULLET_CONN3MM"))
    )
    (comp (ref "Q5")
      (value "32.768kHz")
      (footprint "eagle-import:VLGA-4")
      (libsource (lib "eagle-import") (part "ASFVLGA"))
    )
    (comp (ref "U6")
      (value "M2_KEY_M")
      (footprint "eagle-import:2199230_KEY_M")
      (libsource (lib "eagle-import") (part "M2_KEY_M"))
    )
    (comp (ref "C96")
      (value "0.1uF")
      (footprint "eagle-import:0201")
      (libsource (lib "eagle-import") (part "C0201"))
    )
    (comp (ref "C100")
      (value "0.1uF")
      (footprint "eagle-import:0201")
      (libsource (lib "eagle-import") (part "C0201"))
    )
    (comp (ref "J4")
      (value "1000BASET")
      (footprint "eagle-import:7499111447")
      (libsource (lib "eagle-import") (part "1000BASET"))
    )
    (comp (ref "R25")
      (value "330R")
      (footprint "eagle-import:0201")
      (libsource (lib "eagle-import") (part "R0201"))
    )
    (comp (ref "R26")
      (value "330R")
      (footprint "eagle-import:0201")
      (libsource (lib "eagle-import") (part "R0201"))
    )
    (comp (ref "U1")
      (value "TPD4E02B0410-USON")
      (footprint "eagle-import:UFDFN-10")
      (libsource (lib "eagle-import") (part "TPD4E02B0410-USON"))
    )
    (comp (ref "U5")
      (value "TPD4E02B0410-USON")
      (footprint "eagle-import:UFDFN-10")
      (libsource (lib "eagle-import") (part "TPD4E02B0410-USON"))
    )
  )
  (nets
    (net (code "1") (name "1.8V_OUT$19") (class "Default")
      (node (ref "J7") (pin "88") (pinfunction "88_88") (pintype "passive"))
      (node (ref "J7") (pin "90") (pinfunction "90_90") (pintype "passive"))
      (node (ref "R2") (pin "1") (pinfunction "1_1") (pintype "passive"))
    )
    (net (code "2") (name "1.USB_DEVICE_D_N") (class "Default")
      (node (ref "IC5") (pin "15") (pinfunction "USBDM_15") (pintype "bidirectional"))
      (node (ref "L8") (pin "2") (pinfunction "2_2") (pintype "passive"))
    )
    (net (code "3") (name "1.USB_DEVICE_D_P") (class "Default")
      (node (ref "IC5") (pin "14") (pinfunction "USBDP_14") (pintype "bidirectional"))
      (node (ref "L8") (pin "3") (pinfunction "3_3") (pintype "passive"))
    )
    (net (code "4") (name "1.USB_DEVICE_VBUS") (class "Default")
      (node (ref "FB10") (pin "1") (pinfunction "1_1") (pintype "passive"))
      (node (ref "R13") (pin "2") (pinfunction "2_2") (pintype "passive"))
      (node (ref "R20") (pin "1") (pinfunction "1_1") (pintype "passive"))
    )
    (net (code "5") (name "2.5.0V_VCC_5.0") (class "Default")
      (node (ref "C108") (pin "1") (pinfunction "1_1") (pintype "passive"))
      (node (ref "C4") (pin "1") (pinfunction "1_1") (pintype "passive"))
      (node (ref "C5") (pin "1") (pinfunction "1_1") (pintype "passive"))
      (node (ref "C78") (pin "1") (pinfunction "1_1") (pintype "passive"))
      (node (ref "C79") (pin "+") (pinfunction "1_+") (pintype "passive"))
      (node (ref "C85") (pin "1") (pinfunction "1_1") (pintype "passive"))
      (node (ref "C87") (pin "1") (pinfunction "1_1") (pintype "passive"))
      (node (ref "C90") (pin "1") (pinfunction "1_1") (pintype "passive"))
      (node (ref "IC1") (pin "2") (pinfunction "IN_2") (pintype "bidirectional"))
      (node (ref "IC1") (pin "3") (pinfunction "IN_3") (pintype "bidirectional"))
      (node (ref "IC4") (pin "2") (pinfunction "VIN_2") (pintype "power_in"))
      (node (ref "IC4") (pin "3") (pinfunction "VIN_3") (pintype "power_in"))
      (node (ref "IC4") (pin "4") (pinfunction "EN_4") (pintype "input"))
      (node (ref "IC4") (pin "8") (pinfunction "VIN_8") (pintype "power_in"))
      (node (ref "J7") (pin "77") (pinfunction "77_77") (pintype "passive"))
      (node (ref "J7") (pin "79") (pinfunction "79_79") (pintype "passive"))
      (node (ref "J7") (pin "81") (pinfunction "81_81") (pintype "passive"))
      (node (ref "J7") (pin "83") (pinfunction "83_83") (pintype "passive"))
      (node (ref "J7") (pin "85") (pinfunction "85_85") (pintype "passive"))
      (node (ref "J7") (pin "87") (pinfunction "87_87") (pintype "passive"))
      (node (ref "L6") (pin "2") (pinfunction "2_2") (pintype "passive"))
      (node (ref "R12") (pin "1") (pinfunction "1_1") (pintype "passive"))
      (node (ref "U$29") (pin "14") (pinfunction "VCCB_14") (pintype "power_in"))
      (node (ref "U4") (pin "2") (pinfunction "2_2") (pintype "passive"))
      (node (ref "U4") (pin "4") (pinfunction "4_4") (pintype "passive"))
      (node (ref "U8") (pin "5") (pinfunction "5V_SUPPLY_5") (pintype "power_in"))
    )
    (net (code "6") (name "3.3.3V_VCC_3.3") (class "Default")
      (node (ref "C102") (pin "1") (pinfunction "1_1") (pintype "passive"))
      (node (ref "C103") (pin "1") (pinfunction "1_1") (pintype "passive"))
      (node (ref "C104") (pin "1") (pinfunction "1_1") (pintype "passive"))
      (node (ref "C111") (pin "1") (pinfunction "1_1") (pintype "passive"))
      (node (ref "C17") (pin "1") (pinfunction "1_1") (pintype "passive"))
      (node (ref "C18") (pin "1") (pinfunction "1_1") (pintype "passive"))
      (node (ref "C7") (pin "1") (pinfunction "1_1") (pintype "passive"))
      (node (ref "C8") (pin "1") (pinfunction "1_1") (pintype "passive"))
      (node (ref "C91") (pin "1") (pinfunction "1_1") (pintype "passive"))
      (node (ref "C92") (pin "1") (pinfunction "1_1") (pintype "passive"))
      (node (ref "C93") (pin "1") (pinfunction "1_1") (pintype "passive"))
      (node (ref "C94") (pin "1") (pinfunction "1_1") (pintype "passive"))
      (node (ref "C95") (pin "1") (pinfunction "1_1") (pintype "passive"))
      (node (ref "IC1") (pin "4") (pinfunction "EN_4") (pintype "bidirectional"))
      (node (ref "J1") (pin "1_14") (pinfunction "14_1_14") (pintype "passive"))
      (node (ref "J1") (pin "1_15") (pinfunction "15_1_15") (pintype "passive"))
      (node (ref "J10") (pin "1_15") (pinfunction "15_1_15") (pintype "passive"))
      (node (ref "J9") (pin "1_15") (pinfunction "15_1_15") (pintype "passive"))
      (node (ref "L7") (pin "2") (pinfunction "2_2") (pintype "passive"))
      (node (ref "Q5") (pin "1") (pinfunction "OE_1") (pintype "input"))
      (node (ref "Q5") (pin "4") (pinfunction "VCC_4") (pintype "power_in"))
      (node (ref "R19") (pin "2") (pinfunction "2_2") (pintype "passive"))
      (node (ref "R21") (pin "2") (pinfunction "2_2") (pintype "passive"))
      (node (ref "R25") (pin "1") (pinfunction "1_1") (pintype "passive"))
      (node (ref "R26") (pin "1") (pinfunction "1_1") (pintype "passive"))
      (node (ref "R33") (pin "2") (pinfunction "2_2") (pintype "passive"))
      (node (ref "R35") (pin "2") (pinfunction "2_2") (pintype "passive"))
      (node (ref "U26") (pin "9") (pinfunction "VCC_9") (pintype "power_in"))
      (node (ref "U4") (pin "1") (pinfunction "1_1") (pintype "passive"))
      (node (ref "U4") (pin "17") (pinfunction "17_17") (pintype "passive"))
      (node (ref "U6") (pin "12") (pinfunction "VCC_3.3_12") (pintype "bidirectional"))
      (node (ref "U6") (pin "14") (pinfunction "VCC_3.3_14") (pintype "bidirectional"))
      (node (ref "U6") (pin "16") (pinfunction "VCC_3.3_16") (pintype "bidirectional"))
      (node (ref "U6") (pin "18") (pinfunction "VCC_3.3_18") (pintype "bidirectional"))
      (node (ref "U6") (pin "2") (pinfunction "VCC_3.3_2") (pintype "bidirectional"))
      (node (ref "U6") (pin "4") (pinfunction "VCC_3.3_4") (pintype "bidirectional"))
      (node (ref "U6") (pin "70") (pinfunction "VCC_3.3_70") (pintype "bidirectional"))
      (node (ref "U6") (pin "72") (pinfunction "VCC_3.3_72") (pintype "bidirectional"))
      (node (ref "U6") (pin "74") (pinfunction "VCC_3.3_74") (pintype "bidirectional"))
    )
    (net (code "7") (name "3.3V_OUT$19") (class "Default")
      (node (ref "J7") (pin "84") (pinfunction "84_84") (pintype "passive"))
      (node (ref "J7") (pin "86") (pinfunction "86_86") (pintype "passive"))
      (node (ref "Q2") (pin "3") (pinfunction "D_3") (pintype "passive"))
      (node (ref "R1") (pin "1") (pinfunction "1_1") (pintype "passive"))
    )
    (net (code "8") (name "5.5.5-36V_VCC_BATT") (class "Default")
      (node (ref "C88") (pin "1") (pinfunction "1_1") (pintype "passive"))
      (node (ref "C89") (pin "1") (pinfunction "1_1") (pintype "passive"))
      (node (ref "D7") (pin "C") (pinfunction "2_C") (pintype "passive"))
      (node (ref "J3") (pin "1") (pinfunction "V_POWER_1") (pintype "power_in"))
      (node (ref "R18") (pin "1") (pinfunction "1_1") (pintype "passive"))
      (node (ref "TP1") (pin "1") (pinfunction "TP_1") (pintype "bidirectional"))
    )
    (net (code "9") (name "18.UART1_RXD") (class "Default")
      (node (ref "RP1") (pin "1") (pinfunction "1_1") (pintype "passive"))
      (node (ref "U2") (pin "7") (pinfunction "NC2_7") (pintype "bidirectional"))
      (node (ref "U4") (pin "10") (pinfunction "10_10") (pintype "passive"))
    )
    (net (code "10") (name "18.UART1_TXD") (class "Default")
      (node (ref "RP1") (pin "2") (pinfunction "2_2") (pintype "passive"))
      (node (ref "U2") (pin "5") (pinfunction "NC1_5") (pintype "bidirectional"))
      (node (ref "U4") (pin "8") (pinfunction "8_8") (pintype "passive"))
    )
    (net (code "11") (name "18.UART2_RXD") (class "Default")
      (node (ref "IC3") (pin "4") (pinfunction "O_4") (pintype "output"))
      (node (ref "RP2") (pin "4") (pinfunction "4_4") (pintype "passive"))
      (node (ref "U2") (pin "10") (pinfunction "NO2_10") (pintype "bidirectional"))
    )
    (net (code "12") (name "18.UART2_TXD") (class "Default")
      (node (ref "IC5") (pin "2") (pinfunction "RXD_2") (pintype "input"))
      (node (ref "RP2") (pin "3") (pinfunction "3_3") (pintype "passive"))
      (node (ref "U2") (pin "2") (pinfunction "NO1_2") (pintype "bidirectional"))
    )
    (net (code "13") (name "19.3.3V_VCC_3.3") (class "Default")
      (node (ref "Q3") (pin "3") (pinfunction "D_3") (pintype "passive"))
      (node (ref "R3") (pin "2") (pinfunction "2_2") (pintype "passive"))
    )
    (net (code "14") (name "19.1000BASET_LINK_100") (class "Default")
      (node (ref "J7") (pin "19") (pinfunction "19_19") (pintype "passive"))
    )
    (net (code "15") (name "19.1000BASET_LINK_1000") (class "Default")
      (node (ref "J4") (pin "13") (pinfunction "LED_YELLOW-_13") (pintype "bidirectional"))
      (node (ref "J7") (pin "17") (pinfunction "17_17") (pintype "passive"))
    )
    (net (code "16") (name "19.1000BASET_LINK_ACT") (class "Default")
      (node (ref "J4") (pin "12") (pinfunction "LED_GREEN-_12") (pintype "bidirectional"))
      (node (ref "J7") (pin "15") (pinfunction "15_15") (pintype "passive"))
    )
    (net (code "17") (name "19.1000BASET_LINK_ACT__") (class "Default")
      (node (ref "J4") (pin "11") (pinfunction "LED_GREEN+_11") (pintype "bidirectional"))
      (node (ref "R25") (pin "2") (pinfunction "2_2") (pintype "passive"))
    )
    (net (code "18") (name "19.1000BASET_TR0_N") (class "Default")
      (node (ref "J4") (pin "2") (pinfunction "TRD0-_2") (pintype "bidirectional"))
      (node (ref "J7") (pin "10") (pinfunction "10_10") (pintype "passive"))
      (node (ref "U1") (pin "2") (pinfunction "P2_2") (pintype "passive"))
      (node (ref "U1") (pin "9") (pinfunction "P2_9") (pintype "passive"))
    )
    (net (code "19") (name "19.1000BASET_TR0_P") (class "Default")
      (node (ref "J4") (pin "1") (pinfunction "TRD0+_1") (pintype "bidirectional"))
      (node (ref "J7") (pin "12") (pinfunction "12_12") (pintype "passive"))
      (node (ref "U1") (pin "1") (pinfunction "P1_1") (pintype "passive"))
      (node (ref "U1") (pin "10") (pinfunction "P1_10") (pintype "passive"))
    )
    (net (code "20") (name "19.1000BASET_TR1_N") (class "Default")
      (node (ref "J4") (pin "3") (pinfunction "TRD1+_3") (pintype "bidirectional"))
      (node (ref "J7") (pin "6") (pinfunction "6_6") (pintype "passive"))
      (node (ref "U1") (pin "4") (pinfunction "P3_4") (pintype "passive"))
      (node (ref "U1") (pin "7") (pinfunction "P3_7") (pintype "passive"))
    )
    (net (code "21") (name "19.1000BASET_TR1_P") (class "Default")
      (node (ref "J4") (pin "4") (pinfunction "TRD1-_4") (pintype "bidirectional"))
      (node (ref "J7") (pin "4") (pinfunction "4_4") (pintype "passive"))
      (node (ref "U1") (pin "5") (pinfunction "P4_5") (pintype "passive"))
      (node (ref "U1") (pin "6") (pinfunction "P4_6") (pintype "passive"))
    )
    (net (code "22") (name "19.1000BASET_TR2_N") (class "Default")
      (node (ref "J4") (pin "8") (pinfunction "TRD2-_8") (pintype "bidirectional"))
      (node (ref "J7") (pin "9") (pinfunction "9_9") (pintype "passive"))
      (node (ref "U5") (pin "2") (pinfunction "P2_2") (pintype "passive"))
      (node (ref "U5") (pin "9") (pinfunction "P2_9") (pintype "passive"))
    )
    (net (code "23") (name "19.1000BASET_TR2_P") (class "Default")
      (node (ref "J4") (pin "7") (pinfunction "TRD2+_7") (pintype "bidirectional"))
      (node (ref "J7") (pin "11") (pinfunction "11_11") (pintype "passive"))
      (node (ref "U5") (pin "1") (pinfunction "P1_1") (pintype "passive"))
      (node (ref "U5") (pin "10") (pinfunction "P1_10") (pintype "passive"))
    )
    (net (code "24") (name "19.1000BASET_TR3_N") (class "Default")
      (node (ref "J4") (pin "9") (pinfunction "TRD3+_9") (pintype "bidirectional"))
      (node (ref "J7") (pin "5") (pinfunction "5_5") (pintype "passive"))
      (node (ref "U5") (pin "4") (pinfunction "P3_4") (pintype "passive"))
      (node (ref "U5") (pin "7") (pinfunction "P3_7") (pintype "passive"))
    )
    (net (code "25") (name "19.1000BASET_TR3_P") (class "Default")
      (node (ref "J4") (pin "10") (pinfunction "TRD3-_10") (pintype "bidirectional"))
      (node (ref "J7") (pin "3") (pinfunction "3_3") (pintype "passive"))
      (node (ref "U5") (pin "5") (pinfunction "P4_5") (pintype "passive"))
      (node (ref "U5") (pin "6") (pinfunction "P4_6") (pintype "passive"))
    )
    (net (code "26") (name "19.CAM0_C_N") (class "Default")
      (node (ref "J10") (pin "1_8") (pinfunction "8_1_8") (pintype "passive"))
      (node (ref "J2") (pin "40") (pinfunction "40_40") (pintype "passive"))
    )
    (net (code "27") (name "19.CAM0_C_P") (class "Default")
      (node (ref "J10") (pin "1_9") (pinfunction "9_1_9") (pintype "passive"))
      (node (ref "J2") (pin "42") (pinfunction "42_42") (pintype "passive"))
    )
    (net (code "28") (name "19.CAM0_D1_N") (class "Default")
      (node (ref "J10") (pin "1_2") (pinfunction "2_1_2") (pintype "passive"))
      (node (ref "J2") (pin "28") (pinfunction "28_28") (pintype "passive"))
    )
    (net (code "29") (name "19.CAM0_D1_P") (class "Default")
      (node (ref "J10") (pin "1_3") (pinfunction "3_1_3") (pintype "passive"))
      (node (ref "J2") (pin "30") (pinfunction "30_30") (pintype "passive"))
    )
    (net (code "30") (name "19.CAM0_D2_N") (class "Default")
      (node (ref "J10") (pin "1_5") (pinfunction "5_1_5") (pintype "passive"))
      (node (ref "J2") (pin "34") (pinfunction "34_34") (pintype "passive"))
    )
    (net (code "31") (name "19.CAM0_D2_P") (class "Default")
      (node (ref "J10") (pin "1_6") (pinfunction "6_1_6") (pintype "passive"))
      (node (ref "J2") (pin "36") (pinfunction "36_36") (pintype "passive"))
    )
    (net (code "32") (name "19.CAM1_C_N") (class "Default")
      (node (ref "J2") (pin "27") (pinfunction "27_27") (pintype "passive"))
      (node (ref "J9") (pin "1_8") (pinfunction "8_1_8") (pintype "passive"))
    )
    (net (code "33") (name "19.CAM1_C_P") (class "Default")
      (node (ref "J2") (pin "29") (pinfunction "29_29") (pintype "passive"))
      (node (ref "J9") (pin "1_9") (pinfunction "9_1_9") (pintype "passive"))
    )
    (net (code "34") (name "19.CAM1_D1_N") (class "Default")
      (node (ref "J2") (pin "15") (pinfunction "15_15") (pintype "passive"))
      (node (ref "J9") (pin "1_2") (pinfunction "2_1_2") (pintype "passive"))
    )
    (net (code "35") (name "19.CAM1_D1_P") (class "Default")
      (node (ref "J2") (pin "17") (pinfunction "17_17") (pintype "passive"))
      (node (ref "J9") (pin "1_3") (pinfunction "3_1_3") (pintype "passive"))
    )
    (net (code "36") (name "19.CAM1_D2_N") (class "Default")
      (node (ref "J2") (pin "21") (pinfunction "21_21") (pintype "passive"))
      (node (ref "J9") (pin "1_5") (pinfunction "5_1_5") (pintype "passive"))
    )
    (net (code "37") (name "19.CAM1_D2_P") (class "Default")
      (node (ref "J2") (pin "23") (pinfunction "23_23") (pintype "passive"))
      (node (ref "J9") (pin "1_6") (pinfunction "6_1_6") (pintype "passive"))
    )
    (net (code "38") (name "19.CAM1_D3_N") (class "Default")
      (node (ref "J2") (pin "33") (pinfunction "33_33") (pintype "passive"))
    )
    (net (code "39") (name "19.CAM1_D3_P") (class "Default")
      (node (ref "J2") (pin "35") (pinfunction "35_35") (pintype "passive"))
    )
    (net (code "40") (name "19.CAM1_D4_N") (class "Default")
      (node (ref "J2") (pin "39") (pinfunction "39_39") (pintype "passive"))
    )
    (net (code "41") (name "19.CAM1_D4_P") (class "Default")
      (node (ref "J2") (pin "41") (pinfunction "41_41") (pintype "passive"))
    )
    (net (code "42") (name "19.DSI1_C_N") (class "Default")
      (node (ref "J1") (pin "1_5") (pinfunction "5_1_5") (pintype "passive"))
      (node (ref "J2") (pin "87") (pinfunction "87_87") (pintype "passive"))
    )
    (net (code "43") (name "19.DSI1_C_P") (class "Default")
      (node (ref "J1") (pin "1_6") (pinfunction "6_1_6") (pintype "passive"))
      (node (ref "J2") (pin "89") (pinfunction "89_89") (pintype "passive"))
    )
    (net (code "44") (name "19.DSI1_D1_N") (class "Default")
      (node (ref "J1") (pin "1_8") (pinfunction "8_1_8") (pintype "passive"))
      (node (ref "J2") (pin "75") (pinfunction "75_75") (pintype "passive"))
    )
    (net (code "45") (name "19.DSI1_D1_P") (class "Default")
      (node (ref "J1") (pin "1_9") (pinfunction "9_1_9") (pintype "passive"))
      (node (ref "J2") (pin "77") (pinfunction "77_77") (pintype "passive"))
    )
    (net (code "46") (name "19.DSI1_D2_N") (class "Default")
      (node (ref "J1") (pin "1_2") (pinfunction "2_1_2") (pintype "passive"))
      (node (ref "J2") (pin "81") (pinfunction "81_81") (pintype "passive"))
    )
    (net (code "47") (name "19.DSI1_D2_P") (class "Default")
      (node (ref "J1") (pin "1_3") (pinfunction "3_1_3") (pintype "passive"))
      (node (ref "J2") (pin "83") (pinfunction "83_83") (pintype "passive"))
    )
    (net (code "48") (name "19.DSI1_D3_N") (class "Default")
      (node (ref "J2") (pin "93") (pinfunction "93_93") (pintype "passive"))
    )
    (net (code "49") (name "19.DSI1_D3_P") (class "Default")
      (node (ref "J2") (pin "95") (pinfunction "95_95") (pintype "passive"))
    )
    (net (code "50") (name "19.DSI1_D4_N") (class "Default")
      (node (ref "J2") (pin "94") (pinfunction "94_94") (pintype "passive"))
    )
    (net (code "51") (name "19.DSI1_D4_P") (class "Default")
      (node (ref "J2") (pin "96") (pinfunction "96_96") (pintype "passive"))
    )
    (net (code "52") (name "19.GPIO2_GPIO") (class "Default")
      (node (ref "J7") (pin "58") (pinfunction "58_58") (pintype "passive"))
      (node (ref "U4") (pin "3") (pinfunction "3_3") (pintype "passive"))
    )
    (net (code "53") (name "19.GPIO3_GPIO") (class "Default")
      (node (ref "J7") (pin "56") (pinfunction "56_56") (pintype "passive"))
      (node (ref "U4") (pin "5") (pinfunction "5_5") (pintype "passive"))
    )
    (net (code "54") (name "19.GPIO4_GPIO") (class "Default")
      (node (ref "J7") (pin "54") (pinfunction "54_54") (pintype "passive"))
      (node (ref "U4") (pin "7") (pinfunction "7_7") (pintype "passive"))
    )
    (net (code "55") (name "19.GPIO5_GPIO") (class "Default")
      (node (ref "J7") (pin "34") (pinfunction "34_34") (pintype "passive"))
      (node (ref "U4") (pin "29") (pinfunction "29_29") (pintype "passive"))
    )
    (net (code "56") (name "19.GPIO6_GPIO") (class "Default")
      (node (ref "J7") (pin "30") (pinfunction "30_30") (pintype "passive"))
      (node (ref "U4") (pin "31") (pinfunction "31_31") (pintype "passive"))
    )
    (net (code "57") (name "19.GPIO7_GPIO") (class "Default")
      (node (ref "J7") (pin "37") (pinfunction "37_37") (pintype "passive"))
      (node (ref "U4") (pin "26") (pinfunction "26_26") (pintype "passive"))
    )
    (net (code "58") (name "19.GPIO8_GPIO") (class "Default")
      (node (ref "J7") (pin "39") (pinfunction "39_39") (pintype "passive"))
      (node (ref "U4") (pin "24") (pinfunction "24_24") (pintype "passive"))
    )
    (net (code "59") (name "19.GPIO9_GPIO") (class "Default")
      (node (ref "J7") (pin "40") (pinfunction "40_40") (pintype "passive"))
      (node (ref "U4") (pin "21") (pinfunction "21_21") (pintype "passive"))
    )
    (net (code "60") (name "19.GPIO10_GPIO") (class "Default")
      (node (ref "J7") (pin "44") (pinfunction "44_44") (pintype "passive"))
      (node (ref "U4") (pin "19") (pinfunction "19_19") (pintype "passive"))
    )
    (net (code "61") (name "19.GPIO11_GPIO") (class "Default")
      (node (ref "J7") (pin "38") (pinfunction "38_38") (pintype "passive"))
      (node (ref "U4") (pin "23") (pinfunction "23_23") (pintype "passive"))
    )
    (net (code "62") (name "19.GPIO12_GPIO") (class "Default")
      (node (ref "J7") (pin "31") (pinfunction "31_31") (pintype "passive"))
      (node (ref "U4") (pin "32") (pinfunction "32_32") (pintype "passive"))
    )
    (net (code "63") (name "19.GPIO13_GPIO") (class "Default")
      (node (ref "J7") (pin "28") (pinfunction "28_28") (pintype "passive"))
      (node (ref "U4") (pin "33") (pinfunction "33_33") (pintype "passive"))
    )
    (net (code "64") (name "19.GPIO16_GPIO") (class "Default")
      (node (ref "J7") (pin "29") (pinfunction "29_29") (pintype "passive"))
      (node (ref "U4") (pin "36") (pinfunction "36_36") (pintype "passive"))
    )
    (net (code "65") (name "19.GPIO17_GPIO") (class "Default")
      (node (ref "J7") (pin "50") (pinfunction "50_50") (pintype "passive"))
      (node (ref "U4") (pin "11") (pinfunction "11_11") (pintype "passive"))
    )
    (net (code "66") (name "19.GPIO18_GPIO") (class "Default")
      (node (ref "J7") (pin "49") (pinfunction "49_49") (pintype "passive"))
      (node (ref "U4") (pin "12") (pinfunction "12_12") (pintype "passive"))
    )
    (net (code "67") (name "19.GPIO19_GPIO") (class "Default")
      (node (ref "J7") (pin "26") (pinfunction "26_26") (pintype "passive"))
      (node (ref "U4") (pin "35") (pinfunction "35_35") (pintype "passive"))
    )
    (net (code "68") (name "19.GPIO20_GPIO") (class "Default")
      (node (ref "J7") (pin "27") (pinfunction "27_27") (pintype "passive"))
      (node (ref "U4") (pin "38") (pinfunction "38_38") (pintype "passive"))
    )
    (net (code "69") (name "19.GPIO21_GPIO") (class "Default")
      (node (ref "J7") (pin "25") (pinfunction "25_25") (pintype "passive"))
      (node (ref "U4") (pin "40") (pinfunction "40_40") (pintype "passive"))
    )
    (net (code "70") (name "19.GPIO22_GPIO") (class "Default")
      (node (ref "J7") (pin "46") (pinfunction "46_46") (pintype "passive"))
      (node (ref "U4") (pin "15") (pinfunction "15_15") (pintype "passive"))
    )
    (net (code "71") (name "19.GPIO23_GPIO") (class "Default")
      (node (ref "J7") (pin "47") (pinfunction "47_47") (pintype "passive"))
      (node (ref "R32") (pin "1") (pinfunction "1_1") (pintype "passive"))
      (node (ref "R34") (pin "2") (pinfunction "2_2") (pintype "passive"))
      (node (ref "U4") (pin "16") (pinfunction "16_16") (pintype "passive"))
    )
    (net (code "72") (name "19.GPIO24_GPIO") (class "Default")
      (node (ref "C98") (pin "1") (pinfunction "1_1") (pintype "passive"))
      (node (ref "J7") (pin "45") (pinfunction "45_45") (pintype "passive"))
      (node (ref "R31") (pin "2") (pinfunction "2_2") (pintype "passive"))
      (node (ref "U4") (pin "18") (pinfunction "18_18") (pintype "passive"))
    )
    (net (code "73") (name "19.GPIO25_GPIO") (class "Default")
      (node (ref "J7") (pin "41") (pinfunction "41_41") (pintype "passive"))
      (node (ref "U4") (pin "22") (pinfunction "22_22") (pintype "passive"))
    )
    (net (code "74") (name "19.GPIO26_GPIO") (class "Default")
      (node (ref "J7") (pin "24") (pinfunction "24_24") (pintype "passive"))
      (node (ref "U4") (pin "37") (pinfunction "37_37") (pintype "passive"))
    )
    (net (code "75") (name "19.GPIO27_GPIO") (class "Default")
      (node (ref "J7") (pin "48") (pinfunction "48_48") (pintype "passive"))
      (node (ref "U4") (pin "13") (pinfunction "13_13") (pintype "passive"))
    )
    (net (code "76") (name "19.GPIO_CAMERA_GPIO") (class "Default")
      (node (ref "J10") (pin "1_11") (pinfunction "11_1_11") (pintype "passive"))
      (node (ref "J7") (pin "97") (pinfunction "97_97") (pintype "passive"))
      (node (ref "J9") (pin "1_11") (pinfunction "11_1_11") (pintype "passive"))
    )
    (net (code "77") (name "19.HDMI0_CEC") (class "Default")
      (node (ref "J2") (pin "51") (pinfunction "51_51") (pintype "passive"))
      (node (ref "RP3") (pin "4") (pinfunction "4_4") (pintype "passive"))
      (node (ref "U$29") (pin "2") (pinfunction "A1_2") (pintype "bidirectional"))
    )
    (net (code "78") (name "19.HDMI0_CLOCK_N") (class "Default")
      (node (ref "J2") (pin "90") (pinfunction "90_90") (pintype "passive"))
      (node (ref "L4") (pin "2") (pinfunction "2_2") (pintype "passive"))
      (node (ref "U8") (pin "9") (pinfunction "D3-_9") (pintype "bidirectional"))
    )
    (net (code "79") (name "19.HDMI0_CLOCK_P") (class "Default")
      (node (ref "J2") (pin "88") (pinfunction "88_88") (pintype "passive"))
      (node (ref "L4") (pin "3") (pinfunction "3_3") (pintype "passive"))
      (node (ref "U8") (pin "10") (pinfunction "D3+_10") (pintype "bidirectional"))
    )
    (net (code "80") (name "19.HDMI0_D0_N") (class "Default")
      (node (ref "J2") (pin "84") (pinfunction "84_84") (pintype "passive"))
      (node (ref "L3") (pin "2") (pinfunction "2_2") (pintype "passive"))
      (node (ref "U8") (pin "11") (pinfunction "D2-_11") (pintype "bidirectional"))
    )
    (net (code "81") (name "19.HDMI0_D0_P") (class "Default")
      (node (ref "J2") (pin "82") (pinfunction "82_82") (pintype "passive"))
      (node (ref "L3") (pin "3") (pinfunction "3_3") (pintype "passive"))
      (node (ref "U8") (pin "12") (pinfunction "D2+_12") (pintype "bidirectional"))
    )
    (net (code "82") (name "19.HDMI0_D1_N") (class "Default")
      (node (ref "J2") (pin "78") (pinfunction "78_78") (pintype "passive"))
      (node (ref "L2") (pin "2") (pinfunction "2_2") (pintype "passive"))
      (node (ref "U8") (pin "13") (pinfunction "D1-_13") (pintype "bidirectional"))
    )
    (net (code "83") (name "19.HDMI0_D1_P") (class "Default")
      (node (ref "J2") (pin "76") (pinfunction "76_76") (pintype "passive"))
      (node (ref "L2") (pin "3") (pinfunction "3_3") (pintype "passive"))
      (node (ref "U8") (pin "14") (pinfunction "D1+_14") (pintype "bidirectional"))
    )
    (net (code "84") (name "19.HDMI0_D2_N") (class "Default")
      (node (ref "J2") (pin "72") (pinfunction "72_72") (pintype "passive"))
      (node (ref "L9") (pin "2") (pinfunction "2_2") (pintype "passive"))
      (node (ref "U8") (pin "15") (pinfunction "D0-_15") (pintype "bidirectional"))
    )
    (net (code "85") (name "19.HDMI0_D2_P") (class "Default")
      (node (ref "J2") (pin "70") (pinfunction "70_70") (pintype "passive"))
      (node (ref "L9") (pin "3") (pinfunction "3_3") (pintype "passive"))
      (node (ref "U8") (pin "16") (pinfunction "D0+_16") (pintype "bidirectional"))
    )
    (net (code "86") (name "19.HDMI0_DDC_SCL") (class "Default")
      (node (ref "J2") (pin "100") (pinfunction "100_100") (pintype "passive"))
      (node (ref "RP3") (pin "3") (pinfunction "3_3") (pintype "passive"))
      (node (ref "U$29") (pin "3") (pinfunction "A2_3") (pintype "bidirectional"))
    )
    (net (code "87") (name "19.HDMI0_DDC_SDA") (class "Default")
      (node (ref "J2") (pin "99") (pinfunction "99_99") (pintype "passive"))
      (node (ref "RP3") (pin "2") (pinfunction "2_2") (pintype "passive"))
      (node (ref "U$29") (pin "4") (pinfunction "A3_4") (pintype "bidirectional"))
    )
    (net (code "88") (name "19.HDMI0_HPD") (class "Default")
      (node (ref "J2") (pin "53") (pinfunction "53_53") (pintype "passive"))
      (node (ref "RP3") (pin "1") (pinfunction "1_1") (pintype "passive"))
      (node (ref "U$29") (pin "5") (pinfunction "A4_5") (pintype "bidirectional"))
    )
    (net (code "89") (name "19.I2C_ID_SCL") (class "Default")
      (node (ref "IC6") (pin "6") (pinfunction "SCL_6") (pintype "bidirectional"))
      (node (ref "J10") (pin "1_13") (pinfunction "13_1_13") (pintype "passive"))
      (node (ref "J7") (pin "35") (pinfunction "35_35") (pintype "passive"))
      (node (ref "R10") (pin "1") (pinfunction "1_1") (pintype "passive"))
    )
    (net (code "90") (name "19.I2C_ID_SDA") (class "Default")
      (node (ref "IC6") (pin "5") (pinfunction "SDA_5") (pintype "bidirectional"))
      (node (ref "J10") (pin "1_14") (pinfunction "14_1_14") (pintype "passive"))
      (node (ref "J7") (pin "36") (pinfunction "36_36") (pintype "passive"))
      (node (ref "R9") (pin "1") (pinfunction "1_1") (pintype "passive"))
    )
    (net (code "91") (name "19.I2C_SCL") (class "Default")
      (node (ref "J1") (pin "1_11") (pinfunction "11_1_11") (pintype "passive"))
      (node (ref "J7") (pin "80") (pinfunction "80_80") (pintype "passive"))
      (node (ref "J9") (pin "1_13") (pinfunction "13_1_13") (pintype "passive"))
    )
    (net (code "92") (name "19.I2C_SDA") (class "Default")
      (node (ref "J1") (pin "1_12") (pinfunction "12_1_12") (pintype "passive"))
      (node (ref "J7") (pin "82") (pinfunction "82_82") (pintype "passive"))
      (node (ref "J9") (pin "1_14") (pinfunction "14_1_14") (pintype "passive"))
    )
    (net (code "93") (name "19.NRESET_NRESET") (class "Default")
      (node (ref "C97") (pin "1") (pinfunction "1_1") (pintype "passive"))
      (node (ref "J7") (pin "92") (pinfunction "92_92") (pintype "passive"))
      (node (ref "R51") (pin "2") (pinfunction "2_2") (pintype "passive"))
    )
    (net (code "94") (name "19.PCIE_CLKREQ_GPIO") (class "Default")
      (node (ref "J2") (pin "2") (pinfunction "2_2") (pintype "passive"))
      (node (ref "U6") (pin "52") (pinfunction "~{CLKREQ}_52") (pintype "bidirectional"))
    )
    (net (code "95") (name "19.PCIE_CLK_N") (class "Default")
      (node (ref "J2") (pin "12") (pinfunction "12_12") (pintype "passive"))
      (node (ref "U6") (pin "55") (pinfunction "REFCLKP_55") (pintype "bidirectional"))
    )
    (net (code "96") (name "19.PCIE_CLK_P") (class "Default")
      (node (ref "J2") (pin "10") (pinfunction "10_10") (pintype "passive"))
      (node (ref "U6") (pin "53") (pinfunction "REFCLKN_53") (pintype "bidirectional"))
    )
    (net (code "97") (name "19.PCIE_RST_GPIO") (class "Default")
      (node (ref "J2") (pin "9") (pinfunction "9_9") (pintype "passive"))
      (node (ref "U6") (pin "50") (pinfunction "~{PERST}_50") (pintype "bidirectional"))
    )
    (net (code "98") (name "19.PCIE_RX0_N") (class "Default")
      (node (ref "J2") (pin "18") (pinfunction "18_18") (pintype "passive"))
      (node (ref "U6") (pin "41") (pinfunction "SATA_B+/PERN0_41") (pintype "bidirectional"))
    )
    (net (code "99") (name "19.PCIE_RX0_P") (class "Default")
      (node (ref "J2") (pin "16") (pinfunction "16_16") (pintype "passive"))
      (node (ref "U6") (pin "43") (pinfunction "SATA_B-/PERP0_43") (pintype "bidirectional"))
    )
    (net (code "100") (name "19.PCIE_TX0_N") (class "Default")
      (node (ref "J2") (pin "24") (pinfunction "24_24") (pintype "passive"))
      (node (ref "U6") (pin "47") (pinfunction "SATA_A-/PETN0_47") (pintype "bidirectional"))
    )
    (net (code "101") (name "19.PCIE_TX0_P") (class "Default")
      (node (ref "J2") (pin "22") (pinfunction "22_22") (pintype "passive"))
      (node (ref "U6") (pin "49") (pinfunction "SATA_A+/PETP0_49") (pintype "bidirectional"))
    )
    (net (code "102") (name "19.SYS_EN_SYSEN") (class "Default")
      (node (ref "J7") (pin "100") (pinfunction "100_100") (pintype "passive"))
      (node (ref "Q1") (pin "1") (pinfunction "G_1") (pintype "passive"))
      (node (ref "R36") (pin "2") (pinfunction "2_2") (pintype "passive"))
      (node (ref "R46") (pin "1") (pinfunction "1_1") (pintype "passive"))
      (node (ref "R5") (pin "2") (pinfunction "2_2") (pintype "passive"))
    )
    (net (code "103") (name "19.UART0_RXD") (class "Default")
      (node (ref "J7") (pin "51") (pinfunction "51_51") (pintype "passive"))
      (node (ref "RP1") (pin "8") (pinfunction "8_8") (pintype "passive"))
      (node (ref "RP2") (pin "5") (pinfunction "5_5") (pintype "passive"))
      (node (ref "U2") (pin "9") (pinfunction "COM2_9") (pintype "bidirectional"))
    )
    (net (code "104") (name "19.UART0_TXD") (class "Default")
      (node (ref "J7") (pin "55") (pinfunction "55_55") (pintype "passive"))
      (node (ref "RP1") (pin "7") (pinfunction "7_7") (pintype "passive"))
      (node (ref "RP2") (pin "6") (pinfunction "6_6") (pintype "passive"))
      (node (ref "U2") (pin "3") (pinfunction "COM1_3") (pintype "bidirectional"))
    )
    (net (code "105") (name "19.USB3_CC1_GPIO") (class "Default")
      (node (ref "J7") (pin "94") (pinfunction "94_94") (pintype "passive"))
    )
    (net (code "106") (name "19.USB3_CC2_GPIO") (class "Default")
      (node (ref "J7") (pin "96") (pinfunction "96_96") (pintype "passive"))
    )
    (net (code "107") (name "19.USB_HOST_D_N") (class "Default")
      (node (ref "J2") (pin "3") (pinfunction "3_3") (pintype "passive"))
      (node (ref "U26") (pin "5") (pinfunction "D-_5") (pintype "bidirectional"))
    )
    (net (code "108") (name "19.USB_HOST_D_P") (class "Default")
      (node (ref "J2") (pin "5") (pinfunction "5_5") (pintype "passive"))
      (node (ref "U26") (pin "3") (pinfunction "D+_3") (pintype "bidirectional"))
    )
    (net (code "109") (name "19.VLOGIC_VLOGIC") (class "Default")
      (node (ref "C106") (pin "1") (pinfunction "1_1") (pintype "passive"))
      (node (ref "C107") (pin "1") (pinfunction "1_1") (pintype "passive"))
      (node (ref "C109") (pin "1") (pinfunction "1_1") (pintype "passive"))
      (node (ref "C110") (pin "1") (pinfunction "1_1") (pintype "passive"))
      (node (ref "C15") (pin "1") (pinfunction "1_1") (pintype "passive"))
      (node (ref "C80") (pin "1") (pinfunction "1_1") (pintype "passive"))
      (node (ref "C83") (pin "1") (pinfunction "1_1") (pintype "passive"))
      (node (ref "IC3") (pin "1") (pinfunction "OE_1") (pintype "input"))
      (node (ref "IC3") (pin "5") (pinfunction "VCC_5") (pintype "power_in"))
      (node (ref "IC5") (pin "1") (pinfunction "VCCIO_1") (pintype "power_in"))
      (node (ref "R3") (pin "1") (pinfunction "1_1") (pintype "passive"))
      (node (ref "R30") (pin "2") (pinfunction "2_2") (pintype "passive"))
      (node (ref "R50") (pin "2") (pinfunction "2_2") (pintype "passive"))
      (node (ref "U$29") (pin "1") (pinfunction "VCCA_1") (pintype "power_in"))
      (node (ref "U$29") (pin "8") (pinfunction "OE_8") (pintype "input"))
      (node (ref "U2") (pin "1") (pinfunction "VCC_1") (pintype "power_in"))
    )
    (net (code "110") (name "21.USB1_D_N") (class "Default")
      (node (ref "L1") (pin "2") (pinfunction "2_2") (pintype "passive"))
      (node (ref "U26") (pin "7") (pinfunction "D1-_7") (pintype "bidirectional"))
    )
    (net (code "111") (name "21.USB1_D_P") (class "Default")
      (node (ref "L1") (pin "3") (pinfunction "3_3") (pintype "passive"))
      (node (ref "U26") (pin "1") (pinfunction "D1+_1") (pintype "bidirectional"))
    )
    (net (code "112") (name "21.USB1_NOC") (class "Default")
      (node (ref "IC1") (pin "5") (pinfunction "NOC_5") (pintype "output"))
    )
    (net (code "113") (name "21.USB1_VBUS") (class "Default")
      (node (ref "FB1") (pin "1") (pinfunction "1_1") (pintype "passive"))
      (node (ref "IC1") (pin "6") (pinfunction "OUT_6") (pintype "power_in"))
      (node (ref "IC1") (pin "7") (pinfunction "OUT_7") (pintype "power_in"))
      (node (ref "IC1") (pin "8") (pinfunction "OUT_8") (pintype "output"))
    )
    (net (code "114") (name "21.USB2_D_N") (class "Default")
      (node (ref "L5") (pin "2") (pinfunction "2_2") (pintype "passive"))
      (node (ref "U26") (pin "6") (pinfunction "D2-_6") (pintype "bidirectional"))
    )
    (net (code "115") (name "21.USB2_D_P") (class "Default")
      (node (ref "L5") (pin "3") (pinfunction "3_3") (pintype "passive"))
      (node (ref "U26") (pin "2") (pinfunction "D2+_2") (pintype "bidirectional"))
    )
    (net (code "116") (name "21.USB2_VBUS") (class "Default")
      (node (ref "R27") (pin "2") (pinfunction "2_2") (pintype "passive"))
      (node (ref "R37") (pin "1") (pinfunction "1_1") (pintype "passive"))
      (node (ref "U26") (pin "10") (pinfunction "S_10") (pintype "input"))
    )
    (net (code "117") (name "CEC$17") (class "Default")
      (node (ref "RP3") (pin "5") (pinfunction "5_5") (pintype "passive"))
      (node (ref "U$29") (pin "13") (pinfunction "B1_13") (pintype "bidirectional"))
      (node (ref "U3") (pin "13") (pinfunction "13_13") (pintype "passive"))
      (node (ref "U8") (pin "1") (pinfunction "CTRL1_1") (pintype "bidirectional"))
    )
    (net (code "118") (name "COMMON_SHIELD") (class "Default")
      (node (ref "D1") (pin "P1") (pinfunction "P1_P1") (pintype "passive"))
      (node (ref "D11") (pin "P1") (pinfunction "P1_P1") (pintype "passive"))
      (node (ref "D12") (pin "P1") (pinfunction "P1_P1") (pintype "passive"))
      (node (ref "D13") (pin "P1") (pinfunction "P1_P1") (pintype "passive"))
      (node (ref "D14") (pin "P1") (pinfunction "P1_P1") (pintype "passive"))
      (node (ref "D16") (pin "P1") (pinfunction "P1_P1") (pintype "passive"))
      (node (ref "D17") (pin "P1") (pinfunction "P1_P1") (pintype "passive"))
      (node (ref "D18") (pin "P1") (pinfunction "P1_P1") (pintype "passive"))
      (node (ref "D2") (pin "P1") (pinfunction "P1_P1") (pintype "passive"))
      (node (ref "D3") (pin "P1") (pinfunction "P1_P1") (pintype "passive"))
      (node (ref "D4") (pin "P1") (pinfunction "P1_P1") (pintype "passive"))
      (node (ref "D5") (pin "P1") (pinfunction "P1_P1") (pintype "passive"))
      (node (ref "D7") (pin "A") (pinfunction "1_A") (pintype "passive"))
      (node (ref "J4") (pin "15") (pinfunction "COMMON_SHIELD0_15") (pintype "bidirectional"))
      (node (ref "J4") (pin "16") (pinfunction "COMMON_SHIELD1_16") (pintype "bidirectional"))
      (node (ref "J5") (pin "COMMON_SHEILD1") (pinfunction "COMMON_SHIELD1_COMMON_SHEILD1") (pintype "bidirectional"))
      (node (ref "J5") (pin "COMMON_SHEILD2") (pinfunction "COMMON_SHIELD2_COMMON_SHEILD2") (pintype "bidirectional"))
      (node (ref "J5") (pin "COMMON_SHEILD3") (pinfunction "COMMON_SHIELD3_COMMON_SHEILD3") (pintype "bidirectional"))
      (node (ref "J5") (pin "COMMON_SHEILD4") (pinfunction "COMMON_SHIELD4_COMMON_SHEILD4") (pintype "bidirectional"))
      (node (ref "J5") (pin "COMMON_SHEILD5") (pinfunction "COMMON_SHIELD5_COMMON_SHEILD5") (pintype "bidirectional"))
      (node (ref "J5") (pin "COMMON_SHEILD6") (pinfunction "COMMON_SHIELD6_COMMON_SHEILD6") (pintype "bidirectional"))
      (node (ref "J6") (pin "COMMON_SHEILD1") (pinfunction "COMMON_SHIELD1_COMMON_SHEILD1") (pintype "bidirectional"))
      (node (ref "J6") (pin "COMMON_SHEILD2") (pinfunction "COMMON_SHIELD2_COMMON_SHEILD2") (pintype "bidirectional"))
      (node (ref "J6") (pin "COMMON_SHEILD3") (pinfunction "COMMON_SHIELD3_COMMON_SHEILD3") (pintype "bidirectional"))
      (node (ref "J6") (pin "COMMON_SHEILD4") (pinfunction "COMMON_SHIELD4_COMMON_SHEILD4") (pintype "bidirectional"))
      (node (ref "J6") (pin "COMMON_SHEILD5") (pinfunction "COMMON_SHIELD5_COMMON_SHEILD5") (pintype "bidirectional"))
      (node (ref "J6") (pin "COMMON_SHEILD6") (pinfunction "COMMON_SHIELD6_COMMON_SHEILD6") (pintype "bidirectional"))
      (node (ref "J8") (pin "P$5") (pinfunction "P1_P$5") (pintype "passive"))
      (node (ref "J8") (pin "P$6") (pinfunction "P2_P$6") (pintype "passive"))
      (node (ref "R22") (pin "2") (pinfunction "2_2") (pintype "passive"))
      (node (ref "U1") (pin "3") (pinfunction "SHIELD_3") (pintype "passive"))
      (node (ref "U1") (pin "8") (pinfunction "SHIELD_8") (pintype "passive"))
      (node (ref "U3") (pin "G1") (pinfunction "20_G1") (pintype "passive"))
      (node (ref "U3") (pin "G2") (pinfunction "21_G2") (pintype "passive"))
      (node (ref "U3") (pin "G3") (pinfunction "22_G3") (pintype "passive"))
      (node (ref "U3") (pin "G4") (pinfunction "23_G4") (pintype "passive"))
      (node (ref "U5") (pin "3") (pinfunction "SHIELD_3") (pintype "passive"))
      (node (ref "U5") (pin "8") (pinfunction "SHIELD_8") (pintype "passive"))
    )
    (net (code "119") (name "CONFIG_0$6") (class "Default")
      (node (ref "U6") (pin "21") (pinfunction "CONFIG_0_21") (pintype "bidirectional"))
    )
    (net (code "120") (name "CONFIG_1$6") (class "Default")
      (node (ref "U6") (pin "69") (pinfunction "CONFIG_1_69") (pintype "bidirectional"))
    )
    (net (code "121") (name "CONFIG_2$6") (class "Default")
      (node (ref "U6") (pin "75") (pinfunction "CONFIG_2_75") (pintype "bidirectional"))
    )
    (net (code "122") (name "CONFIG_3$6") (class "Default")
      (node (ref "U6") (pin "1") (pinfunction "CONFIG_3_1") (pintype "bidirectional"))
    )
    (net (code "123") (name "CON_5V0$17") (class "Default")
      (node (ref "C105") (pin "1") (pinfunction "1_1") (pintype "passive"))
      (node (ref "U3") (pin "18") (pinfunction "18_18") (pintype "passive"))
      (node (ref "U8") (pin "6") (pinfunction "5V_OUT_6") (pintype "power_in"))
    )
    (net (code "124") (name "DDC_SCL$17") (class "Default")
      (node (ref "RP3") (pin "6") (pinfunction "6_6") (pintype "passive"))
      (node (ref "U$29") (pin "12") (pinfunction "B2_12") (pintype "bidirectional"))
      (node (ref "U3") (pin "15") (pinfunction "15_15") (pintype "passive"))
      (node (ref "U8") (pin "2") (pinfunction "CTRL2_2") (pintype "bidirectional"))
    )
    (net (code "125") (name "DDC_SDA$17") (class "Default")
      (node (ref "RP3") (pin "7") (pinfunction "7_7") (pintype "passive"))
      (node (ref "U$29") (pin "11") (pinfunction "B3_11") (pintype "bidirectional"))
      (node (ref "U3") (pin "16") (pinfunction "16_16") (pintype "passive"))
      (node (ref "U8") (pin "3") (pinfunction "CTRL3_3") (pintype "bidirectional"))
    )
    (net (code "126") (name "DEVICE_ACTIVITY$6") (class "Default")
      (node (ref "U6") (pin "10") (pinfunction "DAS/DSS_10") (pintype "bidirectional"))
    )
    (net (code "127") (name "DEVSLP$6") (class "Default")
      (node (ref "U6") (pin "38") (pinfunction "DEVSLP_38") (pintype "bidirectional"))
    )
    (net (code "128") (name "D_N$4") (class "Default")
      (node (ref "D11") (pin "P2") (pinfunction "P2_P2") (pintype "passive"))
      (node (ref "J6") (pin "P2") (pinfunction "D-_P2") (pintype "bidirectional"))
      (node (ref "L8") (pin "1") (pinfunction "1_1") (pintype "passive"))
    )
    (net (code "129") (name "D_N$16") (class "Default")
      (node (ref "D17") (pin "P2") (pinfunction "P2_P2") (pintype "passive"))
      (node (ref "J5") (pin "P2") (pinfunction "D-_P2") (pintype "bidirectional"))
      (node (ref "L5") (pin "1") (pinfunction "1_1") (pintype "passive"))
    )
    (net (code "130") (name "D_P$4") (class "Default")
      (node (ref "D12") (pin "P2") (pinfunction "P2_P2") (pintype "passive"))
      (node (ref "J6") (pin "P3") (pinfunction "D+_P3") (pintype "bidirectional"))
      (node (ref "L8") (pin "4") (pinfunction "4_4") (pintype "passive"))
    )
    (net (code "131") (name "D_P$16") (class "Default")
      (node (ref "D16") (pin "P2") (pinfunction "P2_P2") (pintype "passive"))
      (node (ref "J5") (pin "P3") (pinfunction "D+_P3") (pintype "bidirectional"))
      (node (ref "L5") (pin "4") (pinfunction "4_4") (pintype "passive"))
    )
    (net (code "132") (name "EEPROM_~{WP}") (class "Default")
      (node (ref "J7") (pin "20") (pinfunction "20_20") (pintype "passive"))
    )
    (net (code "133") (name "ETH_SYNC_IN") (class "Default")
      (node (ref "J7") (pin "16") (pinfunction "16_16") (pintype "passive"))
    )
    (net (code "134") (name "ETH_SYNC_OUT") (class "Default")
      (node (ref "J7") (pin "18") (pinfunction "18_18") (pintype "passive"))
    )
    (net (code "135") (name "FB_3.3$3") (class "Default")
      (node (ref "C91") (pin "2") (pinfunction "2_2") (pintype "passive"))
      (node (ref "IC4") (pin "10") (pinfunction "FB_10") (pintype "output"))
      (node (ref "R21") (pin "1") (pinfunction "1_1") (pintype "passive"))
      (node (ref "R24") (pin "2") (pinfunction "2_2") (pintype "passive"))
    )
    (net (code "136") (name "FTDI_3.3_INT$1") (class "Default")
      (node (ref "C82") (pin "1") (pinfunction "1_1") (pintype "passive"))
      (node (ref "IC5") (pin "16") (pinfunction "3V3OUT_16") (pintype "output"))
    )
    (net (code "137") (name "GLOBAL_EN") (class "Default")
      (node (ref "J7") (pin "99") (pinfunction "99_99") (pintype "passive"))
    )
    (net (code "138") (name "GND") (class "Default")
      (node (ref "C100") (pin "2") (pinfunction "2_2") (pintype "passive"))
      (node (ref "C102") (pin "2") (pinfunction "2_2") (pintype "passive"))
      (node (ref "C103") (pin "2") (pinfunction "2_2") (pintype "passive"))
      (node (ref "C104") (pin "2") (pinfunction "2_2") (pintype "passive"))
      (node (ref "C105") (pin "2") (pinfunction "2_2") (pintype "passive"))
      (node (ref "C106") (pin "2") (pinfunction "2_2") (pintype "passive"))
      (node (ref "C107") (pin "2") (pinfunction "2_2") (pintype "passive"))
      (node (ref "C108") (pin "2") (pinfunction "2_2") (pintype "passive"))
      (node (ref "C109") (pin "2") (pinfunction "2_2") (pintype "passive"))
      (node (ref "C110") (pin "2") (pinfunction "2_2") (pintype "passive"))
      (node (ref "C111") (pin "2") (pinfunction "2_2") (pintype "passive"))
      (node (ref "C13") (pin "2") (pinfunction "2_2") (pintype "passive"))
      (node (ref "C15") (pin "2") (pinfunction "2_2") (pintype "passive"))
      (node (ref "C17") (pin "2") (pinfunction "2_2") (pintype "passive"))
      (node (ref "C18") (pin "2") (pinfunction "2_2") (pintype "passive"))
      (node (ref "C2") (pin "2") (pinfunction "2_2") (pintype "passive"))
      (node (ref "C3") (pin "2") (pinfunction "2_2") (pintype "passive"))
      (node (ref "C30") (pin "2") (pinfunction "2_2") (pintype "passive"))
      (node (ref "C4") (pin "2") (pinfunction "2_2") (pintype "passive"))
      (node (ref "C5") (pin "2") (pinfunction "2_2") (pintype "passive"))
      (node (ref "C6") (pin "2") (pinfunction "2_2") (pintype "passive"))
      (node (ref "C7") (pin "2") (pinfunction "2_2") (pintype "passive"))
      (node (ref "C78") (pin "2") (pinfunction "2_2") (pintype "passive"))
      (node (ref "C79") (pin "-") (pinfunction "2_-") (pintype "passive"))
      (node (ref "C8") (pin "2") (pinfunction "2_2") (pintype "passive"))
      (node (ref "C80") (pin "2") (pinfunction "2_2") (pintype "passive"))
      (node (ref "C81") (pin "2") (pinfunction "2_2") (pintype "passive"))
      (node (ref "C82") (pin "2") (pinfunction "2_2") (pintype "passive"))
      (node (ref "C83") (pin "2") (pinfunction "2_2") (pintype "passive"))
      (node (ref "C84") (pin "2") (pinfunction "2_2") (pintype "passive"))
      (node (ref "C85") (pin "2") (pinfunction "2_2") (pintype "passive"))
      (node (ref "C86") (pin "2") (pinfunction "2_2") (pintype "passive"))
      (node (ref "C87") (pin "2") (pinfunction "2_2") (pintype "passive"))
      (node (ref "C88") (pin "2") (pinfunction "2_2") (pintype "passive"))
      (node (ref "C89") (pin "2") (pinfunction "2_2") (pintype "passive"))
      (node (ref "C90") (pin "2") (pinfunction "2_2") (pintype "passive"))
      (node (ref "C92") (pin "2") (pinfunction "2_2") (pintype "passive"))
      (node (ref "C93") (pin "2") (pinfunction "2_2") (pintype "passive"))
      (node (ref "C94") (pin "2") (pinfunction "2_2") (pintype "passive"))
      (node (ref "C95") (pin "2") (pinfunction "2_2") (pintype "passive"))
      (node (ref "C96") (pin "2") (pinfunction "2_2") (pintype "passive"))
      (node (ref "C97") (pin "2") (pinfunction "2_2") (pintype "passive"))
      (node (ref "C98") (pin "2") (pinfunction "2_2") (pintype "passive"))
      (node (ref "C99") (pin "2") (pinfunction "2_2") (pintype "passive"))
      (node (ref "D14") (pin "P2") (pinfunction "P2_P2") (pintype "passive"))
      (node (ref "D5") (pin "P2") (pinfunction "P2_P2") (pintype "passive"))
      (node (ref "D6") (pin "A") (pinfunction "A_A") (pintype "passive"))
      (node (ref "D8") (pin "P1") (pinfunction "P1_P1") (pintype "passive"))
      (node (ref "D9") (pin "P1") (pinfunction "P1_P1") (pintype "passive"))
      (node (ref "FB2") (pin "1") (pinfunction "1_1") (pintype "passive"))
      (node (ref "IC1") (pin "1") (pinfunction "GND_1") (pintype "bidirectional"))
      (node (ref "IC1") (pin "TP") (pinfunction "GND_TP") (pintype "bidirectional"))
      (node (ref "IC3") (pin "3") (pinfunction "GND_3") (pintype "power_in"))
      (node (ref "IC4") (pin "1") (pinfunction "PGND_1") (pintype "power_in"))
      (node (ref "IC4") (pin "11") (pinfunction "GND_11") (pintype "power_in"))
      (node (ref "IC4") (pin "12") (pinfunction "GND_12") (pintype "power_in"))
      (node (ref "IC4") (pin "16") (pinfunction "PGND_16") (pintype "power_in"))
      (node (ref "IC4") (pin "5") (pinfunction "SYNC_5") (pintype "input"))
      (node (ref "IC4") (pin "6") (pinfunction "LBO_6") (pintype "passive"))
      (node (ref "IC4") (pin "7") (pinfunction "LBI_7") (pintype "input"))
      (node (ref "IC4") (pin "9") (pinfunction "GND_9") (pintype "power_in"))
      (node (ref "IC4") (pin "P$1") (pinfunction "GND_P$1") (pintype "power_in"))
      (node (ref "IC5") (pin "17") (pinfunction "GND_17") (pintype "power_in"))
      (node (ref "IC5") (pin "20") (pinfunction "GND_20") (pintype "power_in"))
      (node (ref "IC5") (pin "24") (pinfunction "GND_24") (pintype "power_in"))
      (node (ref "IC5") (pin "26") (pinfunction "TEST_26") (pintype "input"))
      (node (ref "IC5") (pin "4") (pinfunction "GND_4") (pintype "power_in"))
      (node (ref "IC6") (pin "4") (pinfunction "GND_4") (pintype "power_in"))
      (node (ref "IC6") (pin "7") (pinfunction "WP_7") (pintype "input"))
      (node (ref "J1") (pin "1_1") (pinfunction "1_1_1") (pintype "passive"))
      (node (ref "J1") (pin "1_10") (pinfunction "10_1_10") (pintype "passive"))
      (node (ref "J1") (pin "1_13") (pinfunction "13_1_13") (pintype "passive"))
      (node (ref "J1") (pin "1_4") (pinfunction "4_1_4") (pintype "passive"))
      (node (ref "J1") (pin "1_7") (pinfunction "7_1_7") (pintype "passive"))
      (node (ref "J10") (pin "1_1") (pinfunction "1_1_1") (pintype "passive"))
      (node (ref "J10") (pin "1_10") (pinfunction "10_1_10") (pintype "passive"))
      (node (ref "J10") (pin "1_4") (pinfunction "4_1_4") (pintype "passive"))
      (node (ref "J10") (pin "1_7") (pinfunction "7_1_7") (pintype "passive"))
      (node (ref "J2") (pin "13") (pinfunction "13_13") (pintype "passive"))
      (node (ref "J2") (pin "14") (pinfunction "14_14") (pintype "passive"))
      (node (ref "J2") (pin "19") (pinfunction "19_19") (pintype "passive"))
      (node (ref "J2") (pin "20") (pinfunction "20_20") (pintype "passive"))
      (node (ref "J2") (pin "25") (pinfunction "25_25") (pintype "passive"))
      (node (ref "J2") (pin "26") (pinfunction "26_26") (pintype "passive"))
      (node (ref "J2") (pin "31") (pinfunction "31_31") (pintype "passive"))
      (node (ref "J2") (pin "32") (pinfunction "32_32") (pintype "passive"))
      (node (ref "J2") (pin "37") (pinfunction "37_37") (pintype "passive"))
      (node (ref "J2") (pin "38") (pinfunction "38_38") (pintype "passive"))
      (node (ref "J2") (pin "44") (pinfunction "44_44") (pintype "passive"))
      (node (ref "J2") (pin "50") (pinfunction "50_50") (pintype "passive"))
      (node (ref "J2") (pin "55") (pinfunction "55_55") (pintype "passive"))
      (node (ref "J2") (pin "56") (pinfunction "56_56") (pintype "passive"))
      (node (ref "J2") (pin "61") (pinfunction "61_61") (pintype "passive"))
      (node (ref "J2") (pin "62") (pinfunction "62_62") (pintype "passive"))
      (node (ref "J2") (pin "67") (pinfunction "67_67") (pintype "passive"))
      (node (ref "J2") (pin "68") (pinfunction "68_68") (pintype "passive"))
      (node (ref "J2") (pin "7") (pinfunction "7_7") (pintype "passive"))
      (node (ref "J2") (pin "73") (pinfunction "73_73") (pintype "passive"))
      (node (ref "J2") (pin "74") (pinfunction "74_74") (pintype "passive"))
      (node (ref "J2") (pin "79") (pinfunction "79_79") (pintype "passive"))
      (node (ref "J2") (pin "8") (pinfunction "8_8") (pintype "passive"))
      (node (ref "J2") (pin "80") (pinfunction "80_80") (pintype "passive"))
      (node (ref "J2") (pin "85") (pinfunction "85_85") (pintype "passive"))
      (node (ref "J2") (pin "86") (pinfunction "86_86") (pintype "passive"))
      (node (ref "J2") (pin "91") (pinfunction "91_91") (pintype "passive"))
      (node (ref "J2") (pin "92") (pinfunction "92_92") (pintype "passive"))
      (node (ref "J2") (pin "97") (pinfunction "97_97") (pintype "passive"))
      (node (ref "J2") (pin "98") (pinfunction "98_98") (pintype "passive"))
      (node (ref "J3") (pin "2") (pinfunction "GND_2") (pintype "power_in"))
      (node (ref "J3") (pin "3") (pinfunction "2_3") (pintype "passive"))
      (node (ref "J5") (pin "P5") (pinfunction "GND_P5") (pintype "bidirectional"))
      (node (ref "J6") (pin "P5") (pinfunction "GND_P5") (pintype "bidirectional"))
      (node (ref "J7") (pin "1") (pinfunction "1_1") (pintype "passive"))
      (node (ref "J7") (pin "13") (pinfunction "13_13") (pintype "passive"))
      (node (ref "J7") (pin "14") (pinfunction "14_14") (pintype "passive"))
      (node (ref "J7") (pin "2") (pinfunction "2_2") (pintype "passive"))
      (node (ref "J7") (pin "22") (pinfunction "22_22") (pintype "passive"))
      (node (ref "J7") (pin "23") (pinfunction "23_23") (pintype "passive"))
      (node (ref "J7") (pin "32") (pinfunction "32_32") (pintype "passive"))
      (node (ref "J7") (pin "33") (pinfunction "33_33") (pintype "passive"))
      (node (ref "J7") (pin "42") (pinfunction "42_42") (pintype "passive"))
      (node (ref "J7") (pin "43") (pinfunction "43_43") (pintype "passive"))
      (node (ref "J7") (pin "52") (pinfunction "52_52") (pintype "passive"))
      (node (ref "J7") (pin "53") (pinfunction "53_53") (pintype "passive"))
      (node (ref "J7") (pin "59") (pinfunction "59_59") (pintype "passive"))
      (node (ref "J7") (pin "60") (pinfunction "60_60") (pintype "passive"))
      (node (ref "J7") (pin "65") (pinfunction "65_65") (pintype "passive"))
      (node (ref "J7") (pin "66") (pinfunction "66_66") (pintype "passive"))
      (node (ref "J7") (pin "7") (pinfunction "7_7") (pintype "passive"))
      (node (ref "J7") (pin "71") (pinfunction "71_71") (pintype "passive"))
      (node (ref "J7") (pin "74") (pinfunction "74_74") (pintype "passive"))
      (node (ref "J7") (pin "8") (pinfunction "8_8") (pintype "passive"))
      (node (ref "J7") (pin "98") (pinfunction "98_98") (pintype "passive"))
      (node (ref "J9") (pin "1_1") (pinfunction "1_1_1") (pintype "passive"))
      (node (ref "J9") (pin "1_10") (pinfunction "10_1_10") (pintype "passive"))
      (node (ref "J9") (pin "1_4") (pinfunction "4_1_4") (pintype "passive"))
      (node (ref "J9") (pin "1_7") (pinfunction "7_1_7") (pintype "passive"))
      (node (ref "MP1") (pin "1") (pinfunction "TP_1") (pintype "bidirectional"))
      (node (ref "MP2") (pin "1") (pinfunction "TP_1") (pintype "bidirectional"))
      (node (ref "MP3") (pin "1") (pinfunction "TP_1") (pintype "bidirectional"))
      (node (ref "MP4") (pin "1") (pinfunction "TP_1") (pintype "bidirectional"))
      (node (ref "MP5") (pin "1") (pinfunction "TP_1") (pintype "bidirectional"))
      (node (ref "Q1") (pin "2") (pinfunction "S_2") (pintype "passive"))
      (node (ref "Q4") (pin "2") (pinfunction "S_2") (pintype "passive"))
      (node (ref "Q5") (pin "2") (pinfunction "GND_2") (pintype "power_in"))
      (node (ref "Q6") (pin "2") (pinfunction "S_2") (pintype "passive"))
      (node (ref "R11") (pin "1") (pinfunction "1_1") (pintype "passive"))
      (node (ref "R17") (pin "2") (pinfunction "2_2") (pintype "passive"))
      (node (ref "R22") (pin "1") (pinfunction "1_1") (pintype "passive"))
      (node (ref "R24") (pin "1") (pinfunction "1_1") (pintype "passive"))
      (node (ref "R27") (pin "1") (pinfunction "1_1") (pintype "passive"))
      (node (ref "R28") (pin "1") (pinfunction "1_1") (pintype "passive"))
      (node (ref "R34") (pin "1") (pinfunction "1_1") (pintype "passive"))
      (node (ref "R36") (pin "1") (pinfunction "1_1") (pintype "passive"))
      (node (ref "R38") (pin "1") (pinfunction "1_1") (pintype "passive"))
      (node (ref "R44") (pin "1") (pinfunction "1_1") (pintype "passive"))
      (node (ref "R5") (pin "1") (pinfunction "1_1") (pintype "passive"))
      (node (ref "R6") (pin "1") (pinfunction "1_1") (pintype "passive"))
      (node (ref "R7") (pin "1") (pinfunction "1_1") (pintype "passive"))
      (node (ref "S2") (pin "A@1") (pinfunction "A_A@1") (pintype "passive"))
      (node (ref "S3") (pin "A@1") (pinfunction "A_A@1") (pintype "passive"))
      (node (ref "U$29") (pin "7") (pinfunction "GND_7") (pintype "power_in"))
      (node (ref "U2") (pin "6") (pinfunction "GND_6") (pintype "power_in"))
      (node (ref "U26") (pin "4") (pinfunction "GND_4") (pintype "power_in"))
      (node (ref "U3") (pin "11") (pinfunction "11_11") (pintype "passive"))
      (node (ref "U3") (pin "17") (pinfunction "17_17") (pintype "passive"))
      (node (ref "U3") (pin "2") (pinfunction "2_2") (pintype "passive"))
      (node (ref "U3") (pin "5") (pinfunction "5_5") (pintype "passive"))
      (node (ref "U3") (pin "8") (pinfunction "8_8") (pintype "passive"))
      (node (ref "U4") (pin "14") (pinfunction "14_14") (pintype "passive"))
      (node (ref "U4") (pin "20") (pinfunction "20_20") (pintype "passive"))
      (node (ref "U4") (pin "25") (pinfunction "25_25") (pintype "passive"))
      (node (ref "U4") (pin "30") (pinfunction "30_30") (pintype "passive"))
      (node (ref "U4") (pin "34") (pinfunction "34_34") (pintype "passive"))
      (node (ref "U4") (pin "39") (pinfunction "39_39") (pintype "passive"))
      (node (ref "U4") (pin "6") (pinfunction "6_6") (pintype "passive"))
      (node (ref "U4") (pin "9") (pinfunction "9_9") (pintype "passive"))
      (node (ref "U6") (pin "15") (pinfunction "GND_15") (pintype "bidirectional"))
      (node (ref "U6") (pin "27") (pinfunction "GND_27") (pintype "bidirectional"))
      (node (ref "U6") (pin "3") (pinfunction "GND_3") (pintype "bidirectional"))
      (node (ref "U6") (pin "33") (pinfunction "GND_33") (pintype "bidirectional"))
      (node (ref "U6") (pin "39") (pinfunction "GND_39") (pintype "bidirectional"))
      (node (ref "U6") (pin "45") (pinfunction "GND_45") (pintype "bidirectional"))
      (node (ref "U6") (pin "51") (pinfunction "GND_51") (pintype "bidirectional"))
      (node (ref "U6") (pin "57") (pinfunction "GND_57") (pintype "bidirectional"))
      (node (ref "U6") (pin "71") (pinfunction "GND_71") (pintype "bidirectional"))
      (node (ref "U6") (pin "73") (pinfunction "GND_73") (pintype "bidirectional"))
      (node (ref "U6") (pin "9") (pinfunction "GND_9") (pintype "bidirectional"))
      (node (ref "U6") (pin "P$1") (pinfunction "GND_P$1") (pintype "bidirectional"))
      (node (ref "U6") (pin "P$2") (pinfunction "GND_P$2") (pintype "bidirectional"))
      (node (ref "U7") (pin "6") (pinfunction "GND1_6") (pintype "bidirectional"))
      (node (ref "U7") (pin "9") (pinfunction "GND2_9") (pintype "bidirectional"))
      (node (ref "U7") (pin "PWRPAD1") (pinfunction "GND2_PWRPAD1") (pintype "bidirectional"))
      (node (ref "U7") (pin "PWRPAD2") (pinfunction "GND2_PWRPAD2") (pintype "bidirectional"))
      (node (ref "U7") (pin "PWRPAD3") (pinfunction "GND2_PWRPAD3") (pintype "bidirectional"))
      (node (ref "U7") (pin "PWRPAD4") (pinfunction "GND2_PWRPAD4") (pintype "bidirectional"))
      (node (ref "U7") (pin "PWRPAD5") (pinfunction "GND2_PWRPAD5") (pintype "bidirectional"))
      (node (ref "U7") (pin "PWRPAD6") (pinfunction "GND2_PWRPAD6") (pintype "bidirectional"))
      (node (ref "U7") (pin "PWRPAD7") (pinfunction "GND2_PWRPAD7") (pintype "bidirectional"))
      (node (ref "U7") (pin "PWRPAD8") (pinfunction "GND2_PWRPAD8") (pintype "bidirectional"))
      (node (ref "U8") (pin "8") (pinfunction "GND_8") (pintype "power_in"))
    )
    (net (code "139") (name "GPIO_VREF$19") (class "Default")
      (node (ref "C6") (pin "1") (pinfunction "1_1") (pintype "passive"))
      (node (ref "IC6") (pin "8") (pinfunction "VCC_8") (pintype "power_in"))
      (node (ref "J7") (pin "78") (pinfunction "78_78") (pintype "passive"))
      (node (ref "R1") (pin "2") (pinfunction "2_2") (pintype "passive"))
      (node (ref "R10") (pin "2") (pinfunction "2_2") (pintype "passive"))
      (node (ref "R2") (pin "2") (pinfunction "2_2") (pintype "passive"))
      (node (ref "R8") (pin "1") (pinfunction "1_1") (pintype "passive"))
      (node (ref "R9") (pin "2") (pinfunction "2_2") (pintype "passive"))
    )
    (net (code "140") (name "HPD$17") (class "Default")
      (node (ref "RP3") (pin "8") (pinfunction "8_8") (pintype "passive"))
      (node (ref "U$29") (pin "10") (pinfunction "B4_10") (pintype "bidirectional"))
      (node (ref "U3") (pin "19") (pinfunction "19_19") (pintype "passive"))
      (node (ref "U8") (pin "4") (pinfunction "CTRL4_4") (pintype "bidirectional"))
    )
    (net (code "141") (name "ID$4") (class "Default")
      (node (ref "J6") (pin "P4") (pinfunction "ID_P4") (pintype "bidirectional"))
    )
    (net (code "142") (name "ID$16") (class "Default")
      (node (ref "J5") (pin "P4") (pinfunction "ID_P4") (pintype "bidirectional"))
    )
    (net (code "143") (name "MFG1$6") (class "Default")
      (node (ref "U6") (pin "56") (pinfunction "MFG1_56") (pintype "bidirectional"))
    )
    (net (code "144") (name "MFG2$6") (class "Default")
      (node (ref "U6") (pin "58") (pinfunction "MFG2_58") (pintype "bidirectional"))
    )
    (net (code "145") (name "Net-(D10-PadA)") (class "Default")
      (node (ref "D10") (pin "A") (pinfunction "A_A") (pintype "passive"))
      (node (ref "R33") (pin "1") (pinfunction "1_1") (pintype "passive"))
    )
    (net (code "146") (name "Net-(D15-PadA)") (class "Default")
      (node (ref "D15") (pin "A") (pinfunction "A_A") (pintype "passive"))
      (node (ref "R35") (pin "1") (pinfunction "1_1") (pintype "passive"))
    )
    (net (code "147") (name "Net-(IC6-A0)") (class "Default")
      (node (ref "IC6") (pin "1") (pinfunction "A0_1") (pintype "input"))
      (node (ref "R8") (pin "2") (pinfunction "2_2") (pintype "passive"))
    )
    (net (code "148") (name "Net-(IC6-A1)") (class "Default")
      (node (ref "IC6") (pin "2") (pinfunction "A1_2") (pintype "input"))
      (node (ref "R7") (pin "2") (pinfunction "2_2") (pintype "passive"))
    )
    (net (code "149") (name "Net-(IC6-A2)") (class "Default")
      (node (ref "IC6") (pin "3") (pinfunction "A2_3") (pintype "input"))
      (node (ref "R6") (pin "2") (pinfunction "2_2") (pintype "passive"))
    )
    (net (code "150") (name "Net-(J4-LED_YELLOW+)") (class "Default")
      (node (ref "J4") (pin "14") (pinfunction "LED_YELLOW+_14") (pintype "bidirectional"))
      (node (ref "R26") (pin "2") (pinfunction "2_2") (pintype "passive"))
    )
    (net (code "151") (name "Net-(J4-TRDXCT0)") (class "Default")
      (node (ref "C100") (pin "1") (pinfunction "1_1") (pintype "passive"))
      (node (ref "C96") (pin "1") (pinfunction "1_1") (pintype "passive"))
      (node (ref "J4") (pin "5") (pinfunction "TRDXCT0_5") (pintype "bidirectional"))
      (node (ref "J4") (pin "6") (pinfunction "TRDXCT1_6") (pintype "bidirectional"))
    )
    (net (code "152") (name "Net-(Q1-D)") (class "Default")
      (node (ref "Q1") (pin "3") (pinfunction "D_3") (pintype "passive"))
      (node (ref "Q2") (pin "1") (pinfunction "G_1") (pintype "passive"))
      (node (ref "Q3") (pin "1") (pinfunction "G_1") (pintype "passive"))
    )
    (net (code "153") (name "Net-(Q2-S)") (class "Default")
      (node (ref "Q2") (pin "2") (pinfunction "S_2") (pintype "passive"))
      (node (ref "Q3") (pin "2") (pinfunction "S_2") (pintype "passive"))
    )
    (net (code "154") (name "Net-(Q4-D)") (class "Default")
      (node (ref "D15") (pin "C") (pinfunction "C_C") (pintype "passive"))
      (node (ref "Q4") (pin "3") (pinfunction "D_3") (pintype "passive"))
    )
    (net (code "155") (name "Net-(Q4-G)") (class "Default")
      (node (ref "Q4") (pin "1") (pinfunction "G_1") (pintype "passive"))
      (node (ref "R46") (pin "2") (pinfunction "2_2") (pintype "passive"))
    )
    (net (code "156") (name "Net-(Q6-D)") (class "Default")
      (node (ref "D10") (pin "C") (pinfunction "C_C") (pintype "passive"))
      (node (ref "Q6") (pin "3") (pinfunction "D_3") (pintype "passive"))
    )
    (net (code "157") (name "Net-(Q6-G)") (class "Default")
      (node (ref "Q6") (pin "1") (pinfunction "G_1") (pintype "passive"))
      (node (ref "R32") (pin "2") (pinfunction "2_2") (pintype "passive"))
    )
    (net (code "158") (name "Net-(S1-A')") (class "Default")
      (node (ref "R11") (pin "2") (pinfunction "2_2") (pintype "passive"))
      (node (ref "S1") (pin "1") (pinfunction "A_1") (pintype "passive"))
      (node (ref "S1") (pin "2") (pinfunction "A'_2") (pintype "passive"))
    )
    (net (code "159") (name "Net-(S2-B')") (class "Default")
      (node (ref "D8") (pin "P2") (pinfunction "P2_P2") (pintype "passive"))
      (node (ref "R50") (pin "1") (pinfunction "1_1") (pintype "passive"))
      (node (ref "R51") (pin "1") (pinfunction "1_1") (pintype "passive"))
      (node (ref "S2") (pin "B@2") (pinfunction "B'_B@2") (pintype "passive"))
    )
    (net (code "160") (name "Net-(S3-B')") (class "Default")
      (node (ref "D9") (pin "P2") (pinfunction "P2_P2") (pintype "passive"))
      (node (ref "R30") (pin "1") (pinfunction "1_1") (pintype "passive"))
      (node (ref "R31") (pin "1") (pinfunction "1_1") (pintype "passive"))
      (node (ref "S3") (pin "B@2") (pinfunction "B'_B@2") (pintype "passive"))
    )
    (net (code "161") (name "Net-(U7-BOOT)") (class "Default")
      (node (ref "C52") (pin "1") (pinfunction "1_1") (pintype "passive"))
      (node (ref "U7") (pin "1") (pinfunction "BOOT_1") (pintype "bidirectional"))
    )
    (net (code "162") (name "Net-(U7-PH)") (class "Default")
      (node (ref "C52") (pin "2") (pinfunction "2_2") (pintype "passive"))
      (node (ref "D6") (pin "C") (pinfunction "C_C") (pintype "passive"))
      (node (ref "L6") (pin "1") (pinfunction "1_1") (pintype "passive"))
      (node (ref "U7") (pin "8") (pinfunction "PH_8") (pintype "bidirectional"))
    )
    (net (code "163") (name "Net-(U7-VSENSE)") (class "Default")
      (node (ref "R12") (pin "2") (pinfunction "2_2") (pintype "passive"))
      (node (ref "R17") (pin "1") (pinfunction "1_1") (pintype "passive"))
      (node (ref "U7") (pin "4") (pinfunction "VSENSE_4") (pintype "bidirectional"))
    )
    (net (code "164") (name "Net-(U26-~{OE})") (class "Default")
      (node (ref "R28") (pin "2") (pinfunction "2_2") (pintype "passive"))
      (node (ref "U26") (pin "8") (pinfunction "~{OE}_8") (pintype "input"))
    )
    (net (code "165") (name "P27") (class "Default")
      (node (ref "U4") (pin "27") (pinfunction "27_27") (pintype "passive"))
    )
    (net (code "166") (name "P28") (class "Default")
      (node (ref "U4") (pin "28") (pinfunction "28_28") (pintype "passive"))
    )
    (net (code "167") (name "PG_3.3$3") (class "Default")
      (node (ref "IC4") (pin "13") (pinfunction "PG_13") (pintype "output"))
      (node (ref "R19") (pin "1") (pinfunction "1_1") (pintype "passive"))
    )
    (net (code "168") (name "PI_LED_~{PWR}") (class "Default")
      (node (ref "J7") (pin "95") (pinfunction "95_95") (pintype "passive"))
    )
    (net (code "169") (name "PI_~{LED_ACT}") (class "Default")
      (node (ref "J7") (pin "21") (pinfunction "21_21") (pintype "passive"))
    )
    (net (code "170") (name "RX_SW$1") (class "Default")
      (node (ref "IC3") (pin "2") (pinfunction "I_2") (pintype "input"))
      (node (ref "IC5") (pin "30") (pinfunction "TXD_30") (pintype "output"))
    )
    (net (code "171") (name "SD_PWR_ON") (class "Default")
      (node (ref "J7") (pin "75") (pinfunction "75_75") (pintype "passive"))
    )
    (net (code "172") (name "SD_VDD_OV") (class "Default")
      (node (ref "J7") (pin "73") (pinfunction "73_73") (pintype "passive"))
    )
    (net (code "173") (name "SUSCLK_32KHZ$6") (class "Default")
      (node (ref "Q5") (pin "3") (pinfunction "FO_3") (pintype "output"))
      (node (ref "U6") (pin "68") (pinfunction "SUSCLK_68") (pintype "bidirectional"))
    )
    (net (code "174") (name "SW_3.3$3") (class "Default")
      (node (ref "IC4") (pin "14") (pinfunction "SW_14") (pintype "input"))
      (node (ref "IC4") (pin "15") (pinfunction "SW_15") (pintype "input"))
      (node (ref "L7") (pin "1") (pinfunction "1_1") (pintype "passive"))
    )
    (net (code "175") (name "TXD0_CONN_N$17") (class "Default")
      (node (ref "L3") (pin "1") (pinfunction "1_1") (pintype "passive"))
      (node (ref "U3") (pin "9") (pinfunction "9_9") (pintype "passive"))
    )
    (net (code "176") (name "TXD0_CONN_P$17") (class "Default")
      (node (ref "L3") (pin "4") (pinfunction "4_4") (pintype "passive"))
      (node (ref "U3") (pin "7") (pinfunction "7_7") (pintype "passive"))
    )
    (net (code "177") (name "TXD1_CONN_N$17") (class "Default")
      (node (ref "L2") (pin "1") (pinfunction "1_1") (pintype "passive"))
      (node (ref "U3") (pin "6") (pinfunction "6_6") (pintype "passive"))
    )
    (net (code "178") (name "TXD1_CONN_P$17") (class "Default")
      (node (ref "L2") (pin "4") (pinfunction "4_4") (pintype "passive"))
      (node (ref "U3") (pin "4") (pinfunction "4_4") (pintype "passive"))
    )
    (net (code "179") (name "TXD2_CONN_N$17") (class "Default")
      (node (ref "L9") (pin "1") (pinfunction "1_1") (pintype "passive"))
      (node (ref "U3") (pin "3") (pinfunction "3_3") (pintype "passive"))
    )
    (net (code "180") (name "TXD2_CONN_P$17") (class "Default")
      (node (ref "L9") (pin "4") (pinfunction "4_4") (pintype "passive"))
      (node (ref "U3") (pin "1") (pinfunction "1_1") (pintype "passive"))
    )
    (net (code "181") (name "TXDC_CONN_N$17") (class "Default")
      (node (ref "L4") (pin "1") (pinfunction "1_1") (pintype "passive"))
      (node (ref "U3") (pin "12") (pinfunction "12_12") (pintype "passive"))
    )
    (net (code "182") (name "TXDC_CONN_P$17") (class "Default")
      (node (ref "L4") (pin "4") (pinfunction "4_4") (pintype "passive"))
      (node (ref "U3") (pin "10") (pinfunction "10_10") (pintype "passive"))
    )
    (net (code "183") (name "UART_SEL$") (class "Default")
      (node (ref "R13") (pin "1") (pinfunction "1_1") (pintype "passive"))
      (node (ref "R44") (pin "2") (pinfunction "2_2") (pintype "passive"))
      (node (ref "U2") (pin "4") (pinfunction "SEL1_4") (pintype "input"))
      (node (ref "U2") (pin "8") (pinfunction "SEL2_8") (pintype "input"))
    )
    (net (code "184") (name "USBH_GND$20") (class "Default")
      (node (ref "D3") (pin "P2") (pinfunction "P2_P2") (pintype "passive"))
      (node (ref "FB2") (pin "2") (pinfunction "2_2") (pintype "passive"))
      (node (ref "J8") (pin "GND") (pinfunction "GND_GND") (pintype "passive"))
    )
    (net (code "185") (name "USBH_N$20") (class "Default")
      (node (ref "D2") (pin "P2") (pinfunction "P2_P2") (pintype "passive"))
      (node (ref "J8") (pin "D-") (pinfunction "D-_D-") (pintype "passive"))
      (node (ref "L1") (pin "1") (pinfunction "1_1") (pintype "passive"))
    )
    (net (code "186") (name "USBH_P$20") (class "Default")
      (node (ref "D1") (pin "P2") (pinfunction "P2_P2") (pintype "passive"))
      (node (ref "J8") (pin "D+") (pinfunction "VBUS_D+") (pintype "passive"))
      (node (ref "L1") (pin "4") (pinfunction "4_4") (pintype "passive"))
    )
    (net (code "187") (name "USBH_VBUSF$20") (class "Default")
      (node (ref "C2") (pin "1") (pinfunction "1_1") (pintype "passive"))
      (node (ref "C3") (pin "1") (pinfunction "1_1") (pintype "passive"))
      (node (ref "D4") (pin "P2") (pinfunction "P2_P2") (pintype "passive"))
      (node (ref "FB1") (pin "2") (pinfunction "2_2") (pintype "passive"))
      (node (ref "J8") (pin "VBUS") (pinfunction "D+_VBUS") (pintype "passive"))
    )
    (net (code "188") (name "UTIL$17") (class "Default")
      (node (ref "R38") (pin "2") (pinfunction "2_2") (pintype "passive"))
      (node (ref "U3") (pin "14") (pinfunction "14_14") (pintype "passive"))
      (node (ref "U8") (pin "7") (pinfunction "CTRL5_7") (pintype "bidirectional"))
    )
    (net (code "189") (name "V5.0$4") (class "Default")
      (node (ref "C86") (pin "1") (pinfunction "1_1") (pintype "passive"))
      (node (ref "D13") (pin "P2") (pinfunction "P2_P2") (pintype "passive"))
      (node (ref "J6") (pin "P1") (pinfunction "VBUS_P1") (pintype "bidirectional"))
      (node (ref "R20") (pin "2") (pinfunction "2_2") (pintype "passive"))
    )
    (net (code "190") (name "V5.0$16") (class "Default")
      (node (ref "C99") (pin "1") (pinfunction "1_1") (pintype "passive"))
      (node (ref "D18") (pin "P2") (pinfunction "P2_P2") (pintype "passive"))
      (node (ref "J5") (pin "P1") (pinfunction "VBUS_P1") (pintype "bidirectional"))
      (node (ref "R37") (pin "2") (pinfunction "2_2") (pintype "passive"))
    )
    (net (code "191") (name "VBUS$1") (class "Default")
      (node (ref "C81") (pin "1") (pinfunction "1_1") (pintype "passive"))
      (node (ref "C84") (pin "1") (pinfunction "1_1") (pintype "passive"))
      (node (ref "FB10") (pin "2") (pinfunction "2_2") (pintype "passive"))
      (node (ref "IC5") (pin "18") (pinfunction "~{RESET}_18") (pintype "input"))
      (node (ref "IC5") (pin "19") (pinfunction "VCC_19") (pintype "power_in"))
    )
    (net (code "192") (name "VDAC_COMP") (class "Default")
      (node (ref "J2") (pin "11") (pinfunction "11_11") (pintype "passive"))
    )
    (net (code "193") (name "V_POWER$2") (class "Default")
      (node (ref "C13") (pin "1") (pinfunction "1_1") (pintype "passive"))
      (node (ref "C30") (pin "1") (pinfunction "1_1") (pintype "passive"))
      (node (ref "R18") (pin "2") (pinfunction "2_2") (pintype "passive"))
      (node (ref "U7") (pin "7") (pinfunction "VIN_7") (pintype "bidirectional"))
    )
    (net (code "194") (name "unconnected-(IC5-CBUS0-Pad22)") (class "Default")
      (node (ref "IC5") (pin "22") (pinfunction "CBUS0_22") (pintype "bidirectional"))
    )
    (net (code "195") (name "unconnected-(IC5-CBUS1-Pad21)") (class "Default")
      (node (ref "IC5") (pin "21") (pinfunction "CBUS1_21") (pintype "bidirectional"))
    )
    (net (code "196") (name "unconnected-(IC5-CBUS2-Pad10)") (class "Default")
      (node (ref "IC5") (pin "10") (pinfunction "CBUS2_10") (pintype "bidirectional"))
    )
    (net (code "197") (name "unconnected-(IC5-CBUS3-Pad11)") (class "Default")
      (node (ref "IC5") (pin "11") (pinfunction "CBUS3_11") (pintype "bidirectional"))
    )
    (net (code "198") (name "unconnected-(IC5-CBUS4-Pad9)") (class "Default")
      (node (ref "IC5") (pin "9") (pinfunction "CBUS4_9") (pintype "bidirectional"))
    )
    (net (code "199") (name "unconnected-(IC5-OSCI-Pad27)") (class "Default")
      (node (ref "IC5") (pin "27") (pinfunction "OSCI_27") (pintype "input"))
    )
    (net (code "200") (name "unconnected-(IC5-OSCO-Pad28)") (class "Default")
      (node (ref "IC5") (pin "28") (pinfunction "OSCO_28") (pintype "output"))
    )
    (net (code "201") (name "unconnected-(IC5-~{CTS}-Pad8)") (class "Default")
      (node (ref "IC5") (pin "8") (pinfunction "~{CTS}_8") (pintype "input"))
    )
    (net (code "202") (name "unconnected-(IC5-~{DCD}-Pad7)") (class "Default")
      (node (ref "IC5") (pin "7") (pinfunction "~{DCD}_7") (pintype "input"))
    )
    (net (code "203") (name "unconnected-(IC5-~{DSR}-Pad6)") (class "Default")
      (node (ref "IC5") (pin "6") (pinfunction "~{DSR}_6") (pintype "input"))
    )
    (net (code "204") (name "unconnected-(IC5-~{DTR}-Pad31)") (class "Default")
      (node (ref "IC5") (pin "31") (pinfunction "~{DTR}_31") (pintype "output"))
    )
    (net (code "205") (name "unconnected-(IC5-~{RI}-Pad3)") (class "Default")
      (node (ref "IC5") (pin "3") (pinfunction "~{RI}_3") (pintype "input"))
    )
    (net (code "206") (name "unconnected-(IC5-~{RTS}-Pad32)") (class "Default")
      (node (ref "IC5") (pin "32") (pinfunction "~{RTS}_32") (pintype "output"))
    )
    (net (code "207") (name "unconnected-(J2-Pad1)") (class "Default")
      (node (ref "J2") (pin "1") (pinfunction "1_1") (pintype "passive"))
    )
    (net (code "208") (name "unconnected-(J2-Pad4)") (class "Default")
      (node (ref "J2") (pin "4") (pinfunction "4_4") (pintype "passive"))
    )
    (net (code "209") (name "unconnected-(J2-Pad6)") (class "Default")
      (node (ref "J2") (pin "6") (pinfunction "6_6") (pintype "passive"))
    )
    (net (code "210") (name "unconnected-(J2-Pad43)") (class "Default")
      (node (ref "J2") (pin "43") (pinfunction "43_43") (pintype "passive"))
    )
    (net (code "211") (name "unconnected-(J2-Pad45)") (class "Default")
      (node (ref "J2") (pin "45") (pinfunction "45_45") (pintype "passive"))
    )
    (net (code "212") (name "unconnected-(J2-Pad46)") (class "Default")
      (node (ref "J2") (pin "46") (pinfunction "46_46") (pintype "passive"))
    )
    (net (code "213") (name "unconnected-(J2-Pad47)") (class "Default")
      (node (ref "J2") (pin "47") (pinfunction "47_47") (pintype "passive"))
    )
    (net (code "214") (name "unconnected-(J2-Pad48)") (class "Default")
      (node (ref "J2") (pin "48") (pinfunction "48_48") (pintype "passive"))
    )
    (net (code "215") (name "unconnected-(J2-Pad49)") (class "Default")
      (node (ref "J2") (pin "49") (pinfunction "49_49") (pintype "passive"))
    )
    (net (code "216") (name "unconnected-(J2-Pad52)") (class "Default")
      (node (ref "J2") (pin "52") (pinfunction "52_52") (pintype "passive"))
    )
    (net (code "217") (name "unconnected-(J2-Pad54)") (class "Default")
      (node (ref "J2") (pin "54") (pinfunction "54_54") (pintype "passive"))
    )
    (net (code "218") (name "unconnected-(J2-Pad57)") (class "Default")
      (node (ref "J2") (pin "57") (pinfunction "57_57") (pintype "passive"))
    )
    (net (code "219") (name "unconnected-(J2-Pad58)") (class "Default")
      (node (ref "J2") (pin "58") (pinfunction "58_58") (pintype "passive"))
    )
    (net (code "220") (name "unconnected-(J2-Pad59)") (class "Default")
      (node (ref "J2") (pin "59") (pinfunction "59_59") (pintype "passive"))
    )
    (net (code "221") (name "unconnected-(J2-Pad60)") (class "Default")
      (node (ref "J2") (pin "60") (pinfunction "60_60") (pintype "passive"))
    )
    (net (code "222") (name "unconnected-(J2-Pad63)") (class "Default")
      (node (ref "J2") (pin "63") (pinfunction "63_63") (pintype "passive"))
    )
    (net (code "223") (name "unconnected-(J2-Pad64)") (class "Default")
      (node (ref "J2") (pin "64") (pinfunction "64_64") (pintype "passive"))
    )
    (net (code "224") (name "unconnected-(J2-Pad65)") (class "Default")
      (node (ref "J2") (pin "65") (pinfunction "65_65") (pintype "passive"))
    )
    (net (code "225") (name "unconnected-(J2-Pad66)") (class "Default")
      (node (ref "J2") (pin "66") (pinfunction "66_66") (pintype "passive"))
    )
    (net (code "226") (name "unconnected-(J2-Pad69)") (class "Default")
      (node (ref "J2") (pin "69") (pinfunction "69_69") (pintype "passive"))
    )
    (net (code "227") (name "unconnected-(J2-Pad71)") (class "Default")
      (node (ref "J2") (pin "71") (pinfunction "71_71") (pintype "passive"))
    )
    (net (code "228") (name "unconnected-(J7-Pad57)") (class "Default")
      (node (ref "J7") (pin "57") (pinfunction "57_57") (pintype "passive"))
    )
    (net (code "229") (name "unconnected-(J7-Pad61)") (class "Default")
      (node (ref "J7") (pin "61") (pinfunction "61_61") (pintype "passive"))
    )
    (net (code "230") (name "unconnected-(J7-Pad62)") (class "Default")
      (node (ref "J7") (pin "62") (pinfunction "62_62") (pintype "passive"))
    )
    (net (code "231") (name "unconnected-(J7-Pad63)") (class "Default")
      (node (ref "J7") (pin "63") (pinfunction "63_63") (pintype "passive"))
    )
    (net (code "232") (name "unconnected-(J7-Pad64)") (class "Default")
      (node (ref "J7") (pin "64") (pinfunction "64_64") (pintype "passive"))
    )
    (net (code "233") (name "unconnected-(J7-Pad67)") (class "Default")
      (node (ref "J7") (pin "67") (pinfunction "67_67") (pintype "passive"))
    )
    (net (code "234") (name "unconnected-(J7-Pad68)") (class "Default")
      (node (ref "J7") (pin "68") (pinfunction "68_68") (pintype "passive"))
    )
    (net (code "235") (name "unconnected-(J7-Pad69)") (class "Default")
      (node (ref "J7") (pin "69") (pinfunction "69_69") (pintype "passive"))
    )
    (net (code "236") (name "unconnected-(J7-Pad70)") (class "Default")
      (node (ref "J7") (pin "70") (pinfunction "70_70") (pintype "passive"))
    )
    (net (code "237") (name "unconnected-(J7-Pad72)") (class "Default")
      (node (ref "J7") (pin "72") (pinfunction "72_72") (pintype "passive"))
    )
    (net (code "238") (name "unconnected-(J7-Pad76)") (class "Default")
      (node (ref "J7") (pin "76") (pinfunction "76_76") (pintype "passive"))
    )
    (net (code "239") (name "unconnected-(J7-Pad89)") (class "Default")
      (node (ref "J7") (pin "89") (pinfunction "89_89") (pintype "passive"))
    )
    (net (code "240") (name "unconnected-(J7-Pad91)") (class "Default")
      (node (ref "J7") (pin "91") (pinfunction "91_91") (pintype "passive"))
    )
    (net (code "241") (name "unconnected-(J9-12-Pad1_12)") (class "Default")
      (node (ref "J9") (pin "1_12") (pinfunction "12_1_12") (pintype "passive"))
    )
    (net (code "242") (name "unconnected-(J10-12-Pad1_12)") (class "Default")
      (node (ref "J10") (pin "1_12") (pinfunction "12_1_12") (pintype "passive"))
    )
    (net (code "243") (name "unconnected-(RP1-Pad3)") (class "Default")
      (node (ref "RP1") (pin "3") (pinfunction "3_3") (pintype "passive"))
    )
    (net (code "244") (name "unconnected-(RP1-Pad4)") (class "Default")
      (node (ref "RP1") (pin "4") (pinfunction "4_4") (pintype "passive"))
    )
    (net (code "245") (name "unconnected-(RP1-Pad5)") (class "Default")
      (node (ref "RP1") (pin "5") (pinfunction "5_5") (pintype "passive"))
    )
    (net (code "246") (name "unconnected-(RP1-Pad6)") (class "Default")
      (node (ref "RP1") (pin "6") (pinfunction "6_6") (pintype "passive"))
    )
    (net (code "247") (name "unconnected-(RP2-Pad1)") (class "Default")
      (node (ref "RP2") (pin "1") (pinfunction "1_1") (pintype "passive"))
    )
    (net (code "248") (name "unconnected-(RP2-Pad2)") (class "Default")
      (node (ref "RP2") (pin "2") (pinfunction "2_2") (pintype "passive"))
    )
    (net (code "249") (name "unconnected-(RP2-Pad7)") (class "Default")
      (node (ref "RP2") (pin "7") (pinfunction "7_7") (pintype "passive"))
    )
    (net (code "250") (name "unconnected-(RP2-Pad8)") (class "Default")
      (node (ref "RP2") (pin "8") (pinfunction "8_8") (pintype "passive"))
    )
    (net (code "251") (name "unconnected-(S2-A'-PadA@2)") (class "Default")
      (node (ref "S2") (pin "A@2") (pinfunction "A'_A@2") (pintype "passive"))
    )
    (net (code "252") (name "unconnected-(S2-B-PadB@1)") (class "Default")
      (node (ref "S2") (pin "B@1") (pinfunction "B_B@1") (pintype "passive"))
    )
    (net (code "253") (name "unconnected-(S3-A'-PadA@2)") (class "Default")
      (node (ref "S3") (pin "A@2") (pinfunction "A'_A@2") (pintype "passive"))
    )
    (net (code "254") (name "unconnected-(S3-B-PadB@1)") (class "Default")
      (node (ref "S3") (pin "B@1") (pinfunction "B_B@1") (pintype "passive"))
    )
    (net (code "255") (name "unconnected-(U$29-NC-Pad6)") (class "Default")
      (node (ref "U$29") (pin "6") (pinfunction "NC_6") (pintype "bidirectional"))
    )
    (net (code "256") (name "unconnected-(U$29-NC-Pad9)") (class "Default")
      (node (ref "U$29") (pin "9") (pinfunction "NC_9") (pintype "bidirectional"))
    )
    (net (code "257") (name "unconnected-(U6-N{slash}A-Pad6)") (class "Default")
      (node (ref "U6") (pin "6") (pinfunction "N/A_6") (pintype "bidirectional"))
    )
    (net (code "258") (name "unconnected-(U6-N{slash}A-Pad8)") (class "Default")
      (node (ref "U6") (pin "8") (pinfunction "N/A_8") (pintype "bidirectional"))
    )
    (net (code "259") (name "unconnected-(U6-N{slash}A-Pad20)") (class "Default")
      (node (ref "U6") (pin "20") (pinfunction "N/A_20") (pintype "bidirectional"))
    )
    (net (code "260") (name "unconnected-(U6-N{slash}A-Pad22)") (class "Default")
      (node (ref "U6") (pin "22") (pinfunction "N/A_22") (pintype "bidirectional"))
    )
    (net (code "261") (name "unconnected-(U6-N{slash}A-Pad24)") (class "Default")
      (node (ref "U6") (pin "24") (pinfunction "N/A_24") (pintype "bidirectional"))
    )
    (net (code "262") (name "unconnected-(U6-N{slash}A-Pad26)") (class "Default")
      (node (ref "U6") (pin "26") (pinfunction "N/A_26") (pintype "bidirectional"))
    )
    (net (code "263") (name "unconnected-(U6-N{slash}A-Pad28)") (class "Default")
      (node (ref "U6") (pin "28") (pinfunction "N/A_28") (pintype "bidirectional"))
    )
    (net (code "264") (name "unconnected-(U6-N{slash}A-Pad30)") (class "Default")
      (node (ref "U6") (pin "30") (pinfunction "N/A_30") (pintype "bidirectional"))
    )
    (net (code "265") (name "unconnected-(U6-N{slash}A-Pad32)") (class "Default")
      (node (ref "U6") (pin "32") (pinfunction "N/A_32") (pintype "bidirectional"))
    )
    (net (code "266") (name "unconnected-(U6-N{slash}A-Pad34)") (class "Default")
      (node (ref "U6") (pin "34") (pinfunction "N/A_34") (pintype "bidirectional"))
    )
    (net (code "267") (name "unconnected-(U6-N{slash}A-Pad36)") (class "Default")
      (node (ref "U6") (pin "36") (pinfunction "N/A_36") (pintype "bidirectional"))
    )
    (net (code "268") (name "unconnected-(U6-N{slash}A-Pad40)") (class "Default")
      (node (ref "U6") (pin "40") (pinfunction "N/A_40") (pintype "bidirectional"))
    )
    (net (code "269") (name "unconnected-(U6-N{slash}A-Pad42)") (class "Default")
      (node (ref "U6") (pin "42") (pinfunction "N/A_42") (pintype "bidirectional"))
    )
    (net (code "270") (name "unconnected-(U6-N{slash}A-Pad44)") (class "Default")
      (node (ref "U6") (pin "44") (pinfunction "N/A_44") (pintype "bidirectional"))
    )
    (net (code "271") (name "unconnected-(U6-N{slash}A-Pad46)") (class "Default")
      (node (ref "U6") (pin "46") (pinfunction "N/A_46") (pintype "bidirectional"))
    )
    (net (code "272") (name "unconnected-(U6-N{slash}A-Pad48)") (class "Default")
      (node (ref "U6") (pin "48") (pinfunction "N/A_48") (pintype "bidirectional"))
    )
    (net (code "273") (name "unconnected-(U6-N{slash}A-Pad67)") (class "Default")
      (node (ref "U6") (pin "67") (pinfunction "N/A_67") (pintype "bidirectional"))
    )
    (net (code "274") (name "unconnected-(U6-PERN1-Pad29)") (class "Default")
      (node (ref "U6") (pin "29") (pinfunction "PERN1_29") (pintype "bidirectional"))
    )
    (net (code "275") (name "unconnected-(U6-PERN2-Pad17)") (class "Default")
      (node (ref "U6") (pin "17") (pinfunction "PERN2_17") (pintype "bidirectional"))
    )
    (net (code "276") (name "unconnected-(U6-PERN3-Pad5)") (class "Default")
      (node (ref "U6") (pin "5") (pinfunction "PERN3_5") (pintype "bidirectional"))
    )
    (net (code "277") (name "unconnected-(U6-PERP1-Pad31)") (class "Default")
      (node (ref "U6") (pin "31") (pinfunction "PERP1_31") (pintype "bidirectional"))
    )
    (net (code "278") (name "unconnected-(U6-PERP2-Pad19)") (class "Default")
      (node (ref "U6") (pin "19") (pinfunction "PERP2_19") (pintype "bidirectional"))
    )
    (net (code "279") (name "unconnected-(U6-PERP3-Pad7)") (class "Default")
      (node (ref "U6") (pin "7") (pinfunction "PERP3_7") (pintype "bidirectional"))
    )
    (net (code "280") (name "unconnected-(U6-PETN1-Pad35)") (class "Default")
      (node (ref "U6") (pin "35") (pinfunction "PETN1_35") (pintype "bidirectional"))
    )
    (net (code "281") (name "unconnected-(U6-PETN2-Pad23)") (class "Default")
      (node (ref "U6") (pin "23") (pinfunction "PETN2_23") (pintype "bidirectional"))
    )
    (net (code "282") (name "unconnected-(U6-PETN3-Pad11)") (class "Default")
      (node (ref "U6") (pin "11") (pinfunction "PETN3_11") (pintype "bidirectional"))
    )
    (net (code "283") (name "unconnected-(U6-PETP1-Pad37)") (class "Default")
      (node (ref "U6") (pin "37") (pinfunction "PETP1_37") (pintype "bidirectional"))
    )
    (net (code "284") (name "unconnected-(U6-PETP2-Pad25)") (class "Default")
      (node (ref "U6") (pin "25") (pinfunction "PETP2_25") (pintype "bidirectional"))
    )
    (net (code "285") (name "unconnected-(U6-PETP3-Pad13)") (class "Default")
      (node (ref "U6") (pin "13") (pinfunction "PETP3_13") (pintype "bidirectional"))
    )
    (net (code "286") (name "unconnected-(U6-~{PEWAKE}-Pad54)") (class "Default")
      (node (ref "U6") (pin "54") (pinfunction "~{PEWAKE}_54") (pintype "bidirectional"))
    )
    (net (code "287") (name "unconnected-(U7-ENA-Pad5)") (class "Default")
      (node (ref "U7") (pin "5") (pinfunction "ENA_5") (pintype "bidirectional"))
    )
    (net (code "288") (name "unconnected-(U7-NC1-Pad2)") (class "Default")
      (node (ref "U7") (pin "2") (pinfunction "NC1_2") (pintype "bidirectional"))
    )
    (net (code "289") (name "unconnected-(U7-NC2-Pad3)") (class "Default")
      (node (ref "U7") (pin "3") (pinfunction "NC2_3") (pintype "bidirectional"))
    )
    (net (code "290") (name "~{RPIBOOT$19}") (class "Default")
      (node (ref "J7") (pin "93") (pinfunction "93_93") (pintype "passive"))
      (node (ref "S1") (pin "3") (pinfunction "B_3") (pintype "passive"))
      (node (ref "S1") (pin "4") (pinfunction "B'_4") (pintype "passive"))
    )
  )
)
